# blades_v40.net
KiCad netlist of a schematic drawn in EAGLE
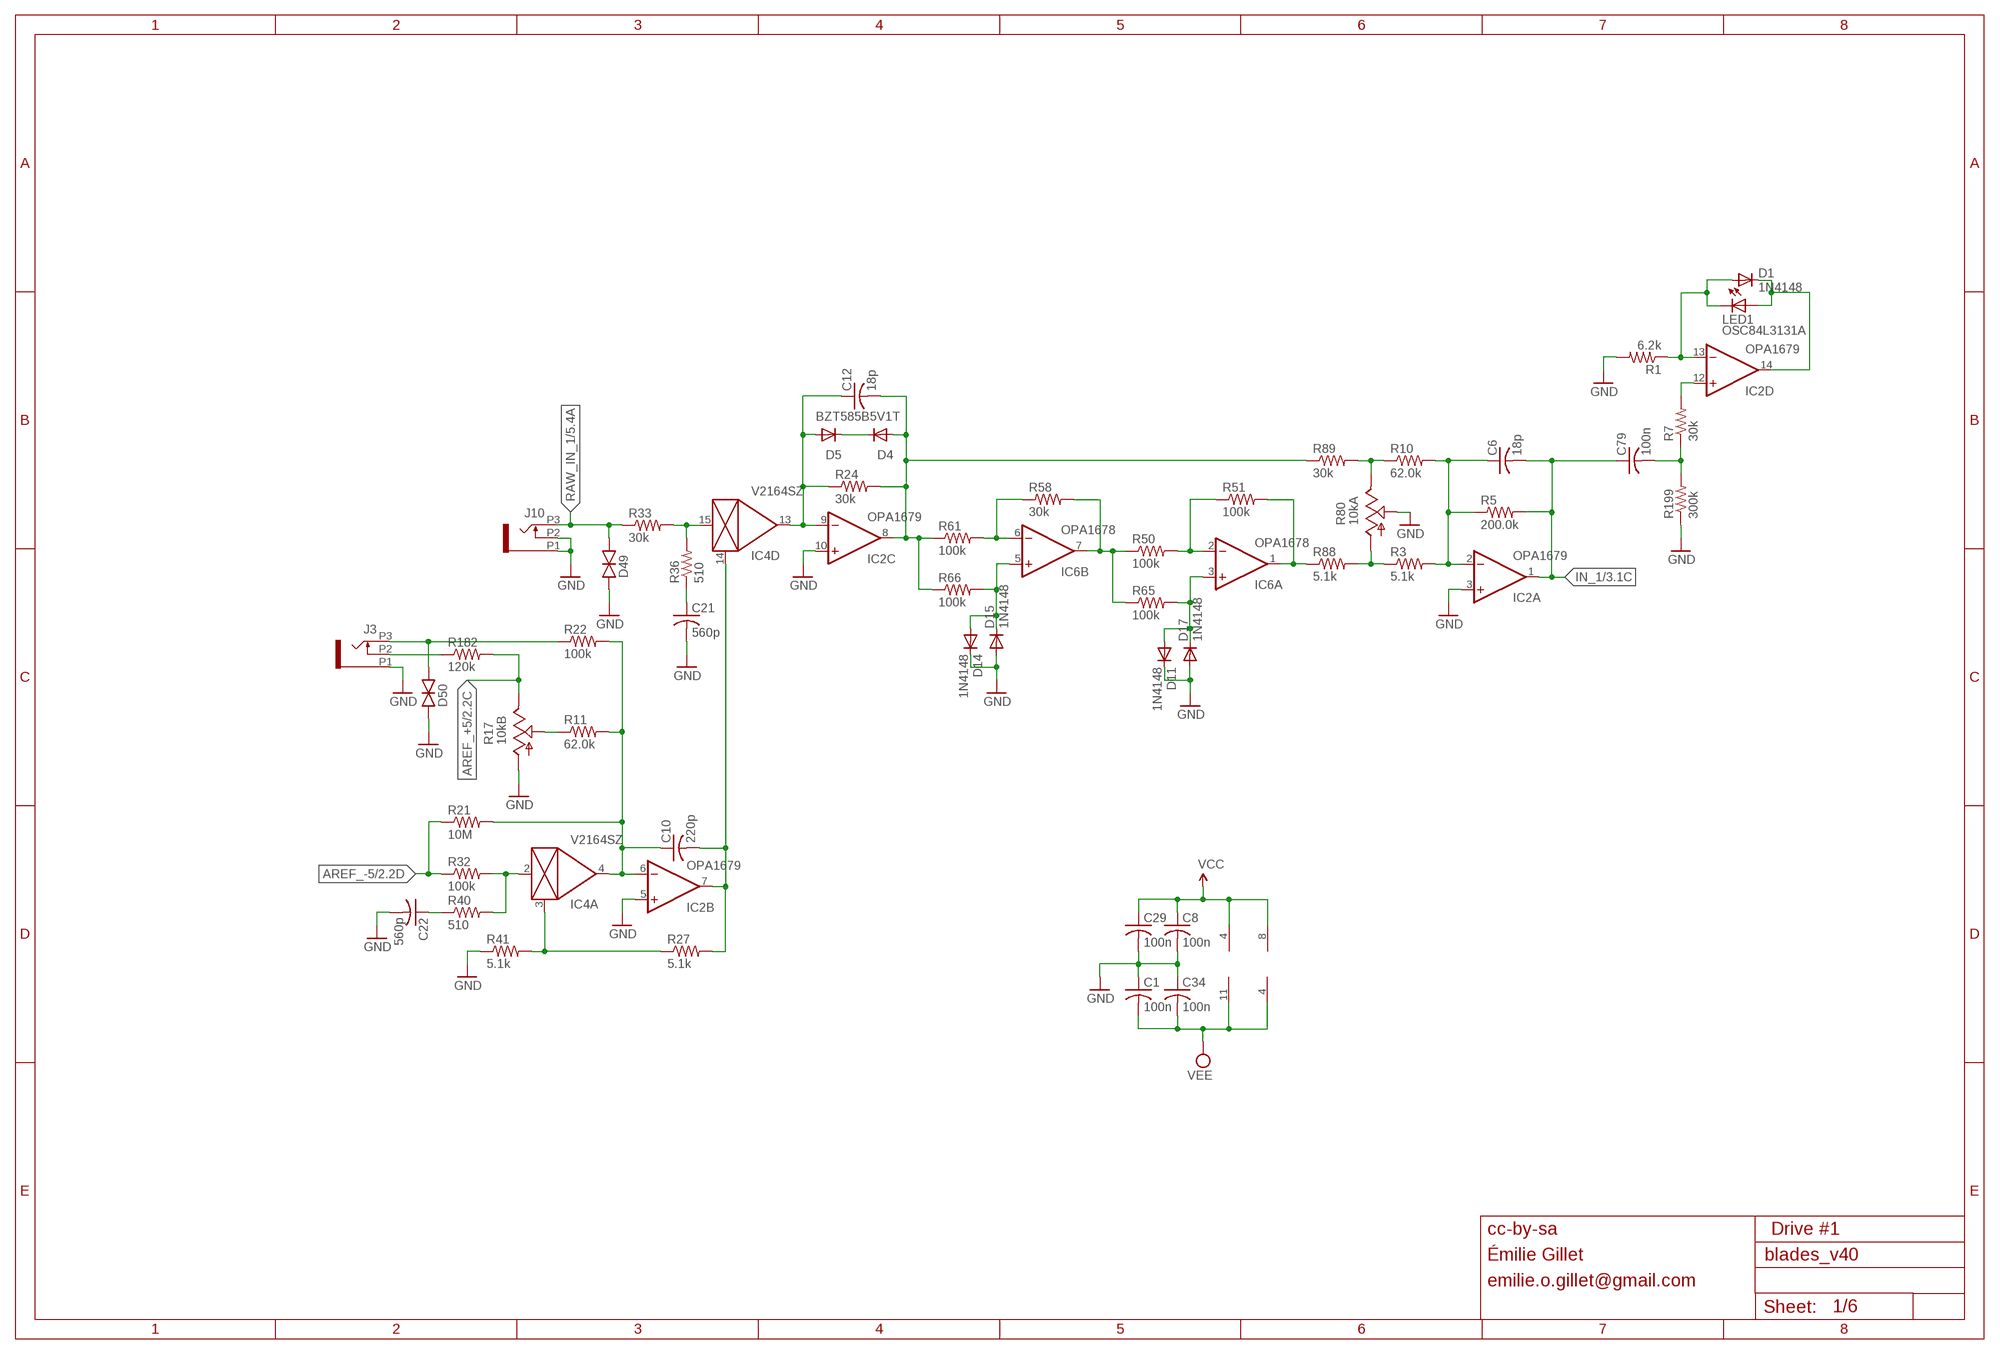
[diagram p0: schematic, sheet 1]
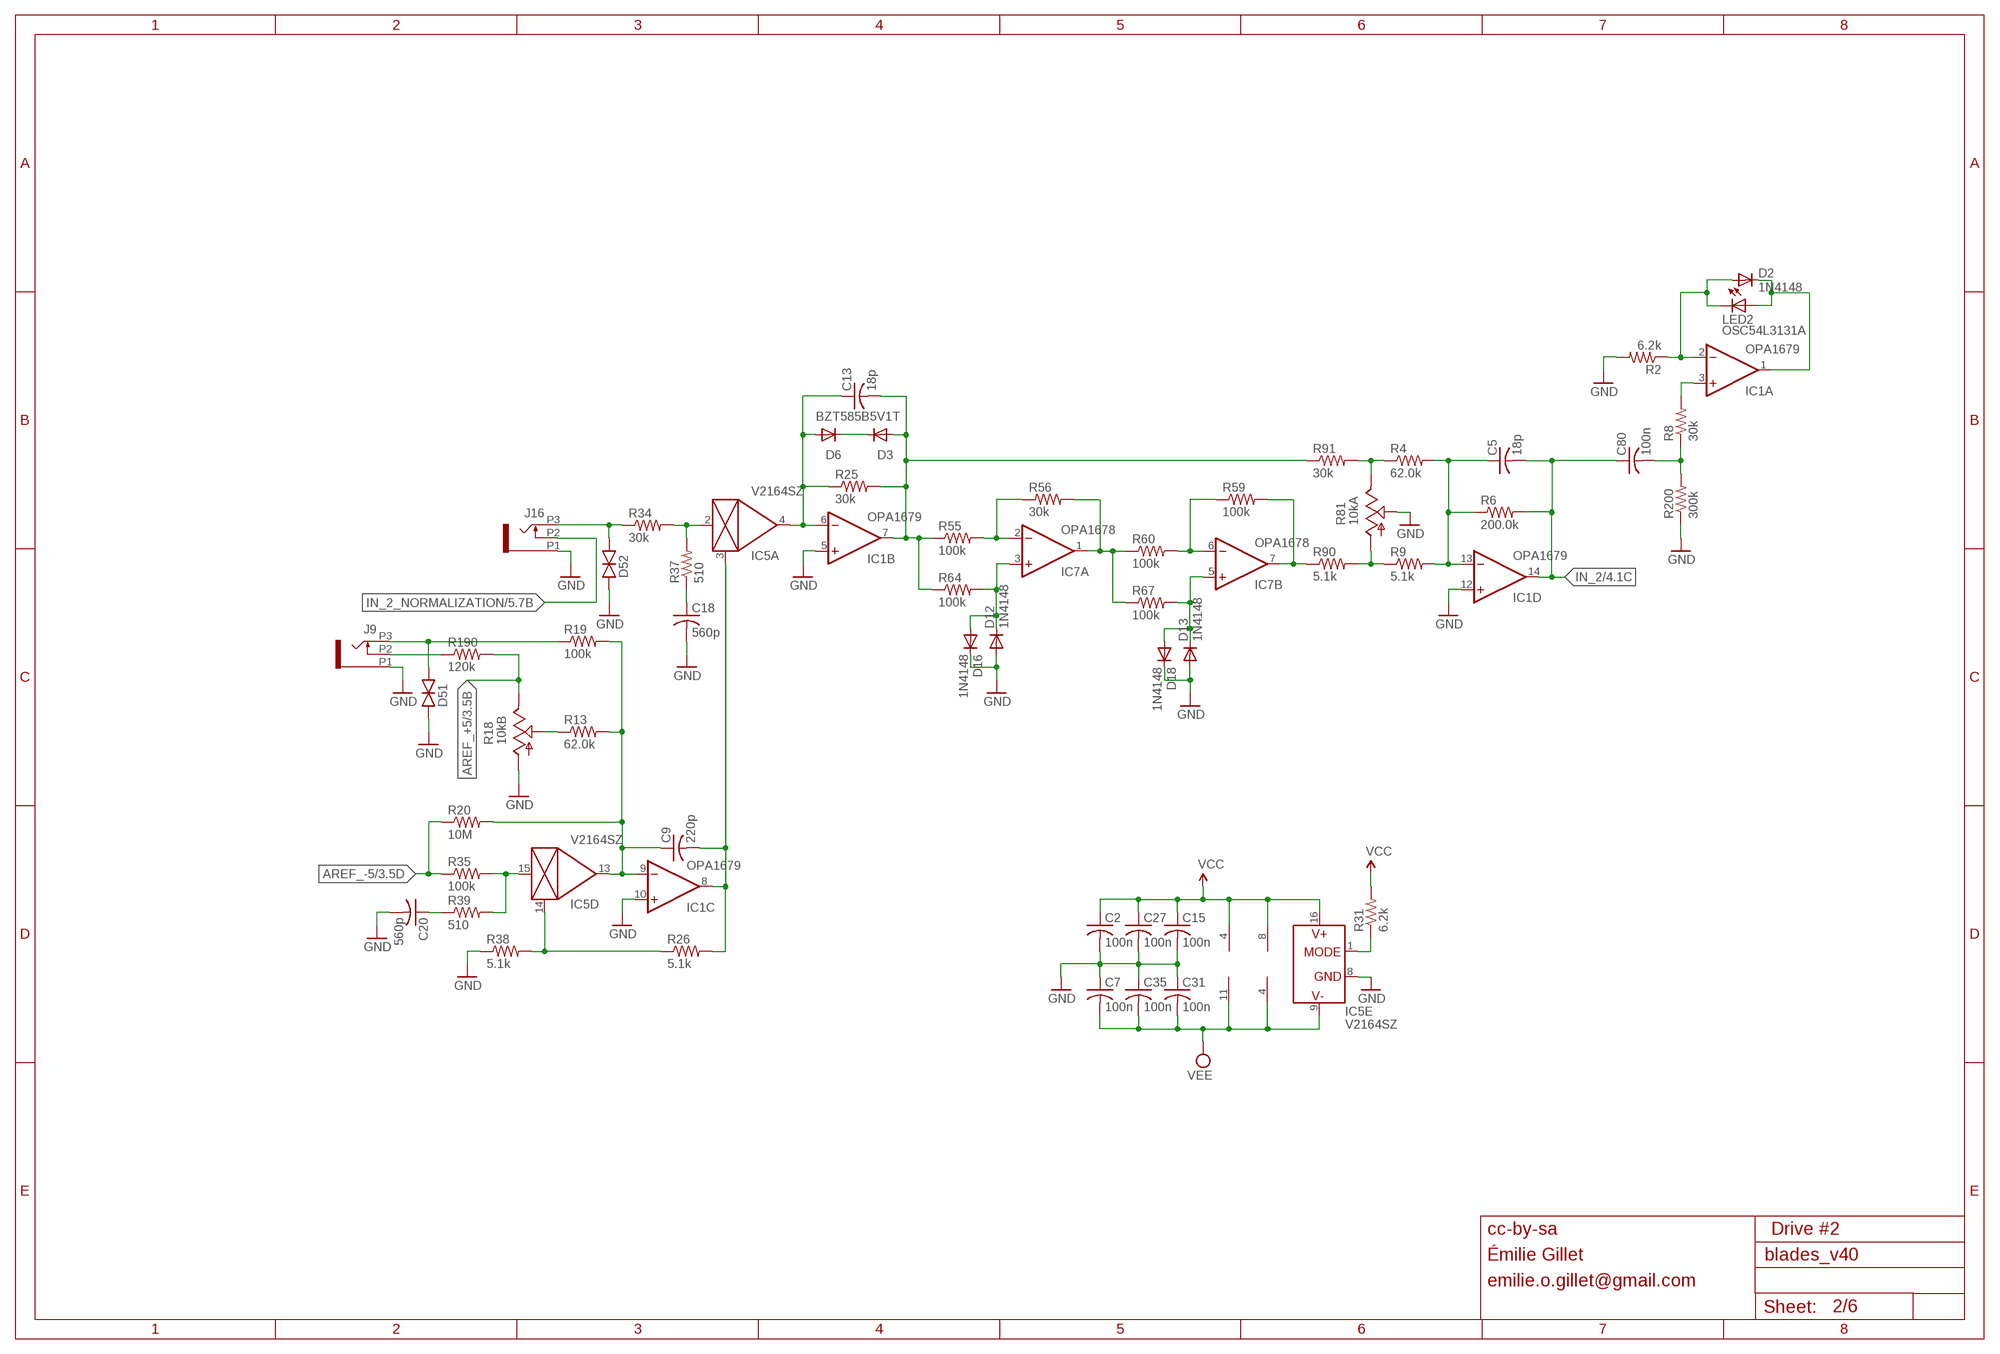
[diagram p1: schematic, sheet 2]
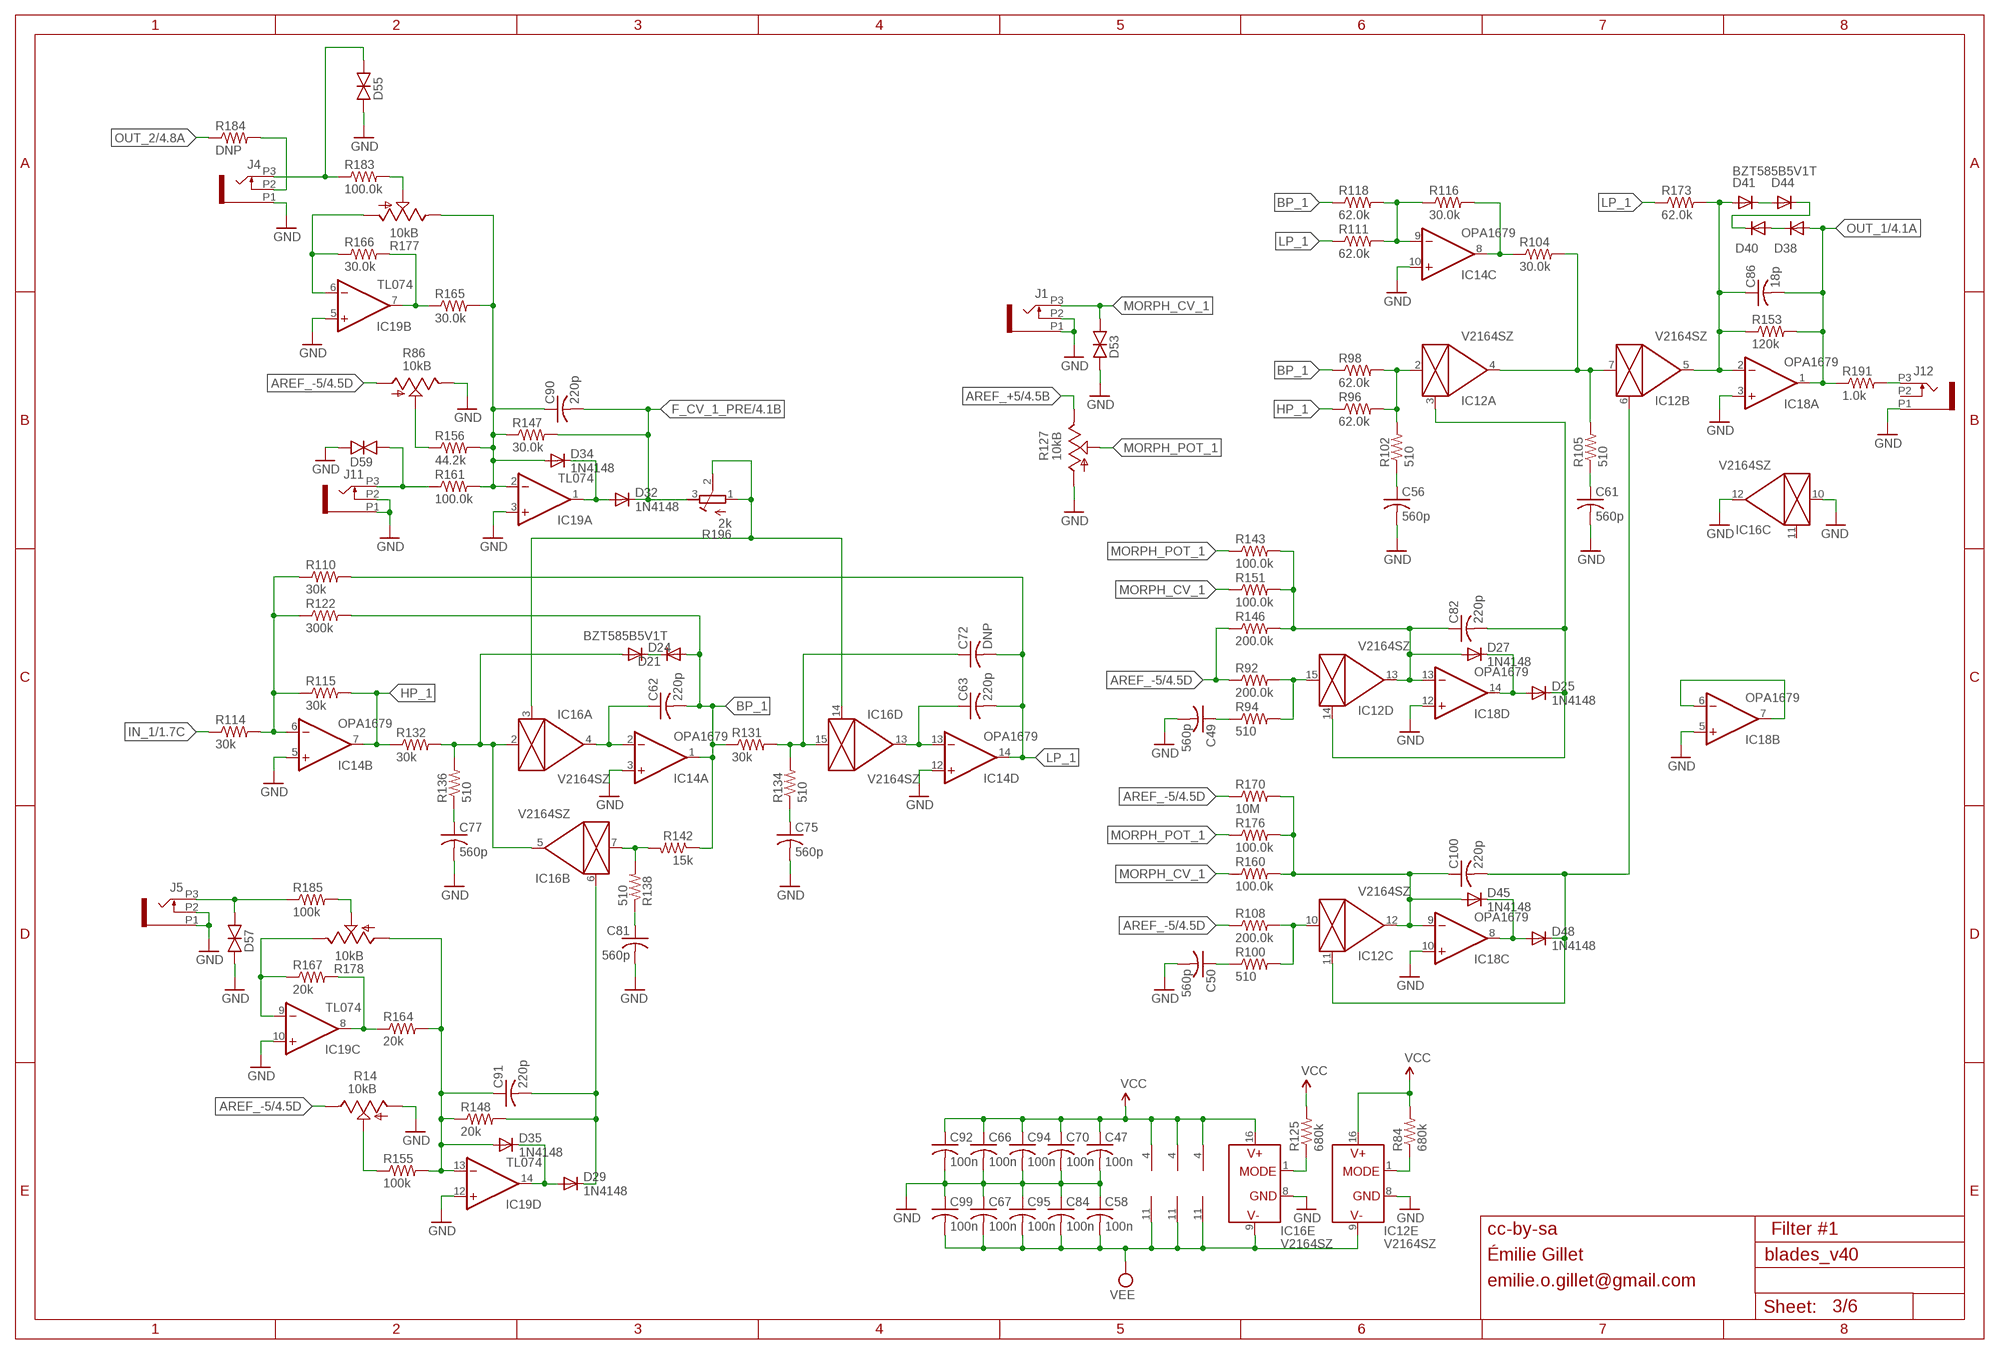
[diagram p2: schematic, sheet 3]
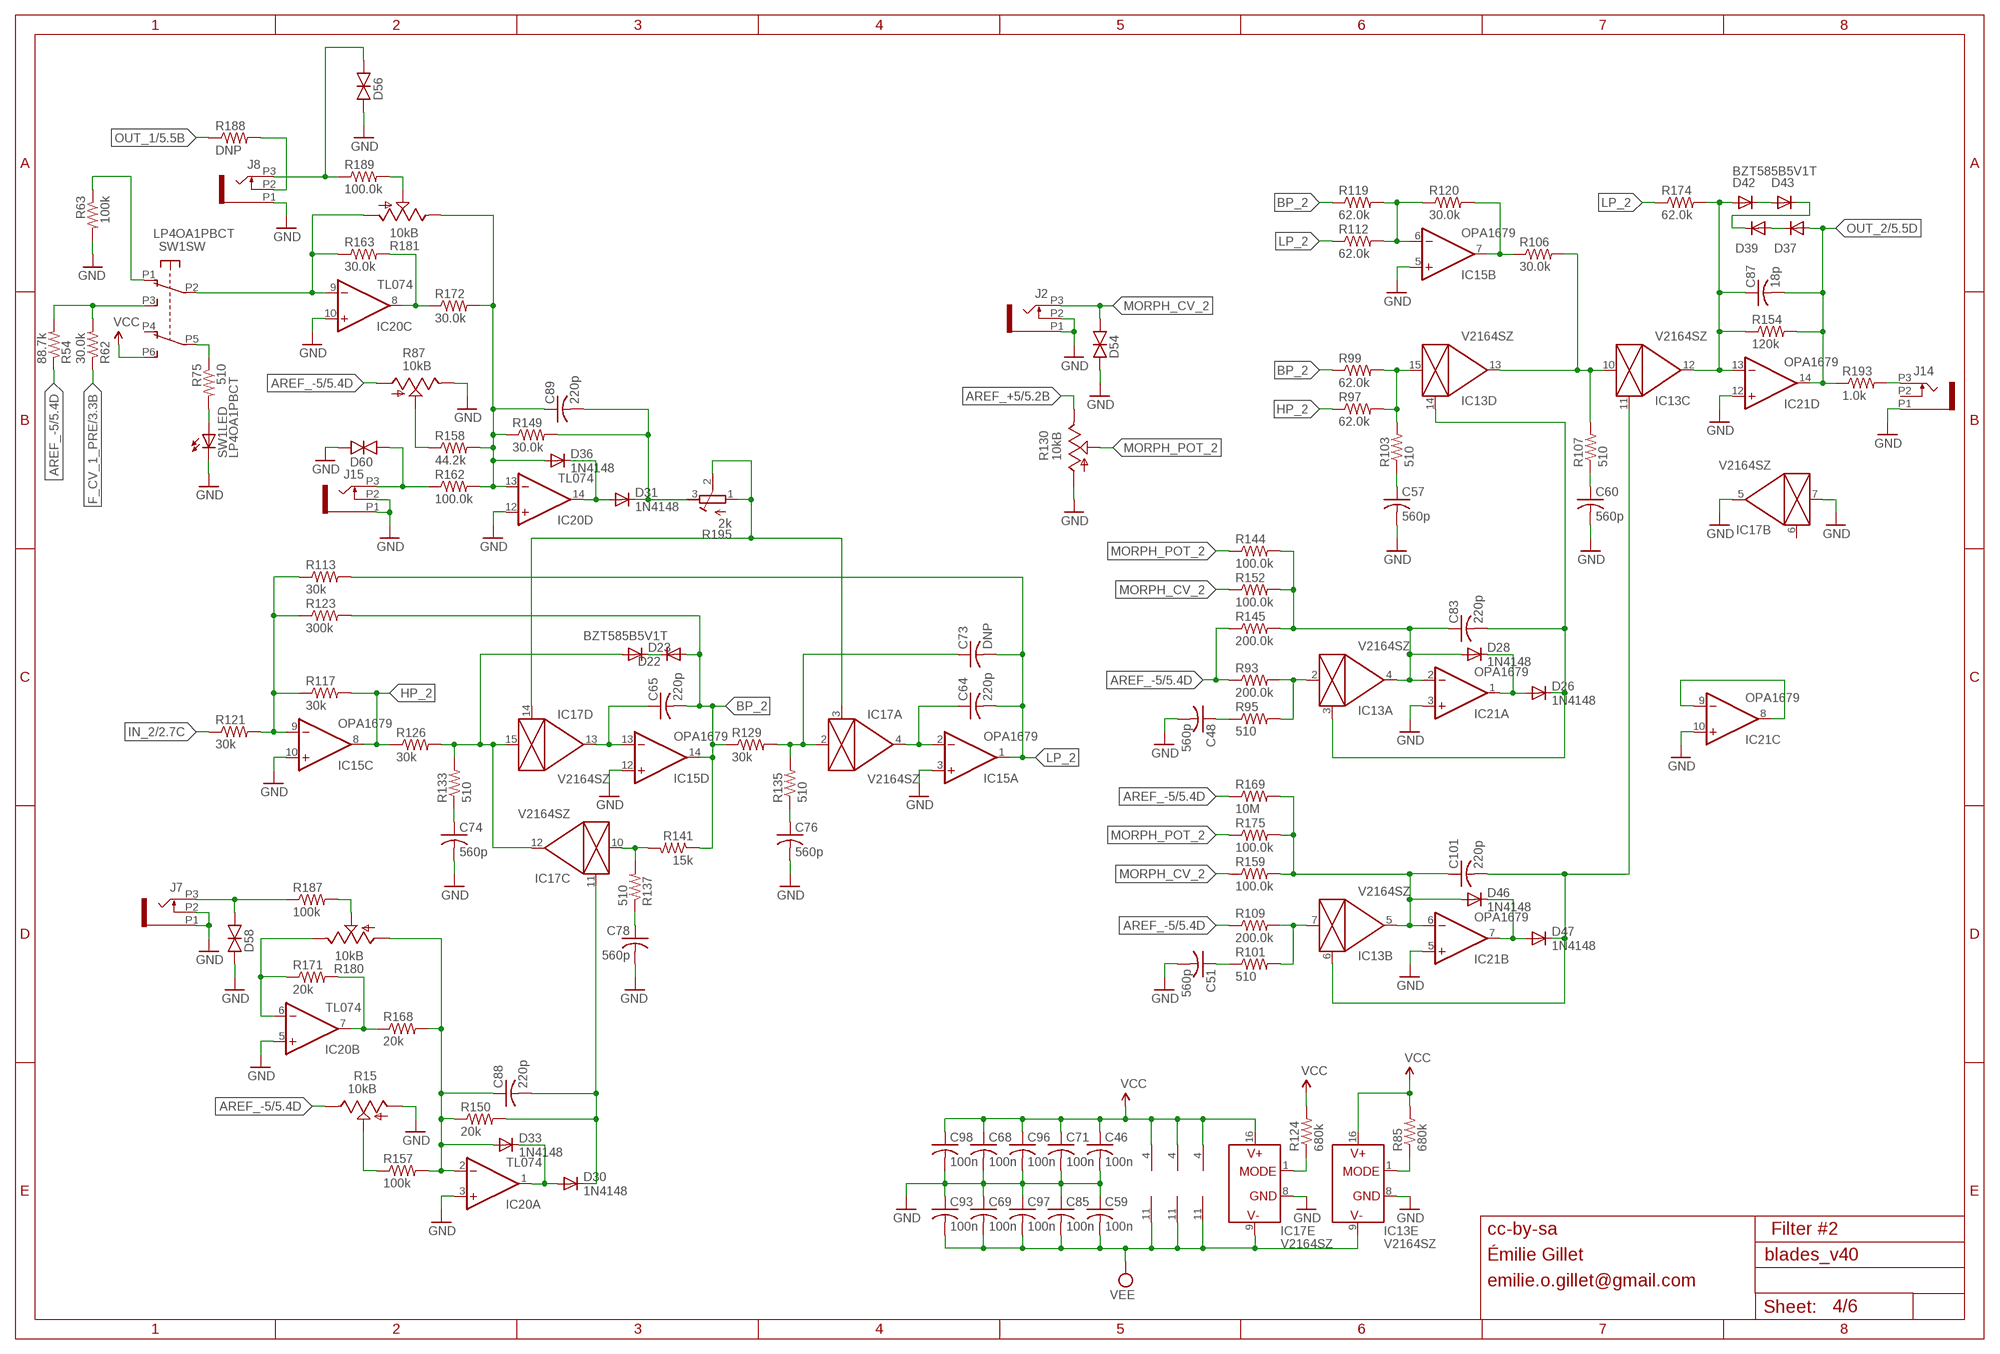
[diagram p3: schematic, sheet 4]
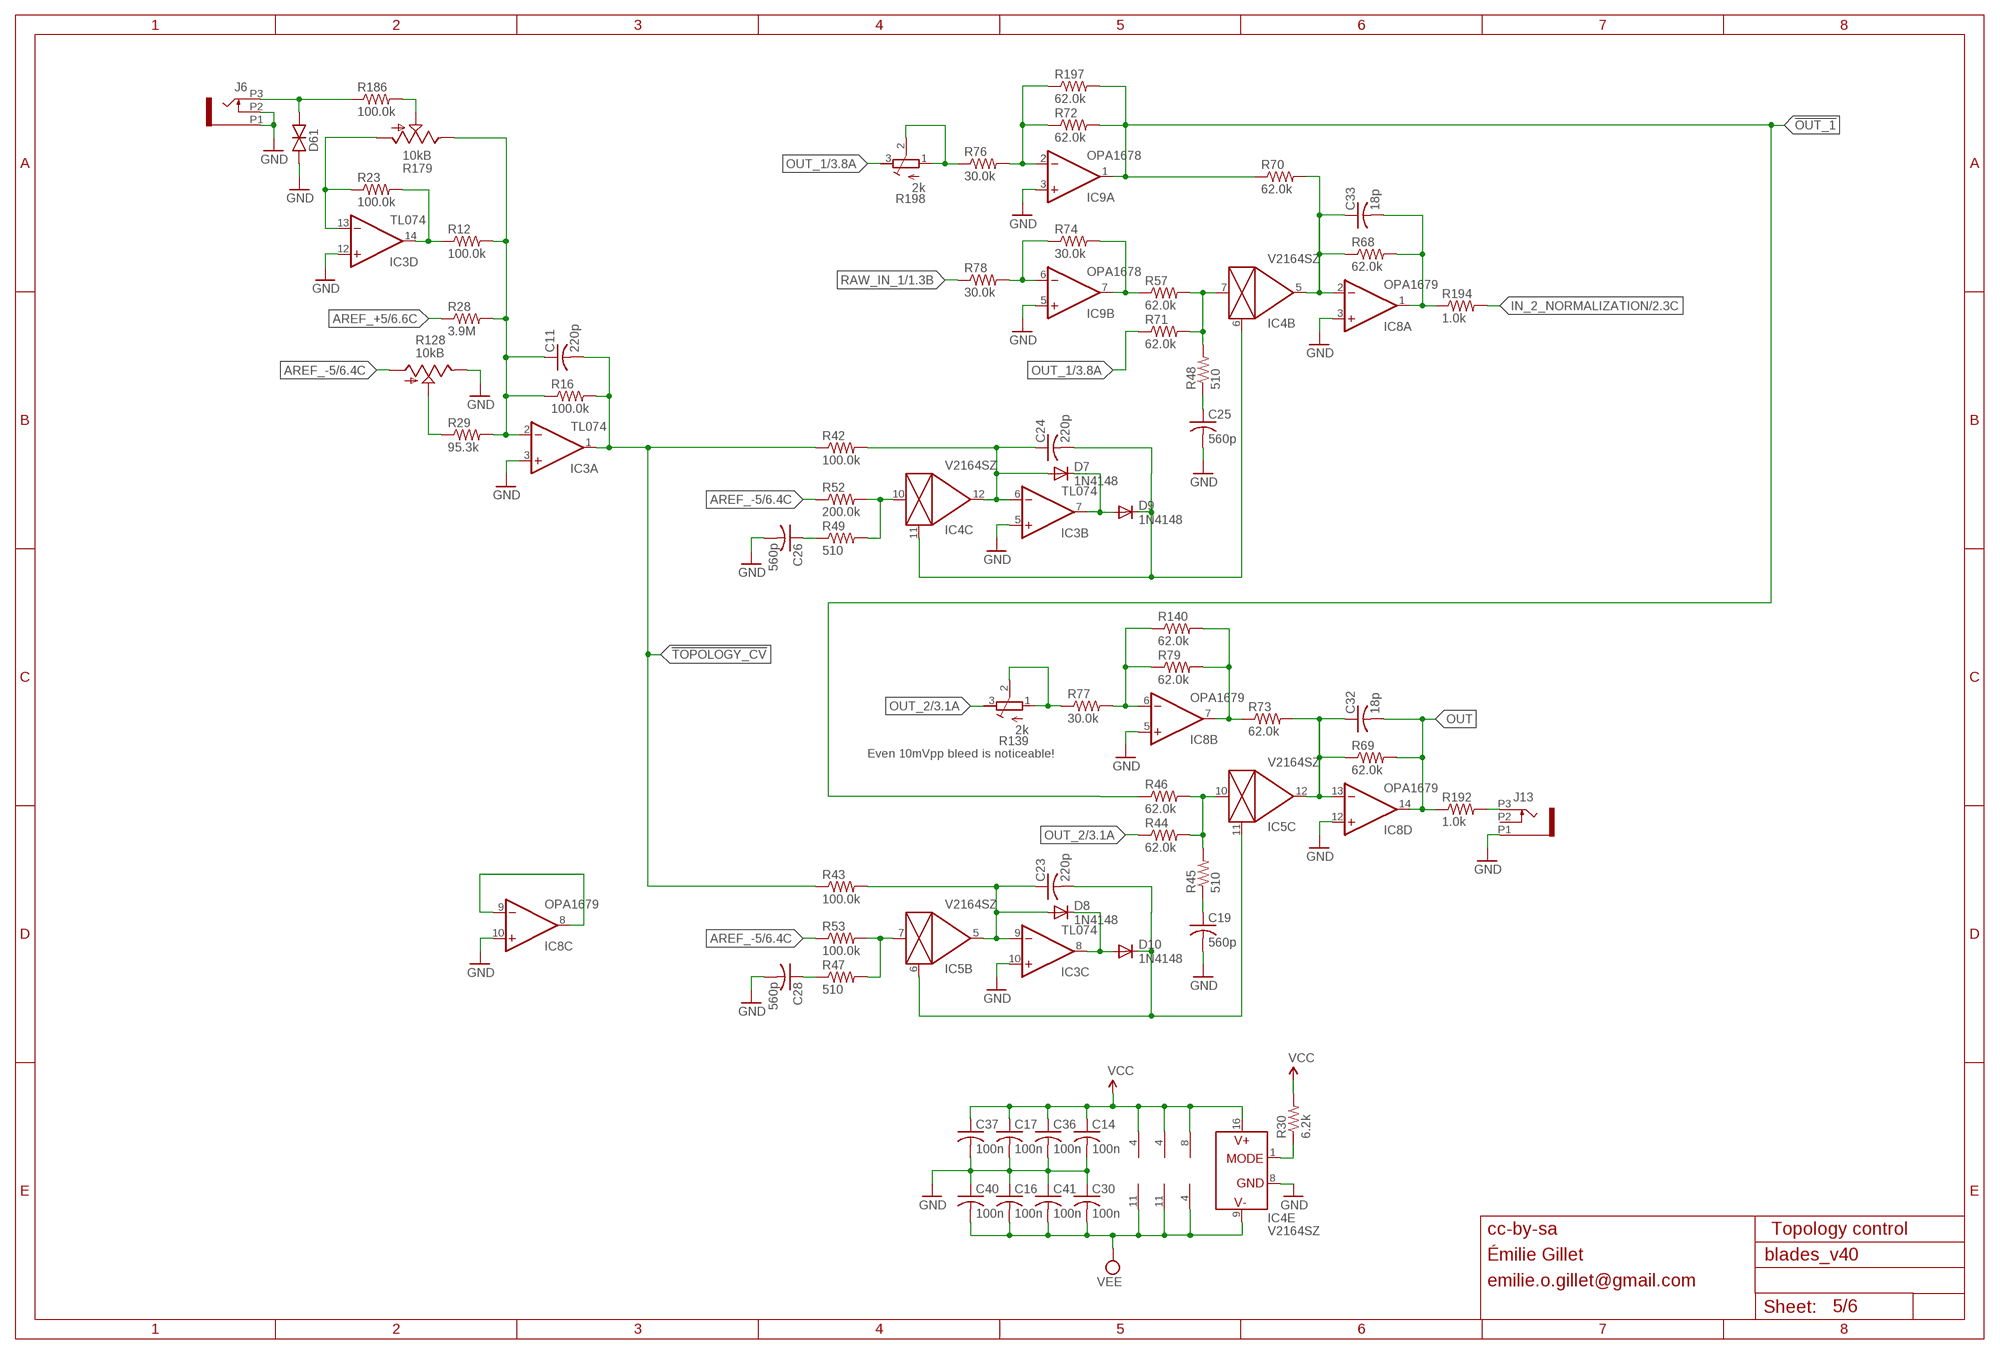
[diagram p4: schematic, sheet 5]
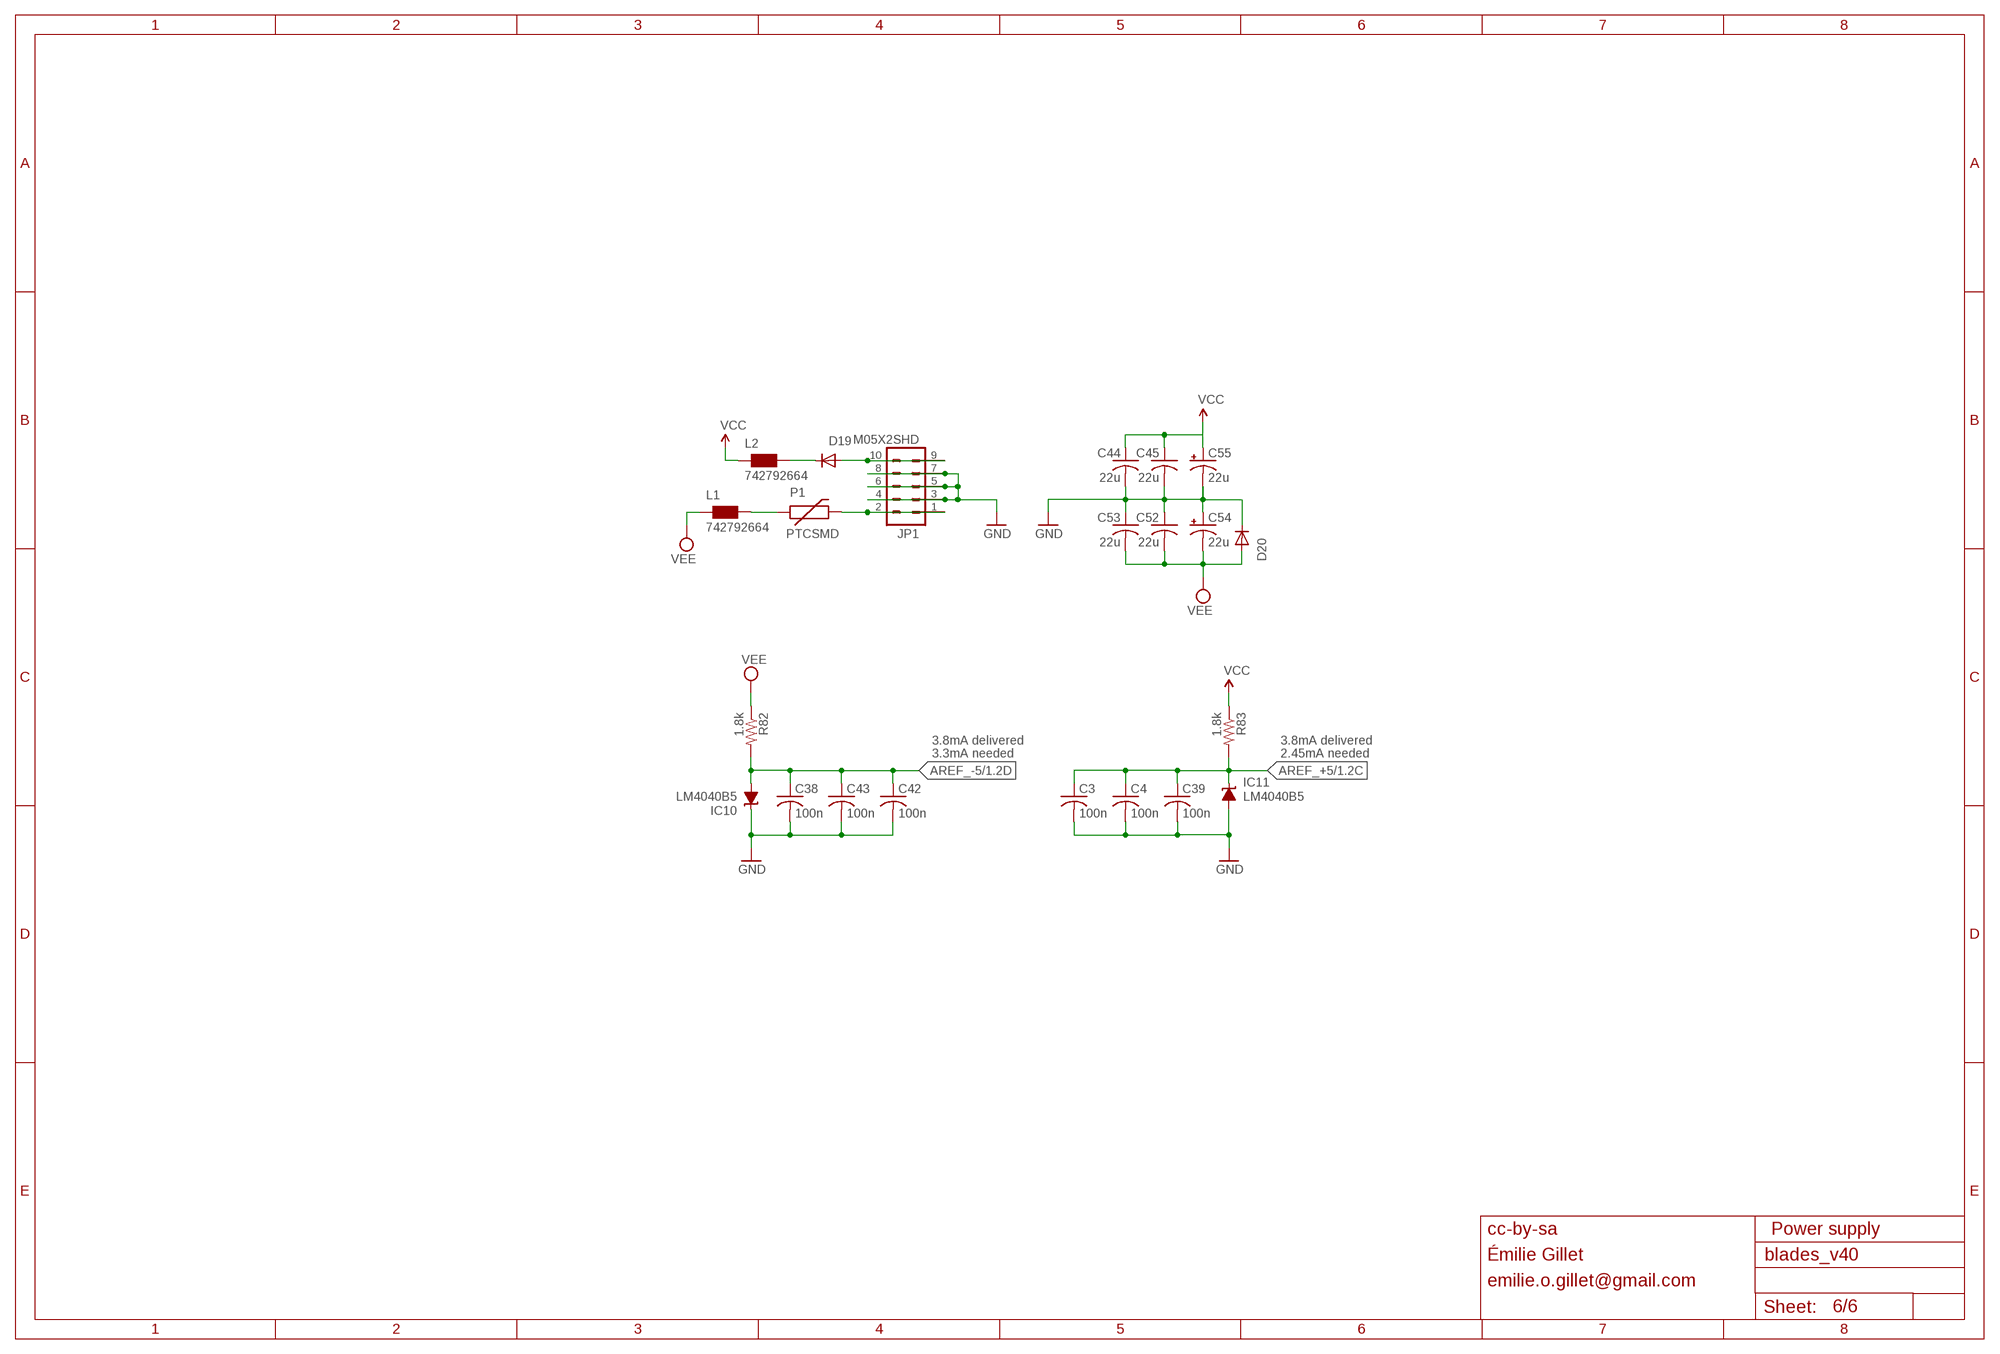
[diagram p5: schematic, sheet 6]

(export (version "E")
  (design (tool "Eeschema 10.0.6"))
  (components
    (comp (ref "C1")
      (value "100n")
      (footprint "eagle-import:C0402")
      (libsource (lib "eagle-import") (part "C-USC0402"))
    )
    (comp (ref "C6")
      (value "18p")
      (footprint "eagle-import:C0402")
      (libsource (lib "eagle-import") (part "C-USC0402"))
    )
    (comp (ref "C8")
      (value "100n")
      (footprint "eagle-import:C0402")
      (libsource (lib "eagle-import") (part "C-USC0402"))
    )
    (comp (ref "C10")
      (value "220p")
      (footprint "eagle-import:C0402")
      (libsource (lib "eagle-import") (part "C-USC0402"))
    )
    (comp (ref "C12")
      (value "18p")
      (footprint "eagle-import:C0402")
      (libsource (lib "eagle-import") (part "C-USC0402"))
    )
    (comp (ref "C21")
      (value "560p")
      (footprint "eagle-import:C0402")
      (libsource (lib "eagle-import") (part "C-USC0402"))
    )
    (comp (ref "C22")
      (value "560p")
      (footprint "eagle-import:C0402")
      (libsource (lib "eagle-import") (part "C-USC0402"))
    )
    (comp (ref "C29")
      (value "100n")
      (footprint "eagle-import:C0402")
      (libsource (lib "eagle-import") (part "C-USC0402"))
    )
    (comp (ref "C34")
      (value "100n")
      (footprint "eagle-import:C0402")
      (libsource (lib "eagle-import") (part "C-USC0402"))
    )
    (comp (ref "C79")
      (value "100n")
      (footprint "eagle-import:C0402")
      (libsource (lib "eagle-import") (part "C-USC0402"))
    )
    (comp (ref "D1")
      (value "1N4148")
      (footprint "eagle-import:SOD523")
      (libsource (lib "eagle-import") (part "DIODE-SOD523"))
    )
    (comp (ref "D4")
      (value "BZT585B5V1T")
      (footprint "eagle-import:SOD523")
      (libsource (lib "eagle-import") (part "DIODE-SOD523"))
    )
    (comp (ref "D5")
      (value "BZT585B5V1T")
      (footprint "eagle-import:SOD523")
      (libsource (lib "eagle-import") (part "DIODE-SOD523"))
    )
    (comp (ref "D11")
      (value "1N4148")
      (footprint "eagle-import:SOD523")
      (libsource (lib "eagle-import") (part "DIODE-SOD523"))
    )
    (comp (ref "D14")
      (value "1N4148")
      (footprint "eagle-import:SOD523")
      (libsource (lib "eagle-import") (part "DIODE-SOD523"))
    )
    (comp (ref "D15")
      (value "1N4148")
      (footprint "eagle-import:SOD523")
      (libsource (lib "eagle-import") (part "DIODE-SOD523"))
    )
    (comp (ref "D17")
      (value "1N4148")
      (footprint "eagle-import:SOD523")
      (libsource (lib "eagle-import") (part "DIODE-SOD523"))
    )
    (comp (ref "D49")
      (value "TVS")
      (footprint "eagle-import:0603")
      (libsource (lib "eagle-import") (part "TVS"))
    )
    (comp (ref "D50")
      (value "TVS")
      (footprint "eagle-import:0603")
      (libsource (lib "eagle-import") (part "TVS"))
    )
    (comp (ref "IC2")
      (value "OPA1679")
      (footprint "eagle-import:TSSOP14_065")
      (libsource (lib "eagle-import") (part "OPA1679PW"))
    )
    (comp (ref "IC4")
      (value "V2164SZ")
      (footprint "eagle-import:SOIC16N")
      (libsource (lib "eagle-import") (part "SSM2164S"))
    )
    (comp (ref "IC6")
      (value "OPA1678")
      (footprint "eagle-import:VSSOP8")
      (libsource (lib "eagle-import") (part "OPA1678DGK"))
    )
    (comp (ref "J3")
      (value "PJ301_THONKICONNTME")
      (footprint "eagle-import:WQP_PJ_301M_TME")
      (libsource (lib "eagle-import") (part "PJ301_THONKICONNTME"))
    )
    (comp (ref "J10")
      (value "PJ301_THONKICONNTME")
      (footprint "eagle-import:WQP_PJ_301M_TME")
      (libsource (lib "eagle-import") (part "PJ301_THONKICONNTME"))
    )
    (comp (ref "LED1")
      (value "OSC84L3131A")
      (footprint "eagle-import:LED3MM")
      (libsource (lib "eagle-import") (part "LED3MM"))
    )
    (comp (ref "R1")
      (value "6.2k")
      (footprint "eagle-import:R0402")
      (libsource (lib "eagle-import") (part "R-US_R0402"))
    )
    (comp (ref "R3")
      (value "5.1k")
      (footprint "eagle-import:R0402")
      (libsource (lib "eagle-import") (part "R-US_R0402"))
    )
    (comp (ref "R5")
      (value "200.0k")
      (footprint "eagle-import:R0402")
      (libsource (lib "eagle-import") (part "R-US_R0402"))
    )
    (comp (ref "R7")
      (value "30k")
      (footprint "eagle-import:R0402")
      (libsource (lib "eagle-import") (part "R-US_R0402"))
    )
    (comp (ref "R10")
      (value "62.0k")
      (footprint "eagle-import:R0402")
      (libsource (lib "eagle-import") (part "R-US_R0402"))
    )
    (comp (ref "R11")
      (value "62.0k")
      (footprint "eagle-import:R0402")
      (libsource (lib "eagle-import") (part "R-US_R0402"))
    )
    (comp (ref "R17")
      (value "10kB")
      (footprint "eagle-import:ALPS_POT_VERTICAL_PS")
      (libsource (lib "eagle-import") (part "pot-alps_POT_USVERTICAL_PS"))
    )
    (comp (ref "R21")
      (value "10M")
      (footprint "eagle-import:R0402")
      (libsource (lib "eagle-import") (part "R-US_R0402"))
    )
    (comp (ref "R22")
      (value "100k")
      (footprint "eagle-import:R0402")
      (libsource (lib "eagle-import") (part "R-US_R0402"))
    )
    (comp (ref "R24")
      (value "30k")
      (footprint "eagle-import:R0402")
      (libsource (lib "eagle-import") (part "R-US_R0402"))
    )
    (comp (ref "R27")
      (value "5.1k")
      (footprint "eagle-import:R0402")
      (libsource (lib "eagle-import") (part "R-US_R0402"))
    )
    (comp (ref "R32")
      (value "100k")
      (footprint "eagle-import:R0402")
      (libsource (lib "eagle-import") (part "R-US_R0402"))
    )
    (comp (ref "R33")
      (value "30k")
      (footprint "eagle-import:R0402")
      (libsource (lib "eagle-import") (part "R-US_R0402"))
    )
    (comp (ref "R36")
      (value "510")
      (footprint "eagle-import:R0402")
      (libsource (lib "eagle-import") (part "R-US_R0402"))
    )
    (comp (ref "R40")
      (value "510")
      (footprint "eagle-import:R0402")
      (libsource (lib "eagle-import") (part "R-US_R0402"))
    )
    (comp (ref "R41")
      (value "5.1k")
      (footprint "eagle-import:R0402")
      (libsource (lib "eagle-import") (part "R-US_R0402"))
    )
    (comp (ref "R50")
      (value "100k")
      (footprint "eagle-import:R0402")
      (libsource (lib "eagle-import") (part "R-US_R0402"))
    )
    (comp (ref "R51")
      (value "100k")
      (footprint "eagle-import:R0402")
      (libsource (lib "eagle-import") (part "R-US_R0402"))
    )
    (comp (ref "R58")
      (value "30k")
      (footprint "eagle-import:R0402")
      (libsource (lib "eagle-import") (part "R-US_R0402"))
    )
    (comp (ref "R61")
      (value "100k")
      (footprint "eagle-import:R0402")
      (libsource (lib "eagle-import") (part "R-US_R0402"))
    )
    (comp (ref "R65")
      (value "100k")
      (footprint "eagle-import:R0402")
      (libsource (lib "eagle-import") (part "R-US_R0402"))
    )
    (comp (ref "R66")
      (value "100k")
      (footprint "eagle-import:R0402")
      (libsource (lib "eagle-import") (part "R-US_R0402"))
    )
    (comp (ref "R80")
      (value "10kA")
      (footprint "eagle-import:ALPS_POT_NARROW")
      (libsource (lib "eagle-import") (part "POT_USVERTICAL_NARROW"))
    )
    (comp (ref "R88")
      (value "5.1k")
      (footprint "eagle-import:R0402")
      (libsource (lib "eagle-import") (part "R-US_R0402"))
    )
    (comp (ref "R89")
      (value "30k")
      (footprint "eagle-import:R0402")
      (libsource (lib "eagle-import") (part "R-US_R0402"))
    )
    (comp (ref "R182")
      (value "120k")
      (footprint "eagle-import:R0402")
      (libsource (lib "eagle-import") (part "R-US_R0402"))
    )
    (comp (ref "R199")
      (value "300k")
      (footprint "eagle-import:R0402")
      (libsource (lib "eagle-import") (part "R-US_R0402"))
    )
    (comp (ref "C46")
      (value "100n")
      (footprint "eagle-import:C0402")
      (libsource (lib "eagle-import") (part "C-USC0402"))
    )
    (comp (ref "C48")
      (value "560p")
      (footprint "eagle-import:C0402")
      (libsource (lib "eagle-import") (part "C-USC0402"))
    )
    (comp (ref "C51")
      (value "560p")
      (footprint "eagle-import:C0402")
      (libsource (lib "eagle-import") (part "C-USC0402"))
    )
    (comp (ref "C57")
      (value "560p")
      (footprint "eagle-import:C0402")
      (libsource (lib "eagle-import") (part "C-USC0402"))
    )
    (comp (ref "C59")
      (value "100n")
      (footprint "eagle-import:C0402")
      (libsource (lib "eagle-import") (part "C-USC0402"))
    )
    (comp (ref "C60")
      (value "560p")
      (footprint "eagle-import:C0402")
      (libsource (lib "eagle-import") (part "C-USC0402"))
    )
    (comp (ref "C64")
      (value "220p")
      (footprint "eagle-import:C0402")
      (libsource (lib "eagle-import") (part "C-USC0402"))
    )
    (comp (ref "C65")
      (value "220p")
      (footprint "eagle-import:C0402")
      (libsource (lib "eagle-import") (part "C-USC0402"))
    )
    (comp (ref "C68")
      (value "100n")
      (footprint "eagle-import:C0402")
      (libsource (lib "eagle-import") (part "C-USC0402"))
    )
    (comp (ref "C69")
      (value "100n")
      (footprint "eagle-import:C0402")
      (libsource (lib "eagle-import") (part "C-USC0402"))
    )
    (comp (ref "C71")
      (value "100n")
      (footprint "eagle-import:C0402")
      (libsource (lib "eagle-import") (part "C-USC0402"))
    )
    (comp (ref "C73")
      (value "DNP")
      (footprint "eagle-import:C0402")
      (libsource (lib "eagle-import") (part "C-USC0402"))
    )
    (comp (ref "C74")
      (value "560p")
      (footprint "eagle-import:C0402")
      (libsource (lib "eagle-import") (part "C-USC0402"))
    )
    (comp (ref "C76")
      (value "560p")
      (footprint "eagle-import:C0402")
      (libsource (lib "eagle-import") (part "C-USC0402"))
    )
    (comp (ref "C78")
      (value "560p")
      (footprint "eagle-import:C0402")
      (libsource (lib "eagle-import") (part "C-USC0402"))
    )
    (comp (ref "C83")
      (value "220p")
      (footprint "eagle-import:C0402")
      (libsource (lib "eagle-import") (part "C-USC0402"))
    )
    (comp (ref "C85")
      (value "100n")
      (footprint "eagle-import:C0402")
      (libsource (lib "eagle-import") (part "C-USC0402"))
    )
    (comp (ref "C87")
      (value "18p")
      (footprint "eagle-import:C0402")
      (libsource (lib "eagle-import") (part "C-USC0402"))
    )
    (comp (ref "C88")
      (value "220p")
      (footprint "eagle-import:C0402")
      (libsource (lib "eagle-import") (part "C-USC0402"))
    )
    (comp (ref "C89")
      (value "220p")
      (footprint "eagle-import:C0402")
      (libsource (lib "eagle-import") (part "C-USC0402"))
    )
    (comp (ref "C93")
      (value "100n")
      (footprint "eagle-import:C0402")
      (libsource (lib "eagle-import") (part "C-USC0402"))
    )
    (comp (ref "C96")
      (value "100n")
      (footprint "eagle-import:C0402")
      (libsource (lib "eagle-import") (part "C-USC0402"))
    )
    (comp (ref "C97")
      (value "100n")
      (footprint "eagle-import:C0402")
      (libsource (lib "eagle-import") (part "C-USC0402"))
    )
    (comp (ref "C98")
      (value "100n")
      (footprint "eagle-import:C0402")
      (libsource (lib "eagle-import") (part "C-USC0402"))
    )
    (comp (ref "C101")
      (value "220p")
      (footprint "eagle-import:C0402")
      (libsource (lib "eagle-import") (part "C-USC0402"))
    )
    (comp (ref "D22")
      (value "BZT585B5V1T")
      (footprint "eagle-import:SOD523")
      (libsource (lib "eagle-import") (part "DIODE-SOD523"))
    )
    (comp (ref "D23")
      (value "BZT585B5V1T")
      (footprint "eagle-import:SOD523")
      (libsource (lib "eagle-import") (part "DIODE-SOD523"))
    )
    (comp (ref "D26")
      (value "1N4148")
      (footprint "eagle-import:SOD523")
      (libsource (lib "eagle-import") (part "DIODE-SOD523"))
    )
    (comp (ref "D28")
      (value "1N4148")
      (footprint "eagle-import:SOD523")
      (libsource (lib "eagle-import") (part "DIODE-SOD523"))
    )
    (comp (ref "D30")
      (value "1N4148")
      (footprint "eagle-import:SOD523")
      (libsource (lib "eagle-import") (part "DIODE-SOD523"))
    )
    (comp (ref "D31")
      (value "1N4148")
      (footprint "eagle-import:SOD523")
      (libsource (lib "eagle-import") (part "DIODE-SOD523"))
    )
    (comp (ref "D33")
      (value "1N4148")
      (footprint "eagle-import:SOD523")
      (libsource (lib "eagle-import") (part "DIODE-SOD523"))
    )
    (comp (ref "D36")
      (value "1N4148")
      (footprint "eagle-import:SOD523")
      (libsource (lib "eagle-import") (part "DIODE-SOD523"))
    )
    (comp (ref "D37")
      (value "BZT585B5V1T")
      (footprint "eagle-import:SOD523")
      (libsource (lib "eagle-import") (part "DIODE-SOD523"))
    )
    (comp (ref "D39")
      (value "BZT585B5V1T")
      (footprint "eagle-import:SOD523")
      (libsource (lib "eagle-import") (part "DIODE-SOD523"))
    )
    (comp (ref "D42")
      (value "BZT585B5V1T")
      (footprint "eagle-import:SOD523")
      (libsource (lib "eagle-import") (part "DIODE-SOD523"))
    )
    (comp (ref "D43")
      (value "BZT585B5V1T")
      (footprint "eagle-import:SOD523")
      (libsource (lib "eagle-import") (part "DIODE-SOD523"))
    )
    (comp (ref "D46")
      (value "1N4148")
      (footprint "eagle-import:SOD523")
      (libsource (lib "eagle-import") (part "DIODE-SOD523"))
    )
    (comp (ref "D47")
      (value "1N4148")
      (footprint "eagle-import:SOD523")
      (libsource (lib "eagle-import") (part "DIODE-SOD523"))
    )
    (comp (ref "D54")
      (value "TVS")
      (footprint "eagle-import:0603")
      (libsource (lib "eagle-import") (part "TVS"))
    )
    (comp (ref "D56")
      (value "TVS")
      (footprint "eagle-import:0603")
      (libsource (lib "eagle-import") (part "TVS"))
    )
    (comp (ref "D58")
      (value "TVS")
      (footprint "eagle-import:0603")
      (libsource (lib "eagle-import") (part "TVS"))
    )
    (comp (ref "D60")
      (value "TVS")
      (footprint "eagle-import:0603")
      (libsource (lib "eagle-import") (part "TVS"))
    )
    (comp (ref "IC13")
      (value "V2164SZ")
      (footprint "eagle-import:SOIC16N")
      (libsource (lib "eagle-import") (part "SSM2164S"))
    )
    (comp (ref "IC15")
      (value "OPA1679")
      (footprint "eagle-import:TSSOP14_065")
      (libsource (lib "eagle-import") (part "OPA1679PW"))
    )
    (comp (ref "IC17")
      (value "V2164SZ")
      (footprint "eagle-import:SOIC16N")
      (libsource (lib "eagle-import") (part "SSM2164S"))
    )
    (comp (ref "IC20")
      (value "TL074")
      (footprint "eagle-import:TSSOP14_065")
      (libsource (lib "eagle-import") (part "TL074PW"))
    )
    (comp (ref "IC21")
      (value "OPA1679")
      (footprint "eagle-import:TSSOP14_065")
      (libsource (lib "eagle-import") (part "OPA1679PW"))
    )
    (comp (ref "J2")
      (value "PJ301_THONKICONNTME")
      (footprint "eagle-import:WQP_PJ_301M_TME")
      (libsource (lib "eagle-import") (part "PJ301_THONKICONNTME"))
    )
    (comp (ref "J7")
      (value "PJ301_THONKICONNTME")
      (footprint "eagle-import:WQP_PJ_301M_TME")
      (libsource (lib "eagle-import") (part "PJ301_THONKICONNTME"))
    )
    (comp (ref "J8")
      (value "PJ301_THONKICONNTME")
      (footprint "eagle-import:WQP_PJ_301M_TME")
      (libsource (lib "eagle-import") (part "PJ301_THONKICONNTME"))
    )
    (comp (ref "J14")
      (value "PJ301_THONKICONNTME")
      (footprint "eagle-import:WQP_PJ_301M_TME")
      (libsource (lib "eagle-import") (part "PJ301_THONKICONNTME"))
    )
    (comp (ref "J15")
      (value "PJ301_THONKICONNTME")
      (footprint "eagle-import:WQP_PJ_301M_TME")
      (libsource (lib "eagle-import") (part "PJ301_THONKICONNTME"))
    )
    (comp (ref "R15")
      (value "10kB")
      (footprint "eagle-import:ALPS_POT_VERTICAL_PS")
      (libsource (lib "eagle-import") (part "pot-alps_POT_USVERTICAL_PS"))
    )
    (comp (ref "R54")
      (value "88.7k")
      (footprint "eagle-import:R0402")
      (libsource (lib "eagle-import") (part "R-US_R0402"))
    )
    (comp (ref "R62")
      (value "30.0k")
      (footprint "eagle-import:R0402")
      (libsource (lib "eagle-import") (part "R-US_R0402"))
    )
    (comp (ref "R63")
      (value "100k")
      (footprint "eagle-import:R0402")
      (libsource (lib "eagle-import") (part "R-US_R0402"))
    )
    (comp (ref "R75")
      (value "510")
      (footprint "eagle-import:R0402")
      (libsource (lib "eagle-import") (part "R-US_R0402"))
    )
    (comp (ref "R85")
      (value "680k")
      (footprint "eagle-import:R0402")
      (libsource (lib "eagle-import") (part "R-US_R0402"))
    )
    (comp (ref "R87")
      (value "10kB")
      (footprint "eagle-import:ALPS_POT_VERTICAL_PS")
      (libsource (lib "eagle-import") (part "pot-alps_POT_USVERTICAL_PS"))
    )
    (comp (ref "R93")
      (value "200.0k")
      (footprint "eagle-import:R0402")
      (libsource (lib "eagle-import") (part "R-US_R0402"))
    )
    (comp (ref "R95")
      (value "510")
      (footprint "eagle-import:R0402")
      (libsource (lib "eagle-import") (part "R-US_R0402"))
    )
    (comp (ref "R97")
      (value "62.0k")
      (footprint "eagle-import:R0402")
      (libsource (lib "eagle-import") (part "R-US_R0402"))
    )
    (comp (ref "R99")
      (value "62.0k")
      (footprint "eagle-import:R0402")
      (libsource (lib "eagle-import") (part "R-US_R0402"))
    )
    (comp (ref "R101")
      (value "510")
      (footprint "eagle-import:R0402")
      (libsource (lib "eagle-import") (part "R-US_R0402"))
    )
    (comp (ref "R103")
      (value "510")
      (footprint "eagle-import:R0402")
      (libsource (lib "eagle-import") (part "R-US_R0402"))
    )
    (comp (ref "R106")
      (value "30.0k")
      (footprint "eagle-import:R0402")
      (libsource (lib "eagle-import") (part "R-US_R0402"))
    )
    (comp (ref "R107")
      (value "510")
      (footprint "eagle-import:R0402")
      (libsource (lib "eagle-import") (part "R-US_R0402"))
    )
    (comp (ref "R109")
      (value "200.0k")
      (footprint "eagle-import:R0402")
      (libsource (lib "eagle-import") (part "R-US_R0402"))
    )
    (comp (ref "R112")
      (value "62.0k")
      (footprint "eagle-import:R0402")
      (libsource (lib "eagle-import") (part "R-US_R0402"))
    )
    (comp (ref "R113")
      (value "30k")
      (footprint "eagle-import:R0402")
      (libsource (lib "eagle-import") (part "R-US_R0402"))
    )
    (comp (ref "R117")
      (value "30k")
      (footprint "eagle-import:R0402")
      (libsource (lib "eagle-import") (part "R-US_R0402"))
    )
    (comp (ref "R119")
      (value "62.0k")
      (footprint "eagle-import:R0402")
      (libsource (lib "eagle-import") (part "R-US_R0402"))
    )
    (comp (ref "R120")
      (value "30.0k")
      (footprint "eagle-import:R0402")
      (libsource (lib "eagle-import") (part "R-US_R0402"))
    )
    (comp (ref "R121")
      (value "30k")
      (footprint "eagle-import:R0402")
      (libsource (lib "eagle-import") (part "R-US_R0402"))
    )
    (comp (ref "R123")
      (value "300k")
      (footprint "eagle-import:R0402")
      (libsource (lib "eagle-import") (part "R-US_R0402"))
    )
    (comp (ref "R124")
      (value "680k")
      (footprint "eagle-import:R0402")
      (libsource (lib "eagle-import") (part "R-US_R0402"))
    )
    (comp (ref "R126")
      (value "30k")
      (footprint "eagle-import:R0402")
      (libsource (lib "eagle-import") (part "R-US_R0402"))
    )
    (comp (ref "R129")
      (value "30k")
      (footprint "eagle-import:R0402")
      (libsource (lib "eagle-import") (part "R-US_R0402"))
    )
    (comp (ref "R130")
      (value "10kB")
      (footprint "eagle-import:ALPS_POT_VERTICAL_PS")
      (libsource (lib "eagle-import") (part "pot-alps_POT_USVERTICAL_PS"))
    )
    (comp (ref "R133")
      (value "510")
      (footprint "eagle-import:R0402")
      (libsource (lib "eagle-import") (part "R-US_R0402"))
    )
    (comp (ref "R135")
      (value "510")
      (footprint "eagle-import:R0402")
      (libsource (lib "eagle-import") (part "R-US_R0402"))
    )
    (comp (ref "R137")
      (value "510")
      (footprint "eagle-import:R0402")
      (libsource (lib "eagle-import") (part "R-US_R0402"))
    )
    (comp (ref "R141")
      (value "15k")
      (footprint "eagle-import:R0402")
      (libsource (lib "eagle-import") (part "R-US_R0402"))
    )
    (comp (ref "R144")
      (value "100.0k")
      (footprint "eagle-import:R0402")
      (libsource (lib "eagle-import") (part "R-US_R0402"))
    )
    (comp (ref "R145")
      (value "200.0k")
      (footprint "eagle-import:R0402")
      (libsource (lib "eagle-import") (part "R-US_R0402"))
    )
    (comp (ref "R149")
      (value "30.0k")
      (footprint "eagle-import:R0402")
      (libsource (lib "eagle-import") (part "R-US_R0402"))
    )
    (comp (ref "R150")
      (value "20k")
      (footprint "eagle-import:R0402")
      (libsource (lib "eagle-import") (part "R-US_R0402"))
    )
    (comp (ref "R152")
      (value "100.0k")
      (footprint "eagle-import:R0402")
      (libsource (lib "eagle-import") (part "R-US_R0402"))
    )
    (comp (ref "R154")
      (value "120k")
      (footprint "eagle-import:R0402")
      (libsource (lib "eagle-import") (part "R-US_R0402"))
    )
    (comp (ref "R157")
      (value "100k")
      (footprint "eagle-import:R0402")
      (libsource (lib "eagle-import") (part "R-US_R0402"))
    )
    (comp (ref "R158")
      (value "44.2k")
      (footprint "eagle-import:R0402")
      (libsource (lib "eagle-import") (part "R-US_R0402"))
    )
    (comp (ref "R159")
      (value "100.0k")
      (footprint "eagle-import:R0402")
      (libsource (lib "eagle-import") (part "R-US_R0402"))
    )
    (comp (ref "R162")
      (value "100.0k")
      (footprint "eagle-import:R0402")
      (libsource (lib "eagle-import") (part "R-US_R0402"))
    )
    (comp (ref "R163")
      (value "30.0k")
      (footprint "eagle-import:R0402")
      (libsource (lib "eagle-import") (part "R-US_R0402"))
    )
    (comp (ref "R168")
      (value "20k")
      (footprint "eagle-import:R0402")
      (libsource (lib "eagle-import") (part "R-US_R0402"))
    )
    (comp (ref "R169")
      (value "10M")
      (footprint "eagle-import:R0402")
      (libsource (lib "eagle-import") (part "R-US_R0402"))
    )
    (comp (ref "R171")
      (value "20k")
      (footprint "eagle-import:R0402")
      (libsource (lib "eagle-import") (part "R-US_R0402"))
    )
    (comp (ref "R172")
      (value "30.0k")
      (footprint "eagle-import:R0402")
      (libsource (lib "eagle-import") (part "R-US_R0402"))
    )
    (comp (ref "R174")
      (value "62.0k")
      (footprint "eagle-import:R0402")
      (libsource (lib "eagle-import") (part "R-US_R0402"))
    )
    (comp (ref "R175")
      (value "100.0k")
      (footprint "eagle-import:R0402")
      (libsource (lib "eagle-import") (part "R-US_R0402"))
    )
    (comp (ref "R180")
      (value "10kB")
      (footprint "eagle-import:ALPS_POT_NARROW")
      (libsource (lib "eagle-import") (part "POT_USVERTICAL_NARROW"))
    )
    (comp (ref "R181")
      (value "10kB")
      (footprint "eagle-import:ALPS_POT_NARROW")
      (libsource (lib "eagle-import") (part "POT_USVERTICAL_NARROW"))
    )
    (comp (ref "R187")
      (value "100k")
      (footprint "eagle-import:R0402")
      (libsource (lib "eagle-import") (part "R-US_R0402"))
    )
    (comp (ref "R188")
      (value "DNP")
      (footprint "eagle-import:R0603")
      (libsource (lib "eagle-import") (part "R-US_R0603"))
    )
    (comp (ref "R189")
      (value "100.0k")
      (footprint "eagle-import:R0402")
      (libsource (lib "eagle-import") (part "R-US_R0402"))
    )
    (comp (ref "R193")
      (value "1.0k")
      (footprint "eagle-import:R0603")
      (libsource (lib "eagle-import") (part "R-US_R0603"))
    )
    (comp (ref "R195")
      (value "2k")
      (footprint "eagle-import:RTRIM3296W")
      (libsource (lib "eagle-import") (part "R-TRIMM3296W"))
    )
    (comp (ref "SW1")
      (value "LP4OA1PBCT")
      (footprint "eagle-import:LP4OA1PBCT")
      (libsource (lib "eagle-import") (part "LP4OA1PBCT"))
    )
    (comp (ref "C11")
      (value "220p")
      (footprint "eagle-import:C0402")
      (libsource (lib "eagle-import") (part "C-USC0402"))
    )
    (comp (ref "C14")
      (value "100n")
      (footprint "eagle-import:C0402")
      (libsource (lib "eagle-import") (part "C-USC0402"))
    )
    (comp (ref "C16")
      (value "100n")
      (footprint "eagle-import:C0402")
      (libsource (lib "eagle-import") (part "C-USC0402"))
    )
    (comp (ref "C17")
      (value "100n")
      (footprint "eagle-import:C0402")
      (libsource (lib "eagle-import") (part "C-USC0402"))
    )
    (comp (ref "C19")
      (value "560p")
      (footprint "eagle-import:C0402")
      (libsource (lib "eagle-import") (part "C-USC0402"))
    )
    (comp (ref "C23")
      (value "220p")
      (footprint "eagle-import:C0402")
      (libsource (lib "eagle-import") (part "C-USC0402"))
    )
    (comp (ref "C24")
      (value "220p")
      (footprint "eagle-import:C0402")
      (libsource (lib "eagle-import") (part "C-USC0402"))
    )
    (comp (ref "C25")
      (value "560p")
      (footprint "eagle-import:C0402")
      (libsource (lib "eagle-import") (part "C-USC0402"))
    )
    (comp (ref "C26")
      (value "560p")
      (footprint "eagle-import:C0402")
      (libsource (lib "eagle-import") (part "C-USC0402"))
    )
    (comp (ref "C28")
      (value "560p")
      (footprint "eagle-import:C0402")
      (libsource (lib "eagle-import") (part "C-USC0402"))
    )
    (comp (ref "C30")
      (value "100n")
      (footprint "eagle-import:C0402")
      (libsource (lib "eagle-import") (part "C-USC0402"))
    )
    (comp (ref "C32")
      (value "18p")
      (footprint "eagle-import:C0402")
      (libsource (lib "eagle-import") (part "C-USC0402"))
    )
    (comp (ref "C33")
      (value "18p")
      (footprint "eagle-import:C0402")
      (libsource (lib "eagle-import") (part "C-USC0402"))
    )
    (comp (ref "C36")
      (value "100n")
      (footprint "eagle-import:C0402")
      (libsource (lib "eagle-import") (part "C-USC0402"))
    )
    (comp (ref "C37")
      (value "100n")
      (footprint "eagle-import:C0402")
      (libsource (lib "eagle-import") (part "C-USC0402"))
    )
    (comp (ref "C40")
      (value "100n")
      (footprint "eagle-import:C0402")
      (libsource (lib "eagle-import") (part "C-USC0402"))
    )
    (comp (ref "C41")
      (value "100n")
      (footprint "eagle-import:C0402")
      (libsource (lib "eagle-import") (part "C-USC0402"))
    )
    (comp (ref "D7")
      (value "1N4148")
      (footprint "eagle-import:SOD523")
      (libsource (lib "eagle-import") (part "DIODE-SOD523"))
    )
    (comp (ref "D8")
      (value "1N4148")
      (footprint "eagle-import:SOD523")
      (libsource (lib "eagle-import") (part "DIODE-SOD523"))
    )
    (comp (ref "D9")
      (value "1N4148")
      (footprint "eagle-import:SOD523")
      (libsource (lib "eagle-import") (part "DIODE-SOD523"))
    )
    (comp (ref "D10")
      (value "1N4148")
      (footprint "eagle-import:SOD523")
      (libsource (lib "eagle-import") (part "DIODE-SOD523"))
    )
    (comp (ref "D61")
      (value "TVS")
      (footprint "eagle-import:0603")
      (libsource (lib "eagle-import") (part "TVS"))
    )
    (comp (ref "IC3")
      (value "TL074")
      (footprint "eagle-import:TSSOP14_065")
      (libsource (lib "eagle-import") (part "TL074PW"))
    )
    (comp (ref "IC5")
      (value "V2164SZ")
      (footprint "eagle-import:SOIC16N")
      (libsource (lib "eagle-import") (part "SSM2164S"))
    )
    (comp (ref "IC8")
      (value "OPA1679")
      (footprint "eagle-import:TSSOP14_065")
      (libsource (lib "eagle-import") (part "OPA1679PW"))
    )
    (comp (ref "IC9")
      (value "OPA1678")
      (footprint "eagle-import:VSSOP8")
      (libsource (lib "eagle-import") (part "OPA1678DGK"))
    )
    (comp (ref "J6")
      (value "PJ301_THONKICONNTME")
      (footprint "eagle-import:WQP_PJ_301M_TME")
      (libsource (lib "eagle-import") (part "PJ301_THONKICONNTME"))
    )
    (comp (ref "J13")
      (value "PJ301_THONKICONNTME")
      (footprint "eagle-import:WQP_PJ_301M_TME")
      (libsource (lib "eagle-import") (part "PJ301_THONKICONNTME"))
    )
    (comp (ref "R12")
      (value "100.0k")
      (footprint "eagle-import:R0402")
      (libsource (lib "eagle-import") (part "R-US_R0402"))
    )
    (comp (ref "R16")
      (value "100.0k")
      (footprint "eagle-import:R0402")
      (libsource (lib "eagle-import") (part "R-US_R0402"))
    )
    (comp (ref "R23")
      (value "100.0k")
      (footprint "eagle-import:R0402")
      (libsource (lib "eagle-import") (part "R-US_R0402"))
    )
    (comp (ref "R28")
      (value "3.9M")
      (footprint "eagle-import:R0402")
      (libsource (lib "eagle-import") (part "R-US_R0402"))
    )
    (comp (ref "R29")
      (value "95.3k")
      (footprint "eagle-import:R0402")
      (libsource (lib "eagle-import") (part "R-US_R0402"))
    )
    (comp (ref "R30")
      (value "6.2k")
      (footprint "eagle-import:R0402")
      (libsource (lib "eagle-import") (part "R-US_R0402"))
    )
    (comp (ref "R42")
      (value "100.0k")
      (footprint "eagle-import:R0402")
      (libsource (lib "eagle-import") (part "R-US_R0402"))
    )
    (comp (ref "R43")
      (value "100.0k")
      (footprint "eagle-import:R0402")
      (libsource (lib "eagle-import") (part "R-US_R0402"))
    )
    (comp (ref "R44")
      (value "62.0k")
      (footprint "eagle-import:R0402")
      (libsource (lib "eagle-import") (part "R-US_R0402"))
    )
    (comp (ref "R45")
      (value "510")
      (footprint "eagle-import:R0402")
      (libsource (lib "eagle-import") (part "R-US_R0402"))
    )
    (comp (ref "R46")
      (value "62.0k")
      (footprint "eagle-import:R0402")
      (libsource (lib "eagle-import") (part "R-US_R0402"))
    )
    (comp (ref "R47")
      (value "510")
      (footprint "eagle-import:R0402")
      (libsource (lib "eagle-import") (part "R-US_R0402"))
    )
    (comp (ref "R48")
      (value "510")
      (footprint "eagle-import:R0402")
      (libsource (lib "eagle-import") (part "R-US_R0402"))
    )
    (comp (ref "R49")
      (value "510")
      (footprint "eagle-import:R0402")
      (libsource (lib "eagle-import") (part "R-US_R0402"))
    )
    (comp (ref "R52")
      (value "200.0k")
      (footprint "eagle-import:R0402")
      (libsource (lib "eagle-import") (part "R-US_R0402"))
    )
    (comp (ref "R53")
      (value "100.0k")
      (footprint "eagle-import:R0402")
      (libsource (lib "eagle-import") (part "R-US_R0402"))
    )
    (comp (ref "R57")
      (value "62.0k")
      (footprint "eagle-import:R0402")
      (libsource (lib "eagle-import") (part "R-US_R0402"))
    )
    (comp (ref "R68")
      (value "62.0k")
      (footprint "eagle-import:R0402")
      (libsource (lib "eagle-import") (part "R-US_R0402"))
    )
    (comp (ref "R69")
      (value "62.0k")
      (footprint "eagle-import:R0402")
      (libsource (lib "eagle-import") (part "R-US_R0402"))
    )
    (comp (ref "R70")
      (value "62.0k")
      (footprint "eagle-import:R0402")
      (libsource (lib "eagle-import") (part "R-US_R0402"))
    )
    (comp (ref "R71")
      (value "62.0k")
      (footprint "eagle-import:R0402")
      (libsource (lib "eagle-import") (part "R-US_R0402"))
    )
    (comp (ref "R72")
      (value "62.0k")
      (footprint "eagle-import:R0402")
      (libsource (lib "eagle-import") (part "R-US_R0402"))
    )
    (comp (ref "R73")
      (value "62.0k")
      (footprint "eagle-import:R0402")
      (libsource (lib "eagle-import") (part "R-US_R0402"))
    )
    (comp (ref "R74")
      (value "30.0k")
      (footprint "eagle-import:R0402")
      (libsource (lib "eagle-import") (part "R-US_R0402"))
    )
    (comp (ref "R76")
      (value "30.0k")
      (footprint "eagle-import:R0402")
      (libsource (lib "eagle-import") (part "R-US_R0402"))
    )
    (comp (ref "R77")
      (value "30.0k")
      (footprint "eagle-import:R0402")
      (libsource (lib "eagle-import") (part "R-US_R0402"))
    )
    (comp (ref "R78")
      (value "30.0k")
      (footprint "eagle-import:R0402")
      (libsource (lib "eagle-import") (part "R-US_R0402"))
    )
    (comp (ref "R79")
      (value "62.0k")
      (footprint "eagle-import:R0402")
      (libsource (lib "eagle-import") (part "R-US_R0402"))
    )
    (comp (ref "R128")
      (value "10kB")
      (footprint "eagle-import:ALPS_POT_VERTICAL_PS")
      (libsource (lib "eagle-import") (part "pot-alps_POT_USVERTICAL_PS"))
    )
    (comp (ref "R139")
      (value "2k")
      (footprint "eagle-import:RTRIM3296W")
      (libsource (lib "eagle-import") (part "R-TRIMM3296W"))
    )
    (comp (ref "R140")
      (value "62.0k")
      (footprint "eagle-import:R0402")
      (libsource (lib "eagle-import") (part "R-US_R0402"))
    )
    (comp (ref "R179")
      (value "10kB")
      (footprint "eagle-import:ALPS_POT_NARROW")
      (libsource (lib "eagle-import") (part "POT_USVERTICAL_NARROW"))
    )
    (comp (ref "R186")
      (value "100.0k")
      (footprint "eagle-import:R0402")
      (libsource (lib "eagle-import") (part "R-US_R0402"))
    )
    (comp (ref "R192")
      (value "1.0k")
      (footprint "eagle-import:R0603")
      (libsource (lib "eagle-import") (part "R-US_R0603"))
    )
    (comp (ref "R194")
      (value "1.0k")
      (footprint "eagle-import:R0603")
      (libsource (lib "eagle-import") (part "R-US_R0603"))
    )
    (comp (ref "R197")
      (value "62.0k")
      (footprint "eagle-import:R0402")
      (libsource (lib "eagle-import") (part "R-US_R0402"))
    )
    (comp (ref "R198")
      (value "2k")
      (footprint "eagle-import:RTRIM3296W")
      (libsource (lib "eagle-import") (part "R-TRIMM3296W"))
    )
    (comp (ref "C47")
      (value "100n")
      (footprint "eagle-import:C0402")
      (libsource (lib "eagle-import") (part "C-USC0402"))
    )
    (comp (ref "C49")
      (value "560p")
      (footprint "eagle-import:C0402")
      (libsource (lib "eagle-import") (part "C-USC0402"))
    )
    (comp (ref "C50")
      (value "560p")
      (footprint "eagle-import:C0402")
      (libsource (lib "eagle-import") (part "C-USC0402"))
    )
    (comp (ref "C56")
      (value "560p")
      (footprint "eagle-import:C0402")
      (libsource (lib "eagle-import") (part "C-USC0402"))
    )
    (comp (ref "C58")
      (value "100n")
      (footprint "eagle-import:C0402")
      (libsource (lib "eagle-import") (part "C-USC0402"))
    )
    (comp (ref "C61")
      (value "560p")
      (footprint "eagle-import:C0402")
      (libsource (lib "eagle-import") (part "C-USC0402"))
    )
    (comp (ref "C62")
      (value "220p")
      (footprint "eagle-import:C0402")
      (libsource (lib "eagle-import") (part "C-USC0402"))
    )
    (comp (ref "C63")
      (value "220p")
      (footprint "eagle-import:C0402")
      (libsource (lib "eagle-import") (part "C-USC0402"))
    )
    (comp (ref "C66")
      (value "100n")
      (footprint "eagle-import:C0402")
      (libsource (lib "eagle-import") (part "C-USC0402"))
    )
    (comp (ref "C67")
      (value "100n")
      (footprint "eagle-import:C0402")
      (libsource (lib "eagle-import") (part "C-USC0402"))
    )
    (comp (ref "C70")
      (value "100n")
      (footprint "eagle-import:C0402")
      (libsource (lib "eagle-import") (part "C-USC0402"))
    )
    (comp (ref "C72")
      (value "DNP")
      (footprint "eagle-import:C0402")
      (libsource (lib "eagle-import") (part "C-USC0402"))
    )
    (comp (ref "C75")
      (value "560p")
      (footprint "eagle-import:C0402")
      (libsource (lib "eagle-import") (part "C-USC0402"))
    )
    (comp (ref "C77")
      (value "560p")
      (footprint "eagle-import:C0402")
      (libsource (lib "eagle-import") (part "C-USC0402"))
    )
    (comp (ref "C81")
      (value "560p")
      (footprint "eagle-import:C0402")
      (libsource (lib "eagle-import") (part "C-USC0402"))
    )
    (comp (ref "C82")
      (value "220p")
      (footprint "eagle-import:C0402")
      (libsource (lib "eagle-import") (part "C-USC0402"))
    )
    (comp (ref "C84")
      (value "100n")
      (footprint "eagle-import:C0402")
      (libsource (lib "eagle-import") (part "C-USC0402"))
    )
    (comp (ref "C86")
      (value "18p")
      (footprint "eagle-import:C0402")
      (libsource (lib "eagle-import") (part "C-USC0402"))
    )
    (comp (ref "C90")
      (value "220p")
      (footprint "eagle-import:C0402")
      (libsource (lib "eagle-import") (part "C-USC0402"))
    )
    (comp (ref "C91")
      (value "220p")
      (footprint "eagle-import:C0402")
      (libsource (lib "eagle-import") (part "C-USC0402"))
    )
    (comp (ref "C92")
      (value "100n")
      (footprint "eagle-import:C0402")
      (libsource (lib "eagle-import") (part "C-USC0402"))
    )
    (comp (ref "C94")
      (value "100n")
      (footprint "eagle-import:C0402")
      (libsource (lib "eagle-import") (part "C-USC0402"))
    )
    (comp (ref "C95")
      (value "100n")
      (footprint "eagle-import:C0402")
      (libsource (lib "eagle-import") (part "C-USC0402"))
    )
    (comp (ref "C99")
      (value "100n")
      (footprint "eagle-import:C0402")
      (libsource (lib "eagle-import") (part "C-USC0402"))
    )
    (comp (ref "C100")
      (value "220p")
      (footprint "eagle-import:C0402")
      (libsource (lib "eagle-import") (part "C-USC0402"))
    )
    (comp (ref "D21")
      (value "BZT585B5V1T")
      (footprint "eagle-import:SOD523")
      (libsource (lib "eagle-import") (part "DIODE-SOD523"))
    )
    (comp (ref "D24")
      (value "BZT585B5V1T")
      (footprint "eagle-import:SOD523")
      (libsource (lib "eagle-import") (part "DIODE-SOD523"))
    )
    (comp (ref "D25")
      (value "1N4148")
      (footprint "eagle-import:SOD523")
      (libsource (lib "eagle-import") (part "DIODE-SOD523"))
    )
    (comp (ref "D27")
      (value "1N4148")
      (footprint "eagle-import:SOD523")
      (libsource (lib "eagle-import") (part "DIODE-SOD523"))
    )
    (comp (ref "D29")
      (value "1N4148")
      (footprint "eagle-import:SOD523")
      (libsource (lib "eagle-import") (part "DIODE-SOD523"))
    )
    (comp (ref "D32")
      (value "1N4148")
      (footprint "eagle-import:SOD523")
      (libsource (lib "eagle-import") (part "DIODE-SOD523"))
    )
    (comp (ref "D34")
      (value "1N4148")
      (footprint "eagle-import:SOD523")
      (libsource (lib "eagle-import") (part "DIODE-SOD523"))
    )
    (comp (ref "D35")
      (value "1N4148")
      (footprint "eagle-import:SOD523")
      (libsource (lib "eagle-import") (part "DIODE-SOD523"))
    )
    (comp (ref "D38")
      (value "BZT585B5V1T")
      (footprint "eagle-import:SOD523")
      (libsource (lib "eagle-import") (part "DIODE-SOD523"))
    )
    (comp (ref "D40")
      (value "BZT585B5V1T")
      (footprint "eagle-import:SOD523")
      (libsource (lib "eagle-import") (part "DIODE-SOD523"))
    )
    (comp (ref "D41")
      (value "BZT585B5V1T")
      (footprint "eagle-import:SOD523")
      (libsource (lib "eagle-import") (part "DIODE-SOD523"))
    )
    (comp (ref "D44")
      (value "BZT585B5V1T")
      (footprint "eagle-import:SOD523")
      (libsource (lib "eagle-import") (part "DIODE-SOD523"))
    )
    (comp (ref "D45")
      (value "1N4148")
      (footprint "eagle-import:SOD523")
      (libsource (lib "eagle-import") (part "DIODE-SOD523"))
    )
    (comp (ref "D48")
      (value "1N4148")
      (footprint "eagle-import:SOD523")
      (libsource (lib "eagle-import") (part "DIODE-SOD523"))
    )
    (comp (ref "D53")
      (value "TVS")
      (footprint "eagle-import:0603")
      (libsource (lib "eagle-import") (part "TVS"))
    )
    (comp (ref "D55")
      (value "TVS")
      (footprint "eagle-import:0603")
      (libsource (lib "eagle-import") (part "TVS"))
    )
    (comp (ref "D57")
      (value "TVS")
      (footprint "eagle-import:0603")
      (libsource (lib "eagle-import") (part "TVS"))
    )
    (comp (ref "D59")
      (value "TVS")
      (footprint "eagle-import:0603")
      (libsource (lib "eagle-import") (part "TVS"))
    )
    (comp (ref "IC12")
      (value "V2164SZ")
      (footprint "eagle-import:SOIC16N")
      (libsource (lib "eagle-import") (part "SSM2164S"))
    )
    (comp (ref "IC14")
      (value "OPA1679")
      (footprint "eagle-import:TSSOP14_065")
      (libsource (lib "eagle-import") (part "OPA1679PW"))
    )
    (comp (ref "IC16")
      (value "V2164SZ")
      (footprint "eagle-import:SOIC16N")
      (libsource (lib "eagle-import") (part "SSM2164S"))
    )
    (comp (ref "IC18")
      (value "OPA1679")
      (footprint "eagle-import:TSSOP14_065")
      (libsource (lib "eagle-import") (part "OPA1679PW"))
    )
    (comp (ref "IC19")
      (value "TL074")
      (footprint "eagle-import:TSSOP14_065")
      (libsource (lib "eagle-import") (part "TL074PW"))
    )
    (comp (ref "J1")
      (value "PJ301_THONKICONNTME")
      (footprint "eagle-import:WQP_PJ_301M_TME")
      (libsource (lib "eagle-import") (part "PJ301_THONKICONNTME"))
    )
    (comp (ref "J4")
      (value "PJ301_THONKICONNTME")
      (footprint "eagle-import:WQP_PJ_301M_TME")
      (libsource (lib "eagle-import") (part "PJ301_THONKICONNTME"))
    )
    (comp (ref "J5")
      (value "PJ301_THONKICONNTME")
      (footprint "eagle-import:WQP_PJ_301M_TME")
      (libsource (lib "eagle-import") (part "PJ301_THONKICONNTME"))
    )
    (comp (ref "J11")
      (value "PJ301_THONKICONNTME")
      (footprint "eagle-import:WQP_PJ_301M_TME")
      (libsource (lib "eagle-import") (part "PJ301_THONKICONNTME"))
    )
    (comp (ref "J12")
      (value "PJ301_THONKICONNTME")
      (footprint "eagle-import:WQP_PJ_301M_TME")
      (libsource (lib "eagle-import") (part "PJ301_THONKICONNTME"))
    )
    (comp (ref "R14")
      (value "10kB")
      (footprint "eagle-import:ALPS_POT_VERTICAL_PS")
      (libsource (lib "eagle-import") (part "pot-alps_POT_USVERTICAL_PS"))
    )
    (comp (ref "R84")
      (value "680k")
      (footprint "eagle-import:R0402")
      (libsource (lib "eagle-import") (part "R-US_R0402"))
    )
    (comp (ref "R86")
      (value "10kB")
      (footprint "eagle-import:ALPS_POT_VERTICAL_PS")
      (libsource (lib "eagle-import") (part "pot-alps_POT_USVERTICAL_PS"))
    )
    (comp (ref "R92")
      (value "200.0k")
      (footprint "eagle-import:R0402")
      (libsource (lib "eagle-import") (part "R-US_R0402"))
    )
    (comp (ref "R94")
      (value "510")
      (footprint "eagle-import:R0402")
      (libsource (lib "eagle-import") (part "R-US_R0402"))
    )
    (comp (ref "R96")
      (value "62.0k")
      (footprint "eagle-import:R0402")
      (libsource (lib "eagle-import") (part "R-US_R0402"))
    )
    (comp (ref "R98")
      (value "62.0k")
      (footprint "eagle-import:R0402")
      (libsource (lib "eagle-import") (part "R-US_R0402"))
    )
    (comp (ref "R100")
      (value "510")
      (footprint "eagle-import:R0402")
      (libsource (lib "eagle-import") (part "R-US_R0402"))
    )
    (comp (ref "R102")
      (value "510")
      (footprint "eagle-import:R0402")
      (libsource (lib "eagle-import") (part "R-US_R0402"))
    )
    (comp (ref "R104")
      (value "30.0k")
      (footprint "eagle-import:R0402")
      (libsource (lib "eagle-import") (part "R-US_R0402"))
    )
    (comp (ref "R105")
      (value "510")
      (footprint "eagle-import:R0402")
      (libsource (lib "eagle-import") (part "R-US_R0402"))
    )
    (comp (ref "R108")
      (value "200.0k")
      (footprint "eagle-import:R0402")
      (libsource (lib "eagle-import") (part "R-US_R0402"))
    )
    (comp (ref "R110")
      (value "30k")
      (footprint "eagle-import:R0402")
      (libsource (lib "eagle-import") (part "R-US_R0402"))
    )
    (comp (ref "R111")
      (value "62.0k")
      (footprint "eagle-import:R0402")
      (libsource (lib "eagle-import") (part "R-US_R0402"))
    )
    (comp (ref "R114")
      (value "30k")
      (footprint "eagle-import:R0402")
      (libsource (lib "eagle-import") (part "R-US_R0402"))
    )
    (comp (ref "R115")
      (value "30k")
      (footprint "eagle-import:R0402")
      (libsource (lib "eagle-import") (part "R-US_R0402"))
    )
    (comp (ref "R116")
      (value "30.0k")
      (footprint "eagle-import:R0402")
      (libsource (lib "eagle-import") (part "R-US_R0402"))
    )
    (comp (ref "R118")
      (value "62.0k")
      (footprint "eagle-import:R0402")
      (libsource (lib "eagle-import") (part "R-US_R0402"))
    )
    (comp (ref "R122")
      (value "300k")
      (footprint "eagle-import:R0402")
      (libsource (lib "eagle-import") (part "R-US_R0402"))
    )
    (comp (ref "R125")
      (value "680k")
      (footprint "eagle-import:R0402")
      (libsource (lib "eagle-import") (part "R-US_R0402"))
    )
    (comp (ref "R127")
      (value "10kB")
      (footprint "eagle-import:ALPS_POT_VERTICAL_PS")
      (libsource (lib "eagle-import") (part "pot-alps_POT_USVERTICAL_PS"))
    )
    (comp (ref "R131")
      (value "30k")
      (footprint "eagle-import:R0402")
      (libsource (lib "eagle-import") (part "R-US_R0402"))
    )
    (comp (ref "R132")
      (value "30k")
      (footprint "eagle-import:R0402")
      (libsource (lib "eagle-import") (part "R-US_R0402"))
    )
    (comp (ref "R134")
      (value "510")
      (footprint "eagle-import:R0402")
      (libsource (lib "eagle-import") (part "R-US_R0402"))
    )
    (comp (ref "R136")
      (value "510")
      (footprint "eagle-import:R0402")
      (libsource (lib "eagle-import") (part "R-US_R0402"))
    )
    (comp (ref "R138")
      (value "510")
      (footprint "eagle-import:R0402")
      (libsource (lib "eagle-import") (part "R-US_R0402"))
    )
    (comp (ref "R142")
      (value "15k")
      (footprint "eagle-import:R0402")
      (libsource (lib "eagle-import") (part "R-US_R0402"))
    )
    (comp (ref "R143")
      (value "100.0k")
      (footprint "eagle-import:R0402")
      (libsource (lib "eagle-import") (part "R-US_R0402"))
    )
    (comp (ref "R146")
      (value "200.0k")
      (footprint "eagle-import:R0402")
      (libsource (lib "eagle-import") (part "R-US_R0402"))
    )
    (comp (ref "R147")
      (value "30.0k")
      (footprint "eagle-import:R0402")
      (libsource (lib "eagle-import") (part "R-US_R0402"))
    )
    (comp (ref "R148")
      (value "20k")
      (footprint "eagle-import:R0402")
      (libsource (lib "eagle-import") (part "R-US_R0402"))
    )
    (comp (ref "R151")
      (value "100.0k")
      (footprint "eagle-import:R0402")
      (libsource (lib "eagle-import") (part "R-US_R0402"))
    )
    (comp (ref "R153")
      (value "120k")
      (footprint "eagle-import:R0402")
      (libsource (lib "eagle-import") (part "R-US_R0402"))
    )
    (comp (ref "R155")
      (value "100k")
      (footprint "eagle-import:R0402")
      (libsource (lib "eagle-import") (part "R-US_R0402"))
    )
    (comp (ref "R156")
      (value "44.2k")
      (footprint "eagle-import:R0402")
      (libsource (lib "eagle-import") (part "R-US_R0402"))
    )
    (comp (ref "R160")
      (value "100.0k")
      (footprint "eagle-import:R0402")
      (libsource (lib "eagle-import") (part "R-US_R0402"))
    )
    (comp (ref "R161")
      (value "100.0k")
      (footprint "eagle-import:R0402")
      (libsource (lib "eagle-import") (part "R-US_R0402"))
    )
    (comp (ref "R164")
      (value "20k")
      (footprint "eagle-import:R0402")
      (libsource (lib "eagle-import") (part "R-US_R0402"))
    )
    (comp (ref "R165")
      (value "30.0k")
      (footprint "eagle-import:R0402")
      (libsource (lib "eagle-import") (part "R-US_R0402"))
    )
    (comp (ref "R166")
      (value "30.0k")
      (footprint "eagle-import:R0402")
      (libsource (lib "eagle-import") (part "R-US_R0402"))
    )
    (comp (ref "R167")
      (value "20k")
      (footprint "eagle-import:R0402")
      (libsource (lib "eagle-import") (part "R-US_R0402"))
    )
    (comp (ref "R170")
      (value "10M")
      (footprint "eagle-import:R0402")
      (libsource (lib "eagle-import") (part "R-US_R0402"))
    )
    (comp (ref "R173")
      (value "62.0k")
      (footprint "eagle-import:R0402")
      (libsource (lib "eagle-import") (part "R-US_R0402"))
    )
    (comp (ref "R176")
      (value "100.0k")
      (footprint "eagle-import:R0402")
      (libsource (lib "eagle-import") (part "R-US_R0402"))
    )
    (comp (ref "R177")
      (value "10kB")
      (footprint "eagle-import:ALPS_POT_NARROW")
      (libsource (lib "eagle-import") (part "POT_USVERTICAL_NARROW"))
    )
    (comp (ref "R178")
      (value "10kB")
      (footprint "eagle-import:ALPS_POT_NARROW")
      (libsource (lib "eagle-import") (part "POT_USVERTICAL_NARROW"))
    )
    (comp (ref "R183")
      (value "100.0k")
      (footprint "eagle-import:R0402")
      (libsource (lib "eagle-import") (part "R-US_R0402"))
    )
    (comp (ref "R184")
      (value "DNP")
      (footprint "eagle-import:R0603")
      (libsource (lib "eagle-import") (part "R-US_R0603"))
    )
    (comp (ref "R185")
      (value "100k")
      (footprint "eagle-import:R0402")
      (libsource (lib "eagle-import") (part "R-US_R0402"))
    )
    (comp (ref "R191")
      (value "1.0k")
      (footprint "eagle-import:R0603")
      (libsource (lib "eagle-import") (part "R-US_R0603"))
    )
    (comp (ref "R196")
      (value "2k")
      (footprint "eagle-import:RTRIM3296W")
      (libsource (lib "eagle-import") (part "R-TRIMM3296W"))
    )
    (comp (ref "C3")
      (value "100n")
      (footprint "eagle-import:C0402")
      (libsource (lib "eagle-import") (part "C-USC0402"))
    )
    (comp (ref "C4")
      (value "100n")
      (footprint "eagle-import:C0402")
      (libsource (lib "eagle-import") (part "C-USC0402"))
    )
    (comp (ref "C38")
      (value "100n")
      (footprint "eagle-import:C0402")
      (libsource (lib "eagle-import") (part "C-USC0402"))
    )
    (comp (ref "C39")
      (value "100n")
      (footprint "eagle-import:C0402")
      (libsource (lib "eagle-import") (part "C-USC0402"))
    )
    (comp (ref "C42")
      (value "100n")
      (footprint "eagle-import:C0402")
      (libsource (lib "eagle-import") (part "C-USC0402"))
    )
    (comp (ref "C43")
      (value "100n")
      (footprint "eagle-import:C0402")
      (libsource (lib "eagle-import") (part "C-USC0402"))
    )
    (comp (ref "C44")
      (value "22u")
      (footprint "eagle-import:C1206")
      (libsource (lib "eagle-import") (part "C-USC1206"))
    )
    (comp (ref "C45")
      (value "22u")
      (footprint "eagle-import:C1206")
      (libsource (lib "eagle-import") (part "C-USC1206"))
    )
    (comp (ref "C52")
      (value "22u")
      (footprint "eagle-import:C1206")
      (libsource (lib "eagle-import") (part "C-USC1206"))
    )
    (comp (ref "C53")
      (value "22u")
      (footprint "eagle-import:C1206")
      (libsource (lib "eagle-import") (part "C-USC1206"))
    )
    (comp (ref "C54")
      (value "22u")
      (footprint "eagle-import:PANASONIC_B")
      (libsource (lib "eagle-import") (part "CPOL-USB"))
    )
    (comp (ref "C55")
      (value "22u")
      (footprint "eagle-import:PANASONIC_B")
      (libsource (lib "eagle-import") (part "CPOL-USB"))
    )
    (comp (ref "D19")
      (value "1N5819HW")
      (footprint "eagle-import:SOD123")
      (libsource (lib "eagle-import") (part "DIODE-SOD123"))
    )
    (comp (ref "D20")
      (value "1N5819HW")
      (footprint "eagle-import:SOD123")
      (libsource (lib "eagle-import") (part "DIODE-SOD123"))
    )
    (comp (ref "IC10")
      (value "LM4040B5")
      (footprint "eagle-import:DBZ_R-PDSO-G3")
      (libsource (lib "eagle-import") (part "LM4041DBZB12"))
    )
    (comp (ref "IC11")
      (value "LM4040B5")
      (footprint "eagle-import:DBZ_R-PDSO-G3")
      (libsource (lib "eagle-import") (part "LM4041DBZB12"))
    )
    (comp (ref "JP1")
      (value "M05X2SHD")
      (footprint "eagle-import:2X5-SHROUDED")
      (libsource (lib "eagle-import") (part "M05X2SHD"))
    )
    (comp (ref "L1")
      (value "742792664")
      (footprint "eagle-import:0603")
      (libsource (lib "eagle-import") (part "WE-CBF_0603"))
    )
    (comp (ref "L2")
      (value "742792664")
      (footprint "eagle-import:0603")
      (libsource (lib "eagle-import") (part "WE-CBF_0603"))
    )
    (comp (ref "P1")
      (value "PTCSMD")
      (footprint "eagle-import:PTC-1206")
      (libsource (lib "eagle-import") (part "PTCSMD"))
    )
    (comp (ref "R82")
      (value "1.8k")
      (footprint "eagle-import:R0402")
      (libsource (lib "eagle-import") (part "R-US_R0402"))
    )
    (comp (ref "R83")
      (value "1.8k")
      (footprint "eagle-import:R0402")
      (libsource (lib "eagle-import") (part "R-US_R0402"))
    )
    (comp (ref "C2")
      (value "100n")
      (footprint "eagle-import:C0402")
      (libsource (lib "eagle-import") (part "C-USC0402"))
    )
    (comp (ref "C5")
      (value "18p")
      (footprint "eagle-import:C0402")
      (libsource (lib "eagle-import") (part "C-USC0402"))
    )
    (comp (ref "C7")
      (value "100n")
      (footprint "eagle-import:C0402")
      (libsource (lib "eagle-import") (part "C-USC0402"))
    )
    (comp (ref "C9")
      (value "220p")
      (footprint "eagle-import:C0402")
      (libsource (lib "eagle-import") (part "C-USC0402"))
    )
    (comp (ref "C13")
      (value "18p")
      (footprint "eagle-import:C0402")
      (libsource (lib "eagle-import") (part "C-USC0402"))
    )
    (comp (ref "C15")
      (value "100n")
      (footprint "eagle-import:C0402")
      (libsource (lib "eagle-import") (part "C-USC0402"))
    )
    (comp (ref "C18")
      (value "560p")
      (footprint "eagle-import:C0402")
      (libsource (lib "eagle-import") (part "C-USC0402"))
    )
    (comp (ref "C20")
      (value "560p")
      (footprint "eagle-import:C0402")
      (libsource (lib "eagle-import") (part "C-USC0402"))
    )
    (comp (ref "C27")
      (value "100n")
      (footprint "eagle-import:C0402")
      (libsource (lib "eagle-import") (part "C-USC0402"))
    )
    (comp (ref "C31")
      (value "100n")
      (footprint "eagle-import:C0402")
      (libsource (lib "eagle-import") (part "C-USC0402"))
    )
    (comp (ref "C35")
      (value "100n")
      (footprint "eagle-import:C0402")
      (libsource (lib "eagle-import") (part "C-USC0402"))
    )
    (comp (ref "C80")
      (value "100n")
      (footprint "eagle-import:C0402")
      (libsource (lib "eagle-import") (part "C-USC0402"))
    )
    (comp (ref "D2")
      (value "1N4148")
      (footprint "eagle-import:SOD523")
      (libsource (lib "eagle-import") (part "DIODE-SOD523"))
    )
    (comp (ref "D3")
      (value "BZT585B5V1T")
      (footprint "eagle-import:SOD523")
      (libsource (lib "eagle-import") (part "DIODE-SOD523"))
    )
    (comp (ref "D6")
      (value "BZT585B5V1T")
      (footprint "eagle-import:SOD523")
      (libsource (lib "eagle-import") (part "DIODE-SOD523"))
    )
    (comp (ref "D12")
      (value "1N4148")
      (footprint "eagle-import:SOD523")
      (libsource (lib "eagle-import") (part "DIODE-SOD523"))
    )
    (comp (ref "D13")
      (value "1N4148")
      (footprint "eagle-import:SOD523")
      (libsource (lib "eagle-import") (part "DIODE-SOD523"))
    )
    (comp (ref "D16")
      (value "1N4148")
      (footprint "eagle-import:SOD523")
      (libsource (lib "eagle-import") (part "DIODE-SOD523"))
    )
    (comp (ref "D18")
      (value "1N4148")
      (footprint "eagle-import:SOD523")
      (libsource (lib "eagle-import") (part "DIODE-SOD523"))
    )
    (comp (ref "D51")
      (value "TVS")
      (footprint "eagle-import:0603")
      (libsource (lib "eagle-import") (part "TVS"))
    )
    (comp (ref "D52")
      (value "TVS")
      (footprint "eagle-import:0603")
      (libsource (lib "eagle-import") (part "TVS"))
    )
    (comp (ref "IC1")
      (value "OPA1679")
      (footprint "eagle-import:TSSOP14_065")
      (libsource (lib "eagle-import") (part "OPA1679PW"))
    )
    (comp (ref "IC7")
      (value "OPA1678")
      (footprint "eagle-import:VSSOP8")
      (libsource (lib "eagle-import") (part "OPA1678DGK"))
    )
    (comp (ref "J9")
      (value "PJ301_THONKICONNTME")
      (footprint "eagle-import:WQP_PJ_301M_TME")
      (libsource (lib "eagle-import") (part "PJ301_THONKICONNTME"))
    )
    (comp (ref "J16")
      (value "PJ301_THONKICONNTME")
      (footprint "eagle-import:WQP_PJ_301M_TME")
      (libsource (lib "eagle-import") (part "PJ301_THONKICONNTME"))
    )
    (comp (ref "LED2")
      (value "OSC54L3131A")
      (footprint "eagle-import:LED3MM")
      (libsource (lib "eagle-import") (part "LED3MM"))
    )
    (comp (ref "R2")
      (value "6.2k")
      (footprint "eagle-import:R0402")
      (libsource (lib "eagle-import") (part "R-US_R0402"))
    )
    (comp (ref "R4")
      (value "62.0k")
      (footprint "eagle-import:R0402")
      (libsource (lib "eagle-import") (part "R-US_R0402"))
    )
    (comp (ref "R6")
      (value "200.0k")
      (footprint "eagle-import:R0402")
      (libsource (lib "eagle-import") (part "R-US_R0402"))
    )
    (comp (ref "R8")
      (value "30k")
      (footprint "eagle-import:R0402")
      (libsource (lib "eagle-import") (part "R-US_R0402"))
    )
    (comp (ref "R9")
      (value "5.1k")
      (footprint "eagle-import:R0402")
      (libsource (lib "eagle-import") (part "R-US_R0402"))
    )
    (comp (ref "R13")
      (value "62.0k")
      (footprint "eagle-import:R0402")
      (libsource (lib "eagle-import") (part "R-US_R0402"))
    )
    (comp (ref "R18")
      (value "10kB")
      (footprint "eagle-import:ALPS_POT_VERTICAL_PS")
      (libsource (lib "eagle-import") (part "pot-alps_POT_USVERTICAL_PS"))
    )
    (comp (ref "R19")
      (value "100k")
      (footprint "eagle-import:R0402")
      (libsource (lib "eagle-import") (part "R-US_R0402"))
    )
    (comp (ref "R20")
      (value "10M")
      (footprint "eagle-import:R0402")
      (libsource (lib "eagle-import") (part "R-US_R0402"))
    )
    (comp (ref "R25")
      (value "30k")
      (footprint "eagle-import:R0402")
      (libsource (lib "eagle-import") (part "R-US_R0402"))
    )
    (comp (ref "R26")
      (value "5.1k")
      (footprint "eagle-import:R0402")
      (libsource (lib "eagle-import") (part "R-US_R0402"))
    )
    (comp (ref "R31")
      (value "6.2k")
      (footprint "eagle-import:R0402")
      (libsource (lib "eagle-import") (part "R-US_R0402"))
    )
    (comp (ref "R34")
      (value "30k")
      (footprint "eagle-import:R0402")
      (libsource (lib "eagle-import") (part "R-US_R0402"))
    )
    (comp (ref "R35")
      (value "100k")
      (footprint "eagle-import:R0402")
      (libsource (lib "eagle-import") (part "R-US_R0402"))
    )
    (comp (ref "R37")
      (value "510")
      (footprint "eagle-import:R0402")
      (libsource (lib "eagle-import") (part "R-US_R0402"))
    )
    (comp (ref "R38")
      (value "5.1k")
      (footprint "eagle-import:R0402")
      (libsource (lib "eagle-import") (part "R-US_R0402"))
    )
    (comp (ref "R39")
      (value "510")
      (footprint "eagle-import:R0402")
      (libsource (lib "eagle-import") (part "R-US_R0402"))
    )
    (comp (ref "R55")
      (value "100k")
      (footprint "eagle-import:R0402")
      (libsource (lib "eagle-import") (part "R-US_R0402"))
    )
    (comp (ref "R56")
      (value "30k")
      (footprint "eagle-import:R0402")
      (libsource (lib "eagle-import") (part "R-US_R0402"))
    )
    (comp (ref "R59")
      (value "100k")
      (footprint "eagle-import:R0402")
      (libsource (lib "eagle-import") (part "R-US_R0402"))
    )
    (comp (ref "R60")
      (value "100k")
      (footprint "eagle-import:R0402")
      (libsource (lib "eagle-import") (part "R-US_R0402"))
    )
    (comp (ref "R64")
      (value "100k")
      (footprint "eagle-import:R0402")
      (libsource (lib "eagle-import") (part "R-US_R0402"))
    )
    (comp (ref "R67")
      (value "100k")
      (footprint "eagle-import:R0402")
      (libsource (lib "eagle-import") (part "R-US_R0402"))
    )
    (comp (ref "R81")
      (value "10kA")
      (footprint "eagle-import:ALPS_POT_NARROW")
      (libsource (lib "eagle-import") (part "POT_USVERTICAL_NARROW"))
    )
    (comp (ref "R90")
      (value "5.1k")
      (footprint "eagle-import:R0402")
      (libsource (lib "eagle-import") (part "R-US_R0402"))
    )
    (comp (ref "R91")
      (value "30k")
      (footprint "eagle-import:R0402")
      (libsource (lib "eagle-import") (part "R-US_R0402"))
    )
    (comp (ref "R190")
      (value "120k")
      (footprint "eagle-import:R0402")
      (libsource (lib "eagle-import") (part "R-US_R0402"))
    )
    (comp (ref "R200")
      (value "300k")
      (footprint "eagle-import:R0402")
      (libsource (lib "eagle-import") (part "R-US_R0402"))
    )
  )
  (nets
    (net (code "1") (name "AREF_+5") (class "Default")
      (node (ref "C3") (pin "1") (pinfunction "1_1") (pintype "passive"))
      (node (ref "C39") (pin "1") (pinfunction "1_1") (pintype "passive"))
      (node (ref "C4") (pin "1") (pinfunction "1_1") (pintype "passive"))
      (node (ref "IC11") (pin "1") (pinfunction "C_1") (pintype "passive"))
      (node (ref "R127") (pin "P$1") (pinfunction "E_P$1") (pintype "passive"))
      (node (ref "R130") (pin "P$1") (pinfunction "E_P$1") (pintype "passive"))
      (node (ref "R17") (pin "P$1") (pinfunction "E_P$1") (pintype "passive"))
      (node (ref "R18") (pin "P$1") (pinfunction "E_P$1") (pintype "passive"))
      (node (ref "R182") (pin "2") (pinfunction "2_2") (pintype "passive"))
      (node (ref "R190") (pin "2") (pinfunction "2_2") (pintype "passive"))
      (node (ref "R28") (pin "1") (pinfunction "1_1") (pintype "passive"))
      (node (ref "R83") (pin "2") (pinfunction "2_2") (pintype "passive"))
    )
    (net (code "2") (name "AREF_-5") (class "Default")
      (node (ref "C38") (pin "1") (pinfunction "1_1") (pintype "passive"))
      (node (ref "C42") (pin "1") (pinfunction "1_1") (pintype "passive"))
      (node (ref "C43") (pin "1") (pinfunction "1_1") (pintype "passive"))
      (node (ref "IC10") (pin "2") (pinfunction "A_2") (pintype "passive"))
      (node (ref "R108") (pin "1") (pinfunction "1_1") (pintype "passive"))
      (node (ref "R109") (pin "1") (pinfunction "1_1") (pintype "passive"))
      (node (ref "R128") (pin "P$3") (pinfunction "A_P$3") (pintype "passive"))
      (node (ref "R14") (pin "P$1") (pinfunction "E_P$1") (pintype "passive"))
      (node (ref "R145") (pin "1") (pinfunction "1_1") (pintype "passive"))
      (node (ref "R146") (pin "1") (pinfunction "1_1") (pintype "passive"))
      (node (ref "R15") (pin "P$1") (pinfunction "E_P$1") (pintype "passive"))
      (node (ref "R169") (pin "1") (pinfunction "1_1") (pintype "passive"))
      (node (ref "R170") (pin "1") (pinfunction "1_1") (pintype "passive"))
      (node (ref "R20") (pin "1") (pinfunction "1_1") (pintype "passive"))
      (node (ref "R21") (pin "1") (pinfunction "1_1") (pintype "passive"))
      (node (ref "R32") (pin "1") (pinfunction "1_1") (pintype "passive"))
      (node (ref "R35") (pin "1") (pinfunction "1_1") (pintype "passive"))
      (node (ref "R52") (pin "1") (pinfunction "1_1") (pintype "passive"))
      (node (ref "R53") (pin "1") (pinfunction "1_1") (pintype "passive"))
      (node (ref "R54") (pin "1") (pinfunction "1_1") (pintype "passive"))
      (node (ref "R82") (pin "2") (pinfunction "2_2") (pintype "passive"))
      (node (ref "R86") (pin "P$3") (pinfunction "A_P$3") (pintype "passive"))
      (node (ref "R87") (pin "P$3") (pinfunction "A_P$3") (pintype "passive"))
      (node (ref "R92") (pin "1") (pinfunction "1_1") (pintype "passive"))
      (node (ref "R93") (pin "1") (pinfunction "1_1") (pintype "passive"))
    )
    (net (code "3") (name "BP_1") (class "Default")
      (node (ref "C62") (pin "2") (pinfunction "2_2") (pintype "passive"))
      (node (ref "D21") (pin "A") (pinfunction "A_A") (pintype "passive"))
      (node (ref "IC14") (pin "1") (pinfunction "OUT_1") (pintype "output"))
      (node (ref "R118") (pin "1") (pinfunction "1_1") (pintype "passive"))
      (node (ref "R122") (pin "2") (pinfunction "2_2") (pintype "passive"))
      (node (ref "R131") (pin "1") (pinfunction "1_1") (pintype "passive"))
      (node (ref "R142") (pin "1") (pinfunction "1_1") (pintype "passive"))
      (node (ref "R98") (pin "1") (pinfunction "1_1") (pintype "passive"))
    )
    (net (code "4") (name "BP_2") (class "Default")
      (node (ref "C65") (pin "2") (pinfunction "2_2") (pintype "passive"))
      (node (ref "D22") (pin "A") (pinfunction "A_A") (pintype "passive"))
      (node (ref "IC15") (pin "14") (pinfunction "OUT_14") (pintype "output"))
      (node (ref "R119") (pin "1") (pinfunction "1_1") (pintype "passive"))
      (node (ref "R123") (pin "2") (pinfunction "2_2") (pintype "passive"))
      (node (ref "R129") (pin "1") (pinfunction "1_1") (pintype "passive"))
      (node (ref "R141") (pin "1") (pinfunction "1_1") (pintype "passive"))
      (node (ref "R99") (pin "1") (pinfunction "1_1") (pintype "passive"))
    )
    (net (code "5") (name "F_CV_1_PRE") (class "Default")
      (node (ref "C90") (pin "2") (pinfunction "2_2") (pintype "passive"))
      (node (ref "D32") (pin "C") (pinfunction "C_C") (pintype "passive"))
      (node (ref "R147") (pin "2") (pinfunction "2_2") (pintype "passive"))
      (node (ref "R196") (pin "3") (pinfunction "A_3") (pintype "passive"))
      (node (ref "R62") (pin "1") (pinfunction "1_1") (pintype "passive"))
    )
    (net (code "6") (name "GND") (class "Default")
      (node (ref "C1") (pin "1") (pinfunction "1_1") (pintype "passive"))
      (node (ref "C14") (pin "2") (pinfunction "2_2") (pintype "passive"))
      (node (ref "C15") (pin "2") (pinfunction "2_2") (pintype "passive"))
      (node (ref "C16") (pin "1") (pinfunction "1_1") (pintype "passive"))
      (node (ref "C17") (pin "2") (pinfunction "2_2") (pintype "passive"))
      (node (ref "C18") (pin "2") (pinfunction "2_2") (pintype "passive"))
      (node (ref "C19") (pin "2") (pinfunction "2_2") (pintype "passive"))
      (node (ref "C2") (pin "2") (pinfunction "2_2") (pintype "passive"))
      (node (ref "C20") (pin "2") (pinfunction "2_2") (pintype "passive"))
      (node (ref "C21") (pin "2") (pinfunction "2_2") (pintype "passive"))
      (node (ref "C22") (pin "2") (pinfunction "2_2") (pintype "passive"))
      (node (ref "C25") (pin "2") (pinfunction "2_2") (pintype "passive"))
      (node (ref "C26") (pin "2") (pinfunction "2_2") (pintype "passive"))
      (node (ref "C27") (pin "2") (pinfunction "2_2") (pintype "passive"))
      (node (ref "C28") (pin "2") (pinfunction "2_2") (pintype "passive"))
      (node (ref "C29") (pin "2") (pinfunction "2_2") (pintype "passive"))
      (node (ref "C3") (pin "2") (pinfunction "2_2") (pintype "passive"))
      (node (ref "C30") (pin "1") (pinfunction "1_1") (pintype "passive"))
      (node (ref "C31") (pin "1") (pinfunction "1_1") (pintype "passive"))
      (node (ref "C34") (pin "1") (pinfunction "1_1") (pintype "passive"))
      (node (ref "C35") (pin "1") (pinfunction "1_1") (pintype "passive"))
      (node (ref "C36") (pin "2") (pinfunction "2_2") (pintype "passive"))
      (node (ref "C37") (pin "2") (pinfunction "2_2") (pintype "passive"))
      (node (ref "C38") (pin "2") (pinfunction "2_2") (pintype "passive"))
      (node (ref "C39") (pin "2") (pinfunction "2_2") (pintype "passive"))
      (node (ref "C4") (pin "2") (pinfunction "2_2") (pintype "passive"))
      (node (ref "C40") (pin "1") (pinfunction "1_1") (pintype "passive"))
      (node (ref "C41") (pin "1") (pinfunction "1_1") (pintype "passive"))
      (node (ref "C42") (pin "2") (pinfunction "2_2") (pintype "passive"))
      (node (ref "C43") (pin "2") (pinfunction "2_2") (pintype "passive"))
      (node (ref "C44") (pin "2") (pinfunction "2_2") (pintype "passive"))
      (node (ref "C45") (pin "2") (pinfunction "2_2") (pintype "passive"))
      (node (ref "C46") (pin "2") (pinfunction "2_2") (pintype "passive"))
      (node (ref "C47") (pin "2") (pinfunction "2_2") (pintype "passive"))
      (node (ref "C48") (pin "2") (pinfunction "2_2") (pintype "passive"))
      (node (ref "C49") (pin "2") (pinfunction "2_2") (pintype "passive"))
      (node (ref "C50") (pin "2") (pinfunction "2_2") (pintype "passive"))
      (node (ref "C51") (pin "2") (pinfunction "2_2") (pintype "passive"))
      (node (ref "C52") (pin "1") (pinfunction "1_1") (pintype "passive"))
      (node (ref "C53") (pin "1") (pinfunction "1_1") (pintype "passive"))
      (node (ref "C54") (pin "+") (pinfunction "+_+") (pintype "passive"))
      (node (ref "C55") (pin "-") (pinfunction "-_-") (pintype "passive"))
      (node (ref "C56") (pin "2") (pinfunction "2_2") (pintype "passive"))
      (node (ref "C57") (pin "2") (pinfunction "2_2") (pintype "passive"))
      (node (ref "C58") (pin "1") (pinfunction "1_1") (pintype "passive"))
      (node (ref "C59") (pin "1") (pinfunction "1_1") (pintype "passive"))
      (node (ref "C60") (pin "2") (pinfunction "2_2") (pintype "passive"))
      (node (ref "C61") (pin "2") (pinfunction "2_2") (pintype "passive"))
      (node (ref "C66") (pin "2") (pinfunction "2_2") (pintype "passive"))
      (node (ref "C67") (pin "1") (pinfunction "1_1") (pintype "passive"))
      (node (ref "C68") (pin "2") (pinfunction "2_2") (pintype "passive"))
      (node (ref "C69") (pin "1") (pinfunction "1_1") (pintype "passive"))
      (node (ref "C7") (pin "1") (pinfunction "1_1") (pintype "passive"))
      (node (ref "C70") (pin "2") (pinfunction "2_2") (pintype "passive"))
      (node (ref "C71") (pin "2") (pinfunction "2_2") (pintype "passive"))
      (node (ref "C74") (pin "2") (pinfunction "2_2") (pintype "passive"))
      (node (ref "C75") (pin "2") (pinfunction "2_2") (pintype "passive"))
      (node (ref "C76") (pin "2") (pinfunction "2_2") (pintype "passive"))
      (node (ref "C77") (pin "2") (pinfunction "2_2") (pintype "passive"))
      (node (ref "C78") (pin "2") (pinfunction "2_2") (pintype "passive"))
      (node (ref "C8") (pin "2") (pinfunction "2_2") (pintype "passive"))
      (node (ref "C81") (pin "2") (pinfunction "2_2") (pintype "passive"))
      (node (ref "C84") (pin "1") (pinfunction "1_1") (pintype "passive"))
      (node (ref "C85") (pin "1") (pinfunction "1_1") (pintype "passive"))
      (node (ref "C92") (pin "2") (pinfunction "2_2") (pintype "passive"))
      (node (ref "C93") (pin "1") (pinfunction "1_1") (pintype "passive"))
      (node (ref "C94") (pin "2") (pinfunction "2_2") (pintype "passive"))
      (node (ref "C95") (pin "1") (pinfunction "1_1") (pintype "passive"))
      (node (ref "C96") (pin "2") (pinfunction "2_2") (pintype "passive"))
      (node (ref "C97") (pin "1") (pinfunction "1_1") (pintype "passive"))
      (node (ref "C98") (pin "2") (pinfunction "2_2") (pintype "passive"))
      (node (ref "C99") (pin "1") (pinfunction "1_1") (pintype "passive"))
      (node (ref "D11") (pin "C") (pinfunction "C_C") (pintype "passive"))
      (node (ref "D12") (pin "A") (pinfunction "A_A") (pintype "passive"))
      (node (ref "D13") (pin "A") (pinfunction "A_A") (pintype "passive"))
      (node (ref "D14") (pin "C") (pinfunction "C_C") (pintype "passive"))
      (node (ref "D15") (pin "A") (pinfunction "A_A") (pintype "passive"))
      (node (ref "D16") (pin "C") (pinfunction "C_C") (pintype "passive"))
      (node (ref "D17") (pin "A") (pinfunction "A_A") (pintype "passive"))
      (node (ref "D18") (pin "C") (pinfunction "C_C") (pintype "passive"))
      (node (ref "D20") (pin "C") (pinfunction "C_C") (pintype "passive"))
      (node (ref "D49") (pin "1") (pinfunction "A_1") (pintype "passive"))
      (node (ref "D50") (pin "1") (pinfunction "A_1") (pintype "passive"))
      (node (ref "D51") (pin "1") (pinfunction "A_1") (pintype "passive"))
      (node (ref "D52") (pin "1") (pinfunction "A_1") (pintype "passive"))
      (node (ref "D53") (pin "1") (pinfunction "A_1") (pintype "passive"))
      (node (ref "D54") (pin "1") (pinfunction "A_1") (pintype "passive"))
      (node (ref "D55") (pin "1") (pinfunction "A_1") (pintype "passive"))
      (node (ref "D56") (pin "1") (pinfunction "A_1") (pintype "passive"))
      (node (ref "D57") (pin "1") (pinfunction "A_1") (pintype "passive"))
      (node (ref "D58") (pin "1") (pinfunction "A_1") (pintype "passive"))
      (node (ref "D59") (pin "1") (pinfunction "A_1") (pintype "passive"))
      (node (ref "D60") (pin "1") (pinfunction "A_1") (pintype "passive"))
      (node (ref "D61") (pin "1") (pinfunction "A_1") (pintype "passive"))
      (node (ref "IC1") (pin "10") (pinfunction "+IN_10") (pintype "input"))
      (node (ref "IC1") (pin "12") (pinfunction "+IN_12") (pintype "input"))
      (node (ref "IC1") (pin "5") (pinfunction "+IN_5") (pintype "input"))
      (node (ref "IC10") (pin "1") (pinfunction "C_1") (pintype "passive"))
      (node (ref "IC11") (pin "2") (pinfunction "A_2") (pintype "passive"))
      (node (ref "IC12") (pin "8") (pinfunction "GND_8") (pintype "power_in"))
      (node (ref "IC13") (pin "8") (pinfunction "GND_8") (pintype "power_in"))
      (node (ref "IC14") (pin "10") (pinfunction "+IN_10") (pintype "input"))
      (node (ref "IC14") (pin "12") (pinfunction "+IN_12") (pintype "input"))
      (node (ref "IC14") (pin "3") (pinfunction "+IN_3") (pintype "input"))
      (node (ref "IC14") (pin "5") (pinfunction "+IN_5") (pintype "input"))
      (node (ref "IC15") (pin "10") (pinfunction "+IN_10") (pintype "input"))
      (node (ref "IC15") (pin "12") (pinfunction "+IN_12") (pintype "input"))
      (node (ref "IC15") (pin "3") (pinfunction "+IN_3") (pintype "input"))
      (node (ref "IC15") (pin "5") (pinfunction "+IN_5") (pintype "input"))
      (node (ref "IC16") (pin "10") (pinfunction "IN_10") (pintype "input"))
      (node (ref "IC16") (pin "12") (pinfunction "OUT_12") (pintype "output"))
      (node (ref "IC16") (pin "8") (pinfunction "GND_8") (pintype "power_in"))
      (node (ref "IC17") (pin "5") (pinfunction "OUT_5") (pintype "output"))
      (node (ref "IC17") (pin "7") (pinfunction "IN_7") (pintype "input"))
      (node (ref "IC17") (pin "8") (pinfunction "GND_8") (pintype "power_in"))
      (node (ref "IC18") (pin "10") (pinfunction "+IN_10") (pintype "input"))
      (node (ref "IC18") (pin "12") (pinfunction "+IN_12") (pintype "input"))
      (node (ref "IC18") (pin "3") (pinfunction "+IN_3") (pintype "input"))
      (node (ref "IC18") (pin "5") (pinfunction "+IN_5") (pintype "input"))
      (node (ref "IC19") (pin "10") (pinfunction "+IN_10") (pintype "input"))
      (node (ref "IC19") (pin "12") (pinfunction "+IN_12") (pintype "input"))
      (node (ref "IC19") (pin "3") (pinfunction "+IN_3") (pintype "input"))
      (node (ref "IC19") (pin "5") (pinfunction "+IN_5") (pintype "input"))
      (node (ref "IC2") (pin "10") (pinfunction "+IN_10") (pintype "input"))
      (node (ref "IC2") (pin "3") (pinfunction "+IN_3") (pintype "input"))
      (node (ref "IC2") (pin "5") (pinfunction "+IN_5") (pintype "input"))
      (node (ref "IC20") (pin "10") (pinfunction "+IN_10") (pintype "input"))
      (node (ref "IC20") (pin "12") (pinfunction "+IN_12") (pintype "input"))
      (node (ref "IC20") (pin "3") (pinfunction "+IN_3") (pintype "input"))
      (node (ref "IC20") (pin "5") (pinfunction "+IN_5") (pintype "input"))
      (node (ref "IC21") (pin "10") (pinfunction "+IN_10") (pintype "input"))
      (node (ref "IC21") (pin "12") (pinfunction "+IN_12") (pintype "input"))
      (node (ref "IC21") (pin "3") (pinfunction "+IN_3") (pintype "input"))
      (node (ref "IC21") (pin "5") (pinfunction "+IN_5") (pintype "input"))
      (node (ref "IC3") (pin "10") (pinfunction "+IN_10") (pintype "input"))
      (node (ref "IC3") (pin "12") (pinfunction "+IN_12") (pintype "input"))
      (node (ref "IC3") (pin "3") (pinfunction "+IN_3") (pintype "input"))
      (node (ref "IC3") (pin "5") (pinfunction "+IN_5") (pintype "input"))
      (node (ref "IC4") (pin "8") (pinfunction "GND_8") (pintype "power_in"))
      (node (ref "IC5") (pin "8") (pinfunction "GND_8") (pintype "power_in"))
      (node (ref "IC8") (pin "10") (pinfunction "+IN_10") (pintype "input"))
      (node (ref "IC8") (pin "12") (pinfunction "+IN_12") (pintype "input"))
      (node (ref "IC8") (pin "3") (pinfunction "+IN_3") (pintype "input"))
      (node (ref "IC8") (pin "5") (pinfunction "+IN_5") (pintype "input"))
      (node (ref "IC9") (pin "3") (pinfunction "+IN_3") (pintype "input"))
      (node (ref "IC9") (pin "5") (pinfunction "+IN_5") (pintype "input"))
      (node (ref "J1") (pin "P1") (pinfunction "1_P1") (pintype "passive"))
      (node (ref "J1") (pin "P2") (pinfunction "2_P2") (pintype "passive"))
      (node (ref "J10") (pin "P1") (pinfunction "1_P1") (pintype "passive"))
      (node (ref "J10") (pin "P2") (pinfunction "2_P2") (pintype "passive"))
      (node (ref "J11") (pin "P1") (pinfunction "1_P1") (pintype "passive"))
      (node (ref "J11") (pin "P2") (pinfunction "2_P2") (pintype "passive"))
      (node (ref "J12") (pin "P1") (pinfunction "1_P1") (pintype "passive"))
      (node (ref "J13") (pin "P1") (pinfunction "1_P1") (pintype "passive"))
      (node (ref "J14") (pin "P1") (pinfunction "1_P1") (pintype "passive"))
      (node (ref "J15") (pin "P1") (pinfunction "1_P1") (pintype "passive"))
      (node (ref "J15") (pin "P2") (pinfunction "2_P2") (pintype "passive"))
      (node (ref "J16") (pin "P1") (pinfunction "1_P1") (pintype "passive"))
      (node (ref "J2") (pin "P1") (pinfunction "1_P1") (pintype "passive"))
      (node (ref "J2") (pin "P2") (pinfunction "2_P2") (pintype "passive"))
      (node (ref "J3") (pin "P1") (pinfunction "1_P1") (pintype "passive"))
      (node (ref "J4") (pin "P1") (pinfunction "1_P1") (pintype "passive"))
      (node (ref "J5") (pin "P1") (pinfunction "1_P1") (pintype "passive"))
      (node (ref "J5") (pin "P2") (pinfunction "2_P2") (pintype "passive"))
      (node (ref "J6") (pin "P1") (pinfunction "1_P1") (pintype "passive"))
      (node (ref "J6") (pin "P2") (pinfunction "2_P2") (pintype "passive"))
      (node (ref "J7") (pin "P1") (pinfunction "1_P1") (pintype "passive"))
      (node (ref "J7") (pin "P2") (pinfunction "2_P2") (pintype "passive"))
      (node (ref "J8") (pin "P1") (pinfunction "1_P1") (pintype "passive"))
      (node (ref "J9") (pin "P1") (pinfunction "1_P1") (pintype "passive"))
      (node (ref "JP1") (pin "3") (pinfunction "3_3") (pintype "passive"))
      (node (ref "JP1") (pin "4") (pinfunction "4_4") (pintype "passive"))
      (node (ref "JP1") (pin "5") (pinfunction "5_5") (pintype "passive"))
      (node (ref "JP1") (pin "6") (pinfunction "6_6") (pintype "passive"))
      (node (ref "JP1") (pin "7") (pinfunction "7_7") (pintype "passive"))
      (node (ref "JP1") (pin "8") (pinfunction "8_8") (pintype "passive"))
      (node (ref "R1") (pin "2") (pinfunction "2_2") (pintype "passive"))
      (node (ref "R127") (pin "P$3") (pinfunction "A_P$3") (pintype "passive"))
      (node (ref "R128") (pin "P$1") (pinfunction "E_P$1") (pintype "passive"))
      (node (ref "R130") (pin "P$3") (pinfunction "A_P$3") (pintype "passive"))
      (node (ref "R14") (pin "P$3") (pinfunction "A_P$3") (pintype "passive"))
      (node (ref "R15") (pin "P$3") (pinfunction "A_P$3") (pintype "passive"))
      (node (ref "R17") (pin "P$3") (pinfunction "A_P$3") (pintype "passive"))
      (node (ref "R18") (pin "P$3") (pinfunction "A_P$3") (pintype "passive"))
      (node (ref "R199") (pin "1") (pinfunction "1_1") (pintype "passive"))
      (node (ref "R2") (pin "2") (pinfunction "2_2") (pintype "passive"))
      (node (ref "R200") (pin "1") (pinfunction "1_1") (pintype "passive"))
      (node (ref "R38") (pin "1") (pinfunction "1_1") (pintype "passive"))
      (node (ref "R41") (pin "1") (pinfunction "1_1") (pintype "passive"))
      (node (ref "R63") (pin "2") (pinfunction "2_2") (pintype "passive"))
      (node (ref "R80") (pin "P$2") (pinfunction "S_P$2") (pintype "passive"))
      (node (ref "R81") (pin "P$2") (pinfunction "S_P$2") (pintype "passive"))
      (node (ref "R86") (pin "P$1") (pinfunction "E_P$1") (pintype "passive"))
      (node (ref "R87") (pin "P$1") (pinfunction "E_P$1") (pintype "passive"))
      (node (ref "SW1") (pin "L2") (pinfunction "L2_L2") (pintype "passive"))
    )
    (net (code "7") (name "HP_1") (class "Default")
      (node (ref "IC14") (pin "7") (pinfunction "OUT_7") (pintype "output"))
      (node (ref "R115") (pin "2") (pinfunction "2_2") (pintype "passive"))
      (node (ref "R132") (pin "1") (pinfunction "1_1") (pintype "passive"))
      (node (ref "R96") (pin "1") (pinfunction "1_1") (pintype "passive"))
    )
    (net (code "8") (name "HP_2") (class "Default")
      (node (ref "IC15") (pin "8") (pinfunction "OUT_8") (pintype "output"))
      (node (ref "R117") (pin "2") (pinfunction "2_2") (pintype "passive"))
      (node (ref "R126") (pin "1") (pinfunction "1_1") (pintype "passive"))
      (node (ref "R97") (pin "1") (pinfunction "1_1") (pintype "passive"))
    )
    (net (code "9") (name "IN_1") (class "Default")
      (node (ref "C6") (pin "2") (pinfunction "2_2") (pintype "passive"))
      (node (ref "C79") (pin "1") (pinfunction "1_1") (pintype "passive"))
      (node (ref "IC2") (pin "1") (pinfunction "OUT_1") (pintype "output"))
      (node (ref "R114") (pin "1") (pinfunction "1_1") (pintype "passive"))
      (node (ref "R5") (pin "2") (pinfunction "2_2") (pintype "passive"))
    )
    (net (code "10") (name "IN_2") (class "Default")
      (node (ref "C5") (pin "2") (pinfunction "2_2") (pintype "passive"))
      (node (ref "C80") (pin "1") (pinfunction "1_1") (pintype "passive"))
      (node (ref "IC1") (pin "14") (pinfunction "OUT_14") (pintype "output"))
      (node (ref "R121") (pin "1") (pinfunction "1_1") (pintype "passive"))
      (node (ref "R6") (pin "2") (pinfunction "2_2") (pintype "passive"))
    )
    (net (code "11") (name "IN_2_NORMALIZATION") (class "Default")
      (node (ref "J16") (pin "P2") (pinfunction "2_P2") (pintype "passive"))
      (node (ref "R194") (pin "2") (pinfunction "2_2") (pintype "passive"))
    )
    (net (code "12") (name "LP_1") (class "Default")
      (node (ref "C63") (pin "2") (pinfunction "2_2") (pintype "passive"))
      (node (ref "C72") (pin "2") (pinfunction "2_2") (pintype "passive"))
      (node (ref "IC14") (pin "14") (pinfunction "OUT_14") (pintype "output"))
      (node (ref "R110") (pin "2") (pinfunction "2_2") (pintype "passive"))
      (node (ref "R111") (pin "1") (pinfunction "1_1") (pintype "passive"))
      (node (ref "R173") (pin "1") (pinfunction "1_1") (pintype "passive"))
    )
    (net (code "13") (name "LP_2") (class "Default")
      (node (ref "C64") (pin "2") (pinfunction "2_2") (pintype "passive"))
      (node (ref "C73") (pin "2") (pinfunction "2_2") (pintype "passive"))
      (node (ref "IC15") (pin "1") (pinfunction "OUT_1") (pintype "output"))
      (node (ref "R112") (pin "1") (pinfunction "1_1") (pintype "passive"))
      (node (ref "R113") (pin "2") (pinfunction "2_2") (pintype "passive"))
      (node (ref "R174") (pin "1") (pinfunction "1_1") (pintype "passive"))
    )
    (net (code "14") (name "MORPH_CV_1") (class "Default")
      (node (ref "D53") (pin "2") (pinfunction "C_2") (pintype "passive"))
      (node (ref "J1") (pin "P3") (pinfunction "3_P3") (pintype "passive"))
      (node (ref "R151") (pin "1") (pinfunction "1_1") (pintype "passive"))
      (node (ref "R160") (pin "1") (pinfunction "1_1") (pintype "passive"))
    )
    (net (code "15") (name "MORPH_CV_2") (class "Default")
      (node (ref "D54") (pin "2") (pinfunction "C_2") (pintype "passive"))
      (node (ref "J2") (pin "P3") (pinfunction "3_P3") (pintype "passive"))
      (node (ref "R152") (pin "1") (pinfunction "1_1") (pintype "passive"))
      (node (ref "R159") (pin "1") (pinfunction "1_1") (pintype "passive"))
    )
    (net (code "16") (name "MORPH_POT_1") (class "Default")
      (node (ref "R127") (pin "P$2") (pinfunction "S_P$2") (pintype "passive"))
      (node (ref "R143") (pin "1") (pinfunction "1_1") (pintype "passive"))
      (node (ref "R176") (pin "1") (pinfunction "1_1") (pintype "passive"))
    )
    (net (code "17") (name "MORPH_POT_2") (class "Default")
      (node (ref "R130") (pin "P$2") (pinfunction "S_P$2") (pintype "passive"))
      (node (ref "R144") (pin "1") (pinfunction "1_1") (pintype "passive"))
      (node (ref "R175") (pin "1") (pinfunction "1_1") (pintype "passive"))
    )
    (net (code "18") (name "Net-(C18-Pad1)") (class "Default")
      (node (ref "C18") (pin "1") (pinfunction "1_1") (pintype "passive"))
      (node (ref "R37") (pin "1") (pinfunction "1_1") (pintype "passive"))
    )
    (net (code "19") (name "Net-(C19-Pad1)") (class "Default")
      (node (ref "C19") (pin "1") (pinfunction "1_1") (pintype "passive"))
      (node (ref "R45") (pin "1") (pinfunction "1_1") (pintype "passive"))
    )
    (net (code "20") (name "Net-(C20-Pad1)") (class "Default")
      (node (ref "C20") (pin "1") (pinfunction "1_1") (pintype "passive"))
      (node (ref "R39") (pin "1") (pinfunction "1_1") (pintype "passive"))
    )
    (net (code "21") (name "Net-(C21-Pad1)") (class "Default")
      (node (ref "C21") (pin "1") (pinfunction "1_1") (pintype "passive"))
      (node (ref "R36") (pin "1") (pinfunction "1_1") (pintype "passive"))
    )
    (net (code "22") (name "Net-(C22-Pad1)") (class "Default")
      (node (ref "C22") (pin "1") (pinfunction "1_1") (pintype "passive"))
      (node (ref "R40") (pin "1") (pinfunction "1_1") (pintype "passive"))
    )
    (net (code "23") (name "Net-(C25-Pad1)") (class "Default")
      (node (ref "C25") (pin "1") (pinfunction "1_1") (pintype "passive"))
      (node (ref "R48") (pin "1") (pinfunction "1_1") (pintype "passive"))
    )
    (net (code "24") (name "Net-(C26-Pad1)") (class "Default")
      (node (ref "C26") (pin "1") (pinfunction "1_1") (pintype "passive"))
      (node (ref "R49") (pin "1") (pinfunction "1_1") (pintype "passive"))
    )
    (net (code "25") (name "Net-(C28-Pad1)") (class "Default")
      (node (ref "C28") (pin "1") (pinfunction "1_1") (pintype "passive"))
      (node (ref "R47") (pin "1") (pinfunction "1_1") (pintype "passive"))
    )
    (net (code "26") (name "Net-(C48-Pad1)") (class "Default")
      (node (ref "C48") (pin "1") (pinfunction "1_1") (pintype "passive"))
      (node (ref "R95") (pin "1") (pinfunction "1_1") (pintype "passive"))
    )
    (net (code "27") (name "Net-(C49-Pad1)") (class "Default")
      (node (ref "C49") (pin "1") (pinfunction "1_1") (pintype "passive"))
      (node (ref "R94") (pin "1") (pinfunction "1_1") (pintype "passive"))
    )
    (net (code "28") (name "Net-(C50-Pad1)") (class "Default")
      (node (ref "C50") (pin "1") (pinfunction "1_1") (pintype "passive"))
      (node (ref "R100") (pin "1") (pinfunction "1_1") (pintype "passive"))
    )
    (net (code "29") (name "Net-(C51-Pad1)") (class "Default")
      (node (ref "C51") (pin "1") (pinfunction "1_1") (pintype "passive"))
      (node (ref "R101") (pin "1") (pinfunction "1_1") (pintype "passive"))
    )
    (net (code "30") (name "Net-(C56-Pad1)") (class "Default")
      (node (ref "C56") (pin "1") (pinfunction "1_1") (pintype "passive"))
      (node (ref "R102") (pin "1") (pinfunction "1_1") (pintype "passive"))
    )
    (net (code "31") (name "Net-(C57-Pad1)") (class "Default")
      (node (ref "C57") (pin "1") (pinfunction "1_1") (pintype "passive"))
      (node (ref "R103") (pin "1") (pinfunction "1_1") (pintype "passive"))
    )
    (net (code "32") (name "Net-(C60-Pad1)") (class "Default")
      (node (ref "C60") (pin "1") (pinfunction "1_1") (pintype "passive"))
      (node (ref "R107") (pin "1") (pinfunction "1_1") (pintype "passive"))
    )
    (net (code "33") (name "Net-(C61-Pad1)") (class "Default")
      (node (ref "C61") (pin "1") (pinfunction "1_1") (pintype "passive"))
      (node (ref "R105") (pin "1") (pinfunction "1_1") (pintype "passive"))
    )
    (net (code "34") (name "Net-(C74-Pad1)") (class "Default")
      (node (ref "C74") (pin "1") (pinfunction "1_1") (pintype "passive"))
      (node (ref "R133") (pin "1") (pinfunction "1_1") (pintype "passive"))
    )
    (net (code "35") (name "Net-(C75-Pad1)") (class "Default")
      (node (ref "C75") (pin "1") (pinfunction "1_1") (pintype "passive"))
      (node (ref "R134") (pin "1") (pinfunction "1_1") (pintype "passive"))
    )
    (net (code "36") (name "Net-(C76-Pad1)") (class "Default")
      (node (ref "C76") (pin "1") (pinfunction "1_1") (pintype "passive"))
      (node (ref "R135") (pin "1") (pinfunction "1_1") (pintype "passive"))
    )
    (net (code "37") (name "Net-(C77-Pad1)") (class "Default")
      (node (ref "C77") (pin "1") (pinfunction "1_1") (pintype "passive"))
      (node (ref "R136") (pin "1") (pinfunction "1_1") (pintype "passive"))
    )
    (net (code "38") (name "Net-(C78-Pad1)") (class "Default")
      (node (ref "C78") (pin "1") (pinfunction "1_1") (pintype "passive"))
      (node (ref "R137") (pin "1") (pinfunction "1_1") (pintype "passive"))
    )
    (net (code "39") (name "Net-(C79-Pad2)") (class "Default")
      (node (ref "C79") (pin "2") (pinfunction "2_2") (pintype "passive"))
      (node (ref "R199") (pin "2") (pinfunction "2_2") (pintype "passive"))
      (node (ref "R7") (pin "1") (pinfunction "1_1") (pintype "passive"))
    )
    (net (code "40") (name "Net-(C80-Pad2)") (class "Default")
      (node (ref "C80") (pin "2") (pinfunction "2_2") (pintype "passive"))
      (node (ref "R200") (pin "2") (pinfunction "2_2") (pintype "passive"))
      (node (ref "R8") (pin "1") (pinfunction "1_1") (pintype "passive"))
    )
    (net (code "41") (name "Net-(C81-Pad1)") (class "Default")
      (node (ref "C81") (pin "1") (pinfunction "1_1") (pintype "passive"))
      (node (ref "R138") (pin "1") (pinfunction "1_1") (pintype "passive"))
    )
    (net (code "42") (name "Net-(D3-PadC)") (class "Default")
      (node (ref "D3") (pin "C") (pinfunction "C_C") (pintype "passive"))
      (node (ref "D6") (pin "C") (pinfunction "C_C") (pintype "passive"))
    )
    (net (code "43") (name "Net-(D4-PadC)") (class "Default")
      (node (ref "D4") (pin "C") (pinfunction "C_C") (pintype "passive"))
      (node (ref "D5") (pin "C") (pinfunction "C_C") (pintype "passive"))
    )
    (net (code "44") (name "Net-(D19-PadA)") (class "Default")
      (node (ref "D19") (pin "A") (pinfunction "A_A") (pintype "passive"))
      (node (ref "JP1") (pin "10") (pinfunction "10_10") (pintype "passive"))
      (node (ref "JP1") (pin "9") (pinfunction "9_9") (pintype "passive"))
    )
    (net (code "45") (name "Net-(D19-PadC)") (class "Default")
      (node (ref "D19") (pin "C") (pinfunction "C_C") (pintype "passive"))
      (node (ref "L2") (pin "2") (pinfunction "2_2") (pintype "passive"))
    )
    (net (code "46") (name "Net-(D21-PadC)") (class "Default")
      (node (ref "D21") (pin "C") (pinfunction "C_C") (pintype "passive"))
      (node (ref "D24") (pin "C") (pinfunction "C_C") (pintype "passive"))
    )
    (net (code "47") (name "Net-(D22-PadC)") (class "Default")
      (node (ref "D22") (pin "C") (pinfunction "C_C") (pintype "passive"))
      (node (ref "D23") (pin "C") (pinfunction "C_C") (pintype "passive"))
    )
    (net (code "48") (name "Net-(D37-PadC)") (class "Default")
      (node (ref "D37") (pin "C") (pinfunction "C_C") (pintype "passive"))
      (node (ref "D39") (pin "A") (pinfunction "A_A") (pintype "passive"))
    )
    (net (code "49") (name "Net-(D38-PadC)") (class "Default")
      (node (ref "D38") (pin "C") (pinfunction "C_C") (pintype "passive"))
      (node (ref "D40") (pin "A") (pinfunction "A_A") (pintype "passive"))
    )
    (net (code "50") (name "Net-(D39-PadC)") (class "Default")
      (node (ref "D39") (pin "C") (pinfunction "C_C") (pintype "passive"))
      (node (ref "D43") (pin "C") (pinfunction "C_C") (pintype "passive"))
    )
    (net (code "51") (name "Net-(D40-PadC)") (class "Default")
      (node (ref "D40") (pin "C") (pinfunction "C_C") (pintype "passive"))
      (node (ref "D44") (pin "C") (pinfunction "C_C") (pintype "passive"))
    )
    (net (code "52") (name "Net-(D41-PadC)") (class "Default")
      (node (ref "D41") (pin "C") (pinfunction "C_C") (pintype "passive"))
      (node (ref "D44") (pin "A") (pinfunction "A_A") (pintype "passive"))
    )
    (net (code "53") (name "Net-(D42-PadC)") (class "Default")
      (node (ref "D42") (pin "C") (pinfunction "C_C") (pintype "passive"))
      (node (ref "D43") (pin "A") (pinfunction "A_A") (pintype "passive"))
    )
    (net (code "54") (name "Net-(D50-C)") (class "Default")
      (node (ref "D50") (pin "2") (pinfunction "C_2") (pintype "passive"))
      (node (ref "J3") (pin "P3") (pinfunction "3_P3") (pintype "passive"))
      (node (ref "R22") (pin "1") (pinfunction "1_1") (pintype "passive"))
    )
    (net (code "55") (name "Net-(D51-C)") (class "Default")
      (node (ref "D51") (pin "2") (pinfunction "C_2") (pintype "passive"))
      (node (ref "J9") (pin "P3") (pinfunction "3_P3") (pintype "passive"))
      (node (ref "R19") (pin "1") (pinfunction "1_1") (pintype "passive"))
    )
    (net (code "56") (name "Net-(D52-C)") (class "Default")
      (node (ref "D52") (pin "2") (pinfunction "C_2") (pintype "passive"))
      (node (ref "J16") (pin "P3") (pinfunction "3_P3") (pintype "passive"))
      (node (ref "R34") (pin "1") (pinfunction "1_1") (pintype "passive"))
    )
    (net (code "57") (name "Net-(D55-C)") (class "Default")
      (node (ref "D55") (pin "2") (pinfunction "C_2") (pintype "passive"))
      (node (ref "J4") (pin "P3") (pinfunction "3_P3") (pintype "passive"))
      (node (ref "R183") (pin "1") (pinfunction "1_1") (pintype "passive"))
    )
    (net (code "58") (name "Net-(D56-C)") (class "Default")
      (node (ref "D56") (pin "2") (pinfunction "C_2") (pintype "passive"))
      (node (ref "J8") (pin "P3") (pinfunction "3_P3") (pintype "passive"))
      (node (ref "R189") (pin "1") (pinfunction "1_1") (pintype "passive"))
    )
    (net (code "59") (name "Net-(D57-C)") (class "Default")
      (node (ref "D57") (pin "2") (pinfunction "C_2") (pintype "passive"))
      (node (ref "J5") (pin "P3") (pinfunction "3_P3") (pintype "passive"))
      (node (ref "R185") (pin "1") (pinfunction "1_1") (pintype "passive"))
    )
    (net (code "60") (name "Net-(D58-C)") (class "Default")
      (node (ref "D58") (pin "2") (pinfunction "C_2") (pintype "passive"))
      (node (ref "J7") (pin "P3") (pinfunction "3_P3") (pintype "passive"))
      (node (ref "R187") (pin "1") (pinfunction "1_1") (pintype "passive"))
    )
    (net (code "61") (name "Net-(D59-C)") (class "Default")
      (node (ref "D59") (pin "2") (pinfunction "C_2") (pintype "passive"))
      (node (ref "J11") (pin "P3") (pinfunction "3_P3") (pintype "passive"))
      (node (ref "R161") (pin "1") (pinfunction "1_1") (pintype "passive"))
    )
    (net (code "62") (name "Net-(D60-C)") (class "Default")
      (node (ref "D60") (pin "2") (pinfunction "C_2") (pintype "passive"))
      (node (ref "J15") (pin "P3") (pinfunction "3_P3") (pintype "passive"))
      (node (ref "R162") (pin "1") (pinfunction "1_1") (pintype "passive"))
    )
    (net (code "63") (name "Net-(D61-C)") (class "Default")
      (node (ref "D61") (pin "2") (pinfunction "C_2") (pintype "passive"))
      (node (ref "J6") (pin "P3") (pinfunction "3_P3") (pintype "passive"))
      (node (ref "R186") (pin "1") (pinfunction "1_1") (pintype "passive"))
    )
    (net (code "64") (name "Net-(IC1A-+IN)") (class "Default")
      (node (ref "IC1") (pin "3") (pinfunction "+IN_3") (pintype "input"))
      (node (ref "R8") (pin "2") (pinfunction "2_2") (pintype "passive"))
    )
    (net (code "65") (name "Net-(IC1A--IN)") (class "Default")
      (node (ref "D2") (pin "A") (pinfunction "A_A") (pintype "passive"))
      (node (ref "IC1") (pin "2") (pinfunction "-IN_2") (pintype "input"))
      (node (ref "LED2") (pin "K") (pinfunction "C_K") (pintype "passive"))
      (node (ref "R2") (pin "1") (pinfunction "1_1") (pintype "passive"))
    )
    (net (code "66") (name "Net-(IC1A-OUT)") (class "Default")
      (node (ref "D2") (pin "C") (pinfunction "C_C") (pintype "passive"))
      (node (ref "IC1") (pin "1") (pinfunction "OUT_1") (pintype "output"))
      (node (ref "LED2") (pin "A") (pinfunction "A_A") (pintype "passive"))
    )
    (net (code "67") (name "Net-(IC1B--IN)") (class "Default")
      (node (ref "C13") (pin "1") (pinfunction "1_1") (pintype "passive"))
      (node (ref "D6") (pin "A") (pinfunction "A_A") (pintype "passive"))
      (node (ref "IC1") (pin "6") (pinfunction "-IN_6") (pintype "input"))
      (node (ref "IC5") (pin "4") (pinfunction "OUT_4") (pintype "output"))
      (node (ref "R25") (pin "1") (pinfunction "1_1") (pintype "passive"))
    )
    (net (code "68") (name "Net-(IC1B-OUT)") (class "Default")
      (node (ref "C13") (pin "2") (pinfunction "2_2") (pintype "passive"))
      (node (ref "D3") (pin "A") (pinfunction "A_A") (pintype "passive"))
      (node (ref "IC1") (pin "7") (pinfunction "OUT_7") (pintype "output"))
      (node (ref "R25") (pin "2") (pinfunction "2_2") (pintype "passive"))
      (node (ref "R55") (pin "1") (pinfunction "1_1") (pintype "passive"))
      (node (ref "R64") (pin "1") (pinfunction "1_1") (pintype "passive"))
      (node (ref "R91") (pin "1") (pinfunction "1_1") (pintype "passive"))
    )
    (net (code "69") (name "Net-(IC1C--IN)") (class "Default")
      (node (ref "C9") (pin "1") (pinfunction "1_1") (pintype "passive"))
      (node (ref "IC1") (pin "9") (pinfunction "-IN_9") (pintype "input"))
      (node (ref "IC5") (pin "13") (pinfunction "OUT_13") (pintype "output"))
      (node (ref "R13") (pin "2") (pinfunction "2_2") (pintype "passive"))
      (node (ref "R19") (pin "2") (pinfunction "2_2") (pintype "passive"))
      (node (ref "R20") (pin "2") (pinfunction "2_2") (pintype "passive"))
    )
    (net (code "70") (name "Net-(IC1C-OUT)") (class "Default")
      (node (ref "C9") (pin "2") (pinfunction "2_2") (pintype "passive"))
      (node (ref "IC1") (pin "8") (pinfunction "OUT_8") (pintype "output"))
      (node (ref "IC5") (pin "3") (pinfunction "CTRL_3") (pintype "input"))
      (node (ref "R26") (pin "2") (pinfunction "2_2") (pintype "passive"))
    )
    (net (code "71") (name "Net-(IC1D--IN)") (class "Default")
      (node (ref "C5") (pin "1") (pinfunction "1_1") (pintype "passive"))
      (node (ref "IC1") (pin "13") (pinfunction "-IN_13") (pintype "input"))
      (node (ref "R4") (pin "2") (pinfunction "2_2") (pintype "passive"))
      (node (ref "R6") (pin "1") (pinfunction "1_1") (pintype "passive"))
      (node (ref "R9") (pin "2") (pinfunction "2_2") (pintype "passive"))
    )
    (net (code "72") (name "Net-(IC2A--IN)") (class "Default")
      (node (ref "C6") (pin "1") (pinfunction "1_1") (pintype "passive"))
      (node (ref "IC2") (pin "2") (pinfunction "-IN_2") (pintype "input"))
      (node (ref "R10") (pin "2") (pinfunction "2_2") (pintype "passive"))
      (node (ref "R3") (pin "2") (pinfunction "2_2") (pintype "passive"))
      (node (ref "R5") (pin "1") (pinfunction "1_1") (pintype "passive"))
    )
    (net (code "73") (name "Net-(IC2B--IN)") (class "Default")
      (node (ref "C10") (pin "1") (pinfunction "1_1") (pintype "passive"))
      (node (ref "IC2") (pin "6") (pinfunction "-IN_6") (pintype "input"))
      (node (ref "IC4") (pin "4") (pinfunction "OUT_4") (pintype "output"))
      (node (ref "R11") (pin "2") (pinfunction "2_2") (pintype "passive"))
      (node (ref "R21") (pin "2") (pinfunction "2_2") (pintype "passive"))
      (node (ref "R22") (pin "2") (pinfunction "2_2") (pintype "passive"))
    )
    (net (code "74") (name "Net-(IC2B-OUT)") (class "Default")
      (node (ref "C10") (pin "2") (pinfunction "2_2") (pintype "passive"))
      (node (ref "IC2") (pin "7") (pinfunction "OUT_7") (pintype "output"))
      (node (ref "IC4") (pin "14") (pinfunction "CTRL_14") (pintype "input"))
      (node (ref "R27") (pin "2") (pinfunction "2_2") (pintype "passive"))
    )
    (net (code "75") (name "Net-(IC2C--IN)") (class "Default")
      (node (ref "C12") (pin "1") (pinfunction "1_1") (pintype "passive"))
      (node (ref "D5") (pin "A") (pinfunction "A_A") (pintype "passive"))
      (node (ref "IC2") (pin "9") (pinfunction "-IN_9") (pintype "input"))
      (node (ref "IC4") (pin "13") (pinfunction "OUT_13") (pintype "output"))
      (node (ref "R24") (pin "1") (pinfunction "1_1") (pintype "passive"))
    )
    (net (code "76") (name "Net-(IC2C-OUT)") (class "Default")
      (node (ref "C12") (pin "2") (pinfunction "2_2") (pintype "passive"))
      (node (ref "D4") (pin "A") (pinfunction "A_A") (pintype "passive"))
      (node (ref "IC2") (pin "8") (pinfunction "OUT_8") (pintype "output"))
      (node (ref "R24") (pin "2") (pinfunction "2_2") (pintype "passive"))
      (node (ref "R61") (pin "1") (pinfunction "1_1") (pintype "passive"))
      (node (ref "R66") (pin "1") (pinfunction "1_1") (pintype "passive"))
      (node (ref "R89") (pin "1") (pinfunction "1_1") (pintype "passive"))
    )
    (net (code "77") (name "Net-(IC2D-+IN)") (class "Default")
      (node (ref "IC2") (pin "12") (pinfunction "+IN_12") (pintype "input"))
      (node (ref "R7") (pin "2") (pinfunction "2_2") (pintype "passive"))
    )
    (net (code "78") (name "Net-(IC2D--IN)") (class "Default")
      (node (ref "D1") (pin "A") (pinfunction "A_A") (pintype "passive"))
      (node (ref "IC2") (pin "13") (pinfunction "-IN_13") (pintype "input"))
      (node (ref "LED1") (pin "K") (pinfunction "C_K") (pintype "passive"))
      (node (ref "R1") (pin "1") (pinfunction "1_1") (pintype "passive"))
    )
    (net (code "79") (name "Net-(IC2D-OUT)") (class "Default")
      (node (ref "D1") (pin "C") (pinfunction "C_C") (pintype "passive"))
      (node (ref "IC2") (pin "14") (pinfunction "OUT_14") (pintype "output"))
      (node (ref "LED1") (pin "A") (pinfunction "A_A") (pintype "passive"))
    )
    (net (code "80") (name "Net-(IC3A--IN)") (class "Default")
      (node (ref "C11") (pin "1") (pinfunction "1_1") (pintype "passive"))
      (node (ref "IC3") (pin "2") (pinfunction "-IN_2") (pintype "input"))
      (node (ref "R12") (pin "2") (pinfunction "2_2") (pintype "passive"))
      (node (ref "R16") (pin "1") (pinfunction "1_1") (pintype "passive"))
      (node (ref "R179") (pin "P$1") (pinfunction "E_P$1") (pintype "passive"))
      (node (ref "R28") (pin "2") (pinfunction "2_2") (pintype "passive"))
      (node (ref "R29") (pin "2") (pinfunction "2_2") (pintype "passive"))
    )
    (net (code "81") (name "Net-(IC3B--IN)") (class "Default")
      (node (ref "C24") (pin "1") (pinfunction "1_1") (pintype "passive"))
      (node (ref "D7") (pin "A") (pinfunction "A_A") (pintype "passive"))
      (node (ref "IC3") (pin "6") (pinfunction "-IN_6") (pintype "input"))
      (node (ref "IC4") (pin "12") (pinfunction "OUT_12") (pintype "output"))
      (node (ref "R42") (pin "2") (pinfunction "2_2") (pintype "passive"))
    )
    (net (code "82") (name "Net-(IC3B-OUT)") (class "Default")
      (node (ref "D7") (pin "C") (pinfunction "C_C") (pintype "passive"))
      (node (ref "D9") (pin "A") (pinfunction "A_A") (pintype "passive"))
      (node (ref "IC3") (pin "7") (pinfunction "OUT_7") (pintype "output"))
    )
    (net (code "83") (name "Net-(IC3C--IN)") (class "Default")
      (node (ref "C23") (pin "1") (pinfunction "1_1") (pintype "passive"))
      (node (ref "D8") (pin "A") (pinfunction "A_A") (pintype "passive"))
      (node (ref "IC3") (pin "9") (pinfunction "-IN_9") (pintype "input"))
      (node (ref "IC5") (pin "5") (pinfunction "OUT_5") (pintype "output"))
      (node (ref "R43") (pin "2") (pinfunction "2_2") (pintype "passive"))
    )
    (net (code "84") (name "Net-(IC3C-OUT)") (class "Default")
      (node (ref "D10") (pin "A") (pinfunction "A_A") (pintype "passive"))
      (node (ref "D8") (pin "C") (pinfunction "C_C") (pintype "passive"))
      (node (ref "IC3") (pin "8") (pinfunction "OUT_8") (pintype "output"))
    )
    (net (code "85") (name "Net-(IC3D--IN)") (class "Default")
      (node (ref "IC3") (pin "13") (pinfunction "-IN_13") (pintype "input"))
      (node (ref "R179") (pin "P$3") (pinfunction "A_P$3") (pintype "passive"))
      (node (ref "R23") (pin "1") (pinfunction "1_1") (pintype "passive"))
    )
    (net (code "86") (name "Net-(IC3D-OUT)") (class "Default")
      (node (ref "IC3") (pin "14") (pinfunction "OUT_14") (pintype "output"))
      (node (ref "R12") (pin "1") (pinfunction "1_1") (pintype "passive"))
      (node (ref "R23") (pin "2") (pinfunction "2_2") (pintype "passive"))
    )
    (net (code "87") (name "Net-(IC4A-CTRL)") (class "Default")
      (node (ref "IC4") (pin "3") (pinfunction "CTRL_3") (pintype "input"))
      (node (ref "R27") (pin "1") (pinfunction "1_1") (pintype "passive"))
      (node (ref "R41") (pin "2") (pinfunction "2_2") (pintype "passive"))
    )
    (net (code "88") (name "Net-(IC4A-IN)") (class "Default")
      (node (ref "IC4") (pin "2") (pinfunction "IN_2") (pintype "input"))
      (node (ref "R32") (pin "2") (pinfunction "2_2") (pintype "passive"))
      (node (ref "R40") (pin "2") (pinfunction "2_2") (pintype "passive"))
    )
    (net (code "89") (name "Net-(IC4B-CTRL)") (class "Default")
      (node (ref "C24") (pin "2") (pinfunction "2_2") (pintype "passive"))
      (node (ref "D9") (pin "C") (pinfunction "C_C") (pintype "passive"))
      (node (ref "IC4") (pin "11") (pinfunction "CTRL_11") (pintype "input"))
      (node (ref "IC4") (pin "6") (pinfunction "CTRL_6") (pintype "input"))
    )
    (net (code "90") (name "Net-(IC4B-IN)") (class "Default")
      (node (ref "IC4") (pin "7") (pinfunction "IN_7") (pintype "input"))
      (node (ref "R48") (pin "2") (pinfunction "2_2") (pintype "passive"))
      (node (ref "R57") (pin "2") (pinfunction "2_2") (pintype "passive"))
      (node (ref "R71") (pin "2") (pinfunction "2_2") (pintype "passive"))
    )
    (net (code "91") (name "Net-(IC4B-OUT)") (class "Default")
      (node (ref "C33") (pin "1") (pinfunction "1_1") (pintype "passive"))
      (node (ref "IC4") (pin "5") (pinfunction "OUT_5") (pintype "output"))
      (node (ref "IC8") (pin "2") (pinfunction "-IN_2") (pintype "input"))
      (node (ref "R68") (pin "1") (pinfunction "1_1") (pintype "passive"))
      (node (ref "R70") (pin "2") (pinfunction "2_2") (pintype "passive"))
    )
    (net (code "92") (name "Net-(IC4C-IN)") (class "Default")
      (node (ref "IC4") (pin "10") (pinfunction "IN_10") (pintype "input"))
      (node (ref "R49") (pin "2") (pinfunction "2_2") (pintype "passive"))
      (node (ref "R52") (pin "2") (pinfunction "2_2") (pintype "passive"))
    )
    (net (code "93") (name "Net-(IC4D-IN)") (class "Default")
      (node (ref "IC4") (pin "15") (pinfunction "IN_15") (pintype "input"))
      (node (ref "R33") (pin "2") (pinfunction "2_2") (pintype "passive"))
      (node (ref "R36") (pin "2") (pinfunction "2_2") (pintype "passive"))
    )
    (net (code "94") (name "Net-(IC4E-MODE)") (class "Default")
      (node (ref "IC4") (pin "1") (pinfunction "MODE_1") (pintype "input"))
      (node (ref "R30") (pin "1") (pinfunction "1_1") (pintype "passive"))
    )
    (net (code "95") (name "Net-(IC5A-IN)") (class "Default")
      (node (ref "IC5") (pin "2") (pinfunction "IN_2") (pintype "input"))
      (node (ref "R34") (pin "2") (pinfunction "2_2") (pintype "passive"))
      (node (ref "R37") (pin "2") (pinfunction "2_2") (pintype "passive"))
    )
    (net (code "96") (name "Net-(IC5B-CTRL)") (class "Default")
      (node (ref "C23") (pin "2") (pinfunction "2_2") (pintype "passive"))
      (node (ref "D10") (pin "C") (pinfunction "C_C") (pintype "passive"))
      (node (ref "IC5") (pin "11") (pinfunction "CTRL_11") (pintype "input"))
      (node (ref "IC5") (pin "6") (pinfunction "CTRL_6") (pintype "input"))
    )
    (net (code "97") (name "Net-(IC5B-IN)") (class "Default")
      (node (ref "IC5") (pin "7") (pinfunction "IN_7") (pintype "input"))
      (node (ref "R47") (pin "2") (pinfunction "2_2") (pintype "passive"))
      (node (ref "R53") (pin "2") (pinfunction "2_2") (pintype "passive"))
    )
    (net (code "98") (name "Net-(IC5C-IN)") (class "Default")
      (node (ref "IC5") (pin "10") (pinfunction "IN_10") (pintype "input"))
      (node (ref "R44") (pin "2") (pinfunction "2_2") (pintype "passive"))
      (node (ref "R45") (pin "2") (pinfunction "2_2") (pintype "passive"))
      (node (ref "R46") (pin "2") (pinfunction "2_2") (pintype "passive"))
    )
    (net (code "99") (name "Net-(IC5C-OUT)") (class "Default")
      (node (ref "C32") (pin "1") (pinfunction "1_1") (pintype "passive"))
      (node (ref "IC5") (pin "12") (pinfunction "OUT_12") (pintype "output"))
      (node (ref "IC8") (pin "13") (pinfunction "-IN_13") (pintype "input"))
      (node (ref "R69") (pin "1") (pinfunction "1_1") (pintype "passive"))
      (node (ref "R73") (pin "2") (pinfunction "2_2") (pintype "passive"))
    )
    (net (code "100") (name "Net-(IC5D-CTRL)") (class "Default")
      (node (ref "IC5") (pin "14") (pinfunction "CTRL_14") (pintype "input"))
      (node (ref "R26") (pin "1") (pinfunction "1_1") (pintype "passive"))
      (node (ref "R38") (pin "2") (pinfunction "2_2") (pintype "passive"))
    )
    (net (code "101") (name "Net-(IC5D-IN)") (class "Default")
      (node (ref "IC5") (pin "15") (pinfunction "IN_15") (pintype "input"))
      (node (ref "R35") (pin "2") (pinfunction "2_2") (pintype "passive"))
      (node (ref "R39") (pin "2") (pinfunction "2_2") (pintype "passive"))
    )
    (net (code "102") (name "Net-(IC5E-MODE)") (class "Default")
      (node (ref "IC5") (pin "1") (pinfunction "MODE_1") (pintype "input"))
      (node (ref "R31") (pin "1") (pinfunction "1_1") (pintype "passive"))
    )
    (net (code "103") (name "Net-(IC6A-+IN)") (class "Default")
      (node (ref "D11") (pin "A") (pinfunction "A_A") (pintype "passive"))
      (node (ref "D17") (pin "C") (pinfunction "C_C") (pintype "passive"))
      (node (ref "IC6") (pin "3") (pinfunction "+IN_3") (pintype "input"))
      (node (ref "R65") (pin "2") (pinfunction "2_2") (pintype "passive"))
    )
    (net (code "104") (name "Net-(IC6A--IN)") (class "Default")
      (node (ref "IC6") (pin "2") (pinfunction "-IN_2") (pintype "input"))
      (node (ref "R50") (pin "2") (pinfunction "2_2") (pintype "passive"))
      (node (ref "R51") (pin "1") (pinfunction "1_1") (pintype "passive"))
    )
    (net (code "105") (name "Net-(IC6A-OUT)") (class "Default")
      (node (ref "IC6") (pin "1") (pinfunction "OUT_1") (pintype "output"))
      (node (ref "R51") (pin "2") (pinfunction "2_2") (pintype "passive"))
      (node (ref "R88") (pin "1") (pinfunction "1_1") (pintype "passive"))
    )
    (net (code "106") (name "Net-(IC6B-+IN)") (class "Default")
      (node (ref "D14") (pin "A") (pinfunction "A_A") (pintype "passive"))
      (node (ref "D15") (pin "C") (pinfunction "C_C") (pintype "passive"))
      (node (ref "IC6") (pin "5") (pinfunction "+IN_5") (pintype "input"))
      (node (ref "R66") (pin "2") (pinfunction "2_2") (pintype "passive"))
    )
    (net (code "107") (name "Net-(IC6B--IN)") (class "Default")
      (node (ref "IC6") (pin "6") (pinfunction "-IN_6") (pintype "input"))
      (node (ref "R58") (pin "1") (pinfunction "1_1") (pintype "passive"))
      (node (ref "R61") (pin "2") (pinfunction "2_2") (pintype "passive"))
    )
    (net (code "108") (name "Net-(IC6B-OUT)") (class "Default")
      (node (ref "IC6") (pin "7") (pinfunction "OUT_7") (pintype "output"))
      (node (ref "R50") (pin "1") (pinfunction "1_1") (pintype "passive"))
      (node (ref "R58") (pin "2") (pinfunction "2_2") (pintype "passive"))
      (node (ref "R65") (pin "1") (pinfunction "1_1") (pintype "passive"))
    )
    (net (code "109") (name "Net-(IC7A-+IN)") (class "Default")
      (node (ref "D12") (pin "C") (pinfunction "C_C") (pintype "passive"))
      (node (ref "D16") (pin "A") (pinfunction "A_A") (pintype "passive"))
      (node (ref "IC7") (pin "3") (pinfunction "+IN_3") (pintype "input"))
      (node (ref "R64") (pin "2") (pinfunction "2_2") (pintype "passive"))
    )
    (net (code "110") (name "Net-(IC7A--IN)") (class "Default")
      (node (ref "IC7") (pin "2") (pinfunction "-IN_2") (pintype "input"))
      (node (ref "R55") (pin "2") (pinfunction "2_2") (pintype "passive"))
      (node (ref "R56") (pin "1") (pinfunction "1_1") (pintype "passive"))
    )
    (net (code "111") (name "Net-(IC7A-OUT)") (class "Default")
      (node (ref "IC7") (pin "1") (pinfunction "OUT_1") (pintype "output"))
      (node (ref "R56") (pin "2") (pinfunction "2_2") (pintype "passive"))
      (node (ref "R60") (pin "1") (pinfunction "1_1") (pintype "passive"))
      (node (ref "R67") (pin "1") (pinfunction "1_1") (pintype "passive"))
    )
    (net (code "112") (name "Net-(IC7B-+IN)") (class "Default")
      (node (ref "D13") (pin "C") (pinfunction "C_C") (pintype "passive"))
      (node (ref "D18") (pin "A") (pinfunction "A_A") (pintype "passive"))
      (node (ref "IC7") (pin "5") (pinfunction "+IN_5") (pintype "input"))
      (node (ref "R67") (pin "2") (pinfunction "2_2") (pintype "passive"))
    )
    (net (code "113") (name "Net-(IC7B--IN)") (class "Default")
      (node (ref "IC7") (pin "6") (pinfunction "-IN_6") (pintype "input"))
      (node (ref "R59") (pin "1") (pinfunction "1_1") (pintype "passive"))
      (node (ref "R60") (pin "2") (pinfunction "2_2") (pintype "passive"))
    )
    (net (code "114") (name "Net-(IC7B-OUT)") (class "Default")
      (node (ref "IC7") (pin "7") (pinfunction "OUT_7") (pintype "output"))
      (node (ref "R59") (pin "2") (pinfunction "2_2") (pintype "passive"))
      (node (ref "R90") (pin "1") (pinfunction "1_1") (pintype "passive"))
    )
    (net (code "115") (name "Net-(IC8A-OUT)") (class "Default")
      (node (ref "C33") (pin "2") (pinfunction "2_2") (pintype "passive"))
      (node (ref "IC8") (pin "1") (pinfunction "OUT_1") (pintype "output"))
      (node (ref "R194") (pin "1") (pinfunction "1_1") (pintype "passive"))
      (node (ref "R68") (pin "2") (pinfunction "2_2") (pintype "passive"))
    )
    (net (code "116") (name "Net-(IC8B--IN)") (class "Default")
      (node (ref "IC8") (pin "6") (pinfunction "-IN_6") (pintype "input"))
      (node (ref "R140") (pin "1") (pinfunction "1_1") (pintype "passive"))
      (node (ref "R77") (pin "2") (pinfunction "2_2") (pintype "passive"))
      (node (ref "R79") (pin "1") (pinfunction "1_1") (pintype "passive"))
    )
    (net (code "117") (name "Net-(IC8B-OUT)") (class "Default")
      (node (ref "IC8") (pin "7") (pinfunction "OUT_7") (pintype "output"))
      (node (ref "R140") (pin "2") (pinfunction "2_2") (pintype "passive"))
      (node (ref "R73") (pin "1") (pinfunction "1_1") (pintype "passive"))
      (node (ref "R79") (pin "2") (pinfunction "2_2") (pintype "passive"))
    )
    (net (code "118") (name "Net-(IC8C--IN)") (class "Default")
      (node (ref "IC8") (pin "8") (pinfunction "OUT_8") (pintype "output"))
      (node (ref "IC8") (pin "9") (pinfunction "-IN_9") (pintype "input"))
    )
    (net (code "119") (name "Net-(IC9A--IN)") (class "Default")
      (node (ref "IC9") (pin "2") (pinfunction "-IN_2") (pintype "input"))
      (node (ref "R197") (pin "1") (pinfunction "1_1") (pintype "passive"))
      (node (ref "R72") (pin "1") (pinfunction "1_1") (pintype "passive"))
      (node (ref "R76") (pin "2") (pinfunction "2_2") (pintype "passive"))
    )
    (net (code "120") (name "Net-(IC9B--IN)") (class "Default")
      (node (ref "IC9") (pin "6") (pinfunction "-IN_6") (pintype "input"))
      (node (ref "R74") (pin "1") (pinfunction "1_1") (pintype "passive"))
      (node (ref "R78") (pin "2") (pinfunction "2_2") (pintype "passive"))
    )
    (net (code "121") (name "Net-(IC9B-OUT)") (class "Default")
      (node (ref "IC9") (pin "7") (pinfunction "OUT_7") (pintype "output"))
      (node (ref "R57") (pin "1") (pinfunction "1_1") (pintype "passive"))
      (node (ref "R74") (pin "2") (pinfunction "2_2") (pintype "passive"))
    )
    (net (code "122") (name "Net-(IC12A-CTRL)") (class "Default")
      (node (ref "C82") (pin "2") (pinfunction "2_2") (pintype "passive"))
      (node (ref "D25") (pin "C") (pinfunction "C_C") (pintype "passive"))
      (node (ref "IC12") (pin "14") (pinfunction "CTRL_14") (pintype "input"))
      (node (ref "IC12") (pin "3") (pinfunction "CTRL_3") (pintype "input"))
    )
    (net (code "123") (name "Net-(IC12A-IN)") (class "Default")
      (node (ref "IC12") (pin "2") (pinfunction "IN_2") (pintype "input"))
      (node (ref "R102") (pin "2") (pinfunction "2_2") (pintype "passive"))
      (node (ref "R96") (pin "2") (pinfunction "2_2") (pintype "passive"))
      (node (ref "R98") (pin "2") (pinfunction "2_2") (pintype "passive"))
    )
    (net (code "124") (name "Net-(IC12A-OUT)") (class "Default")
      (node (ref "IC12") (pin "4") (pinfunction "OUT_4") (pintype "output"))
      (node (ref "IC12") (pin "7") (pinfunction "IN_7") (pintype "input"))
      (node (ref "R104") (pin "2") (pinfunction "2_2") (pintype "passive"))
      (node (ref "R105") (pin "2") (pinfunction "2_2") (pintype "passive"))
    )
    (net (code "125") (name "Net-(IC12B-CTRL)") (class "Default")
      (node (ref "C100") (pin "2") (pinfunction "2_2") (pintype "passive"))
      (node (ref "D48") (pin "C") (pinfunction "C_C") (pintype "passive"))
      (node (ref "IC12") (pin "11") (pinfunction "CTRL_11") (pintype "input"))
      (node (ref "IC12") (pin "6") (pinfunction "CTRL_6") (pintype "input"))
    )
    (net (code "126") (name "Net-(IC12B-OUT)") (class "Default")
      (node (ref "C86") (pin "1") (pinfunction "1_1") (pintype "passive"))
      (node (ref "D41") (pin "A") (pinfunction "A_A") (pintype "passive"))
      (node (ref "IC12") (pin "5") (pinfunction "OUT_5") (pintype "output"))
      (node (ref "IC18") (pin "2") (pinfunction "-IN_2") (pintype "input"))
      (node (ref "R153") (pin "1") (pinfunction "1_1") (pintype "passive"))
      (node (ref "R173") (pin "2") (pinfunction "2_2") (pintype "passive"))
    )
    (net (code "127") (name "Net-(IC12C-IN)") (class "Default")
      (node (ref "IC12") (pin "10") (pinfunction "IN_10") (pintype "input"))
      (node (ref "R100") (pin "2") (pinfunction "2_2") (pintype "passive"))
      (node (ref "R108") (pin "2") (pinfunction "2_2") (pintype "passive"))
    )
    (net (code "128") (name "Net-(IC12C-OUT)") (class "Default")
      (node (ref "C100") (pin "1") (pinfunction "1_1") (pintype "passive"))
      (node (ref "D45") (pin "A") (pinfunction "A_A") (pintype "passive"))
      (node (ref "IC12") (pin "12") (pinfunction "OUT_12") (pintype "output"))
      (node (ref "IC18") (pin "9") (pinfunction "-IN_9") (pintype "input"))
      (node (ref "R160") (pin "2") (pinfunction "2_2") (pintype "passive"))
      (node (ref "R170") (pin "2") (pinfunction "2_2") (pintype "passive"))
      (node (ref "R176") (pin "2") (pinfunction "2_2") (pintype "passive"))
    )
    (net (code "129") (name "Net-(IC12D-IN)") (class "Default")
      (node (ref "IC12") (pin "15") (pinfunction "IN_15") (pintype "input"))
      (node (ref "R92") (pin "2") (pinfunction "2_2") (pintype "passive"))
      (node (ref "R94") (pin "2") (pinfunction "2_2") (pintype "passive"))
    )
    (net (code "130") (name "Net-(IC12D-OUT)") (class "Default")
      (node (ref "C82") (pin "1") (pinfunction "1_1") (pintype "passive"))
      (node (ref "D27") (pin "A") (pinfunction "A_A") (pintype "passive"))
      (node (ref "IC12") (pin "13") (pinfunction "OUT_13") (pintype "output"))
      (node (ref "IC18") (pin "13") (pinfunction "-IN_13") (pintype "input"))
      (node (ref "R143") (pin "2") (pinfunction "2_2") (pintype "passive"))
      (node (ref "R146") (pin "2") (pinfunction "2_2") (pintype "passive"))
      (node (ref "R151") (pin "2") (pinfunction "2_2") (pintype "passive"))
    )
    (net (code "131") (name "Net-(IC12E-MODE)") (class "Default")
      (node (ref "IC12") (pin "1") (pinfunction "MODE_1") (pintype "input"))
      (node (ref "R84") (pin "1") (pinfunction "1_1") (pintype "passive"))
    )
    (net (code "132") (name "Net-(IC13A-CTRL)") (class "Default")
      (node (ref "C83") (pin "2") (pinfunction "2_2") (pintype "passive"))
      (node (ref "D26") (pin "C") (pinfunction "C_C") (pintype "passive"))
      (node (ref "IC13") (pin "14") (pinfunction "CTRL_14") (pintype "input"))
      (node (ref "IC13") (pin "3") (pinfunction "CTRL_3") (pintype "input"))
    )
    (net (code "133") (name "Net-(IC13A-IN)") (class "Default")
      (node (ref "IC13") (pin "2") (pinfunction "IN_2") (pintype "input"))
      (node (ref "R93") (pin "2") (pinfunction "2_2") (pintype "passive"))
      (node (ref "R95") (pin "2") (pinfunction "2_2") (pintype "passive"))
    )
    (net (code "134") (name "Net-(IC13A-OUT)") (class "Default")
      (node (ref "C83") (pin "1") (pinfunction "1_1") (pintype "passive"))
      (node (ref "D28") (pin "A") (pinfunction "A_A") (pintype "passive"))
      (node (ref "IC13") (pin "4") (pinfunction "OUT_4") (pintype "output"))
      (node (ref "IC21") (pin "2") (pinfunction "-IN_2") (pintype "input"))
      (node (ref "R144") (pin "2") (pinfunction "2_2") (pintype "passive"))
      (node (ref "R145") (pin "2") (pinfunction "2_2") (pintype "passive"))
      (node (ref "R152") (pin "2") (pinfunction "2_2") (pintype "passive"))
    )
    (net (code "135") (name "Net-(IC13B-CTRL)") (class "Default")
      (node (ref "C101") (pin "2") (pinfunction "2_2") (pintype "passive"))
      (node (ref "D47") (pin "C") (pinfunction "C_C") (pintype "passive"))
      (node (ref "IC13") (pin "11") (pinfunction "CTRL_11") (pintype "input"))
      (node (ref "IC13") (pin "6") (pinfunction "CTRL_6") (pintype "input"))
    )
    (net (code "136") (name "Net-(IC13B-IN)") (class "Default")
      (node (ref "IC13") (pin "7") (pinfunction "IN_7") (pintype "input"))
      (node (ref "R101") (pin "2") (pinfunction "2_2") (pintype "passive"))
      (node (ref "R109") (pin "2") (pinfunction "2_2") (pintype "passive"))
    )
    (net (code "137") (name "Net-(IC13B-OUT)") (class "Default")
      (node (ref "C101") (pin "1") (pinfunction "1_1") (pintype "passive"))
      (node (ref "D46") (pin "A") (pinfunction "A_A") (pintype "passive"))
      (node (ref "IC13") (pin "5") (pinfunction "OUT_5") (pintype "output"))
      (node (ref "IC21") (pin "6") (pinfunction "-IN_6") (pintype "input"))
      (node (ref "R159") (pin "2") (pinfunction "2_2") (pintype "passive"))
      (node (ref "R169") (pin "2") (pinfunction "2_2") (pintype "passive"))
      (node (ref "R175") (pin "2") (pinfunction "2_2") (pintype "passive"))
    )
    (net (code "138") (name "Net-(IC13C-IN)") (class "Default")
      (node (ref "IC13") (pin "10") (pinfunction "IN_10") (pintype "input"))
      (node (ref "IC13") (pin "13") (pinfunction "OUT_13") (pintype "output"))
      (node (ref "R106") (pin "2") (pinfunction "2_2") (pintype "passive"))
      (node (ref "R107") (pin "2") (pinfunction "2_2") (pintype "passive"))
    )
    (net (code "139") (name "Net-(IC13C-OUT)") (class "Default")
      (node (ref "C87") (pin "1") (pinfunction "1_1") (pintype "passive"))
      (node (ref "D42") (pin "A") (pinfunction "A_A") (pintype "passive"))
      (node (ref "IC13") (pin "12") (pinfunction "OUT_12") (pintype "output"))
      (node (ref "IC21") (pin "13") (pinfunction "-IN_13") (pintype "input"))
      (node (ref "R154") (pin "1") (pinfunction "1_1") (pintype "passive"))
      (node (ref "R174") (pin "2") (pinfunction "2_2") (pintype "passive"))
    )
    (net (code "140") (name "Net-(IC13D-IN)") (class "Default")
      (node (ref "IC13") (pin "15") (pinfunction "IN_15") (pintype "input"))
      (node (ref "R103") (pin "2") (pinfunction "2_2") (pintype "passive"))
      (node (ref "R97") (pin "2") (pinfunction "2_2") (pintype "passive"))
      (node (ref "R99") (pin "2") (pinfunction "2_2") (pintype "passive"))
    )
    (net (code "141") (name "Net-(IC13E-MODE)") (class "Default")
      (node (ref "IC13") (pin "1") (pinfunction "MODE_1") (pintype "input"))
      (node (ref "R85") (pin "1") (pinfunction "1_1") (pintype "passive"))
    )
    (net (code "142") (name "Net-(IC14A--IN)") (class "Default")
      (node (ref "C62") (pin "1") (pinfunction "1_1") (pintype "passive"))
      (node (ref "IC14") (pin "2") (pinfunction "-IN_2") (pintype "input"))
      (node (ref "IC16") (pin "4") (pinfunction "OUT_4") (pintype "output"))
    )
    (net (code "143") (name "Net-(IC14B--IN)") (class "Default")
      (node (ref "IC14") (pin "6") (pinfunction "-IN_6") (pintype "input"))
      (node (ref "R110") (pin "1") (pinfunction "1_1") (pintype "passive"))
      (node (ref "R114") (pin "2") (pinfunction "2_2") (pintype "passive"))
      (node (ref "R115") (pin "1") (pinfunction "1_1") (pintype "passive"))
      (node (ref "R122") (pin "1") (pinfunction "1_1") (pintype "passive"))
    )
    (net (code "144") (name "Net-(IC14C--IN)") (class "Default")
      (node (ref "IC14") (pin "9") (pinfunction "-IN_9") (pintype "input"))
      (node (ref "R111") (pin "2") (pinfunction "2_2") (pintype "passive"))
      (node (ref "R116") (pin "1") (pinfunction "1_1") (pintype "passive"))
      (node (ref "R118") (pin "2") (pinfunction "2_2") (pintype "passive"))
    )
    (net (code "145") (name "Net-(IC14C-OUT)") (class "Default")
      (node (ref "IC14") (pin "8") (pinfunction "OUT_8") (pintype "output"))
      (node (ref "R104") (pin "1") (pinfunction "1_1") (pintype "passive"))
      (node (ref "R116") (pin "2") (pinfunction "2_2") (pintype "passive"))
    )
    (net (code "146") (name "Net-(IC14D--IN)") (class "Default")
      (node (ref "C63") (pin "1") (pinfunction "1_1") (pintype "passive"))
      (node (ref "IC14") (pin "13") (pinfunction "-IN_13") (pintype "input"))
      (node (ref "IC16") (pin "13") (pinfunction "OUT_13") (pintype "output"))
    )
    (net (code "147") (name "Net-(IC15A--IN)") (class "Default")
      (node (ref "C64") (pin "1") (pinfunction "1_1") (pintype "passive"))
      (node (ref "IC15") (pin "2") (pinfunction "-IN_2") (pintype "input"))
      (node (ref "IC17") (pin "4") (pinfunction "OUT_4") (pintype "output"))
    )
    (net (code "148") (name "Net-(IC15B--IN)") (class "Default")
      (node (ref "IC15") (pin "6") (pinfunction "-IN_6") (pintype "input"))
      (node (ref "R112") (pin "2") (pinfunction "2_2") (pintype "passive"))
      (node (ref "R119") (pin "2") (pinfunction "2_2") (pintype "passive"))
      (node (ref "R120") (pin "1") (pinfunction "1_1") (pintype "passive"))
    )
    (net (code "149") (name "Net-(IC15B-OUT)") (class "Default")
      (node (ref "IC15") (pin "7") (pinfunction "OUT_7") (pintype "output"))
      (node (ref "R106") (pin "1") (pinfunction "1_1") (pintype "passive"))
      (node (ref "R120") (pin "2") (pinfunction "2_2") (pintype "passive"))
    )
    (net (code "150") (name "Net-(IC15C--IN)") (class "Default")
      (node (ref "IC15") (pin "9") (pinfunction "-IN_9") (pintype "input"))
      (node (ref "R113") (pin "1") (pinfunction "1_1") (pintype "passive"))
      (node (ref "R117") (pin "1") (pinfunction "1_1") (pintype "passive"))
      (node (ref "R121") (pin "2") (pinfunction "2_2") (pintype "passive"))
      (node (ref "R123") (pin "1") (pinfunction "1_1") (pintype "passive"))
    )
    (net (code "151") (name "Net-(IC15D--IN)") (class "Default")
      (node (ref "C65") (pin "1") (pinfunction "1_1") (pintype "passive"))
      (node (ref "IC15") (pin "13") (pinfunction "-IN_13") (pintype "input"))
      (node (ref "IC17") (pin "13") (pinfunction "OUT_13") (pintype "output"))
    )
    (net (code "152") (name "Net-(IC16A-CTRL)") (class "Default")
      (node (ref "IC16") (pin "14") (pinfunction "CTRL_14") (pintype "input"))
      (node (ref "IC16") (pin "3") (pinfunction "CTRL_3") (pintype "input"))
      (node (ref "R196") (pin "1") (pinfunction "E_1") (pintype "passive"))
      (node (ref "R196") (pin "2") (pinfunction "S_2") (pintype "passive"))
    )
    (net (code "153") (name "Net-(IC16A-IN)") (class "Default")
      (node (ref "D24") (pin "A") (pinfunction "A_A") (pintype "passive"))
      (node (ref "IC16") (pin "2") (pinfunction "IN_2") (pintype "input"))
      (node (ref "IC16") (pin "5") (pinfunction "OUT_5") (pintype "output"))
      (node (ref "R132") (pin "2") (pinfunction "2_2") (pintype "passive"))
      (node (ref "R136") (pin "2") (pinfunction "2_2") (pintype "passive"))
    )
    (net (code "154") (name "Net-(IC16B-CTRL)") (class "Default")
      (node (ref "C91") (pin "2") (pinfunction "2_2") (pintype "passive"))
      (node (ref "D29") (pin "C") (pinfunction "C_C") (pintype "passive"))
      (node (ref "IC16") (pin "6") (pinfunction "CTRL_6") (pintype "input"))
      (node (ref "R148") (pin "2") (pinfunction "2_2") (pintype "passive"))
    )
    (net (code "155") (name "Net-(IC16B-IN)") (class "Default")
      (node (ref "IC16") (pin "7") (pinfunction "IN_7") (pintype "input"))
      (node (ref "R138") (pin "2") (pinfunction "2_2") (pintype "passive"))
      (node (ref "R142") (pin "2") (pinfunction "2_2") (pintype "passive"))
    )
    (net (code "156") (name "Net-(IC16D-IN)") (class "Default")
      (node (ref "C72") (pin "1") (pinfunction "1_1") (pintype "passive"))
      (node (ref "IC16") (pin "15") (pinfunction "IN_15") (pintype "input"))
      (node (ref "R131") (pin "2") (pinfunction "2_2") (pintype "passive"))
      (node (ref "R134") (pin "2") (pinfunction "2_2") (pintype "passive"))
    )
    (net (code "157") (name "Net-(IC16E-MODE)") (class "Default")
      (node (ref "IC16") (pin "1") (pinfunction "MODE_1") (pintype "input"))
      (node (ref "R125") (pin "1") (pinfunction "1_1") (pintype "passive"))
    )
    (net (code "158") (name "Net-(IC17A-CTRL)") (class "Default")
      (node (ref "IC17") (pin "14") (pinfunction "CTRL_14") (pintype "input"))
      (node (ref "IC17") (pin "3") (pinfunction "CTRL_3") (pintype "input"))
      (node (ref "R195") (pin "1") (pinfunction "E_1") (pintype "passive"))
      (node (ref "R195") (pin "2") (pinfunction "S_2") (pintype "passive"))
    )
    (net (code "159") (name "Net-(IC17A-IN)") (class "Default")
      (node (ref "C73") (pin "1") (pinfunction "1_1") (pintype "passive"))
      (node (ref "IC17") (pin "2") (pinfunction "IN_2") (pintype "input"))
      (node (ref "R129") (pin "2") (pinfunction "2_2") (pintype "passive"))
      (node (ref "R135") (pin "2") (pinfunction "2_2") (pintype "passive"))
    )
    (net (code "160") (name "Net-(IC17C-CTRL)") (class "Default")
      (node (ref "C88") (pin "2") (pinfunction "2_2") (pintype "passive"))
      (node (ref "D30") (pin "C") (pinfunction "C_C") (pintype "passive"))
      (node (ref "IC17") (pin "11") (pinfunction "CTRL_11") (pintype "input"))
      (node (ref "R150") (pin "2") (pinfunction "2_2") (pintype "passive"))
    )
    (net (code "161") (name "Net-(IC17C-IN)") (class "Default")
      (node (ref "IC17") (pin "10") (pinfunction "IN_10") (pintype "input"))
      (node (ref "R137") (pin "2") (pinfunction "2_2") (pintype "passive"))
      (node (ref "R141") (pin "2") (pinfunction "2_2") (pintype "passive"))
    )
    (net (code "162") (name "Net-(IC17C-OUT)") (class "Default")
      (node (ref "D23") (pin "A") (pinfunction "A_A") (pintype "passive"))
      (node (ref "IC17") (pin "12") (pinfunction "OUT_12") (pintype "output"))
      (node (ref "IC17") (pin "15") (pinfunction "IN_15") (pintype "input"))
      (node (ref "R126") (pin "2") (pinfunction "2_2") (pintype "passive"))
      (node (ref "R133") (pin "2") (pinfunction "2_2") (pintype "passive"))
    )
    (net (code "163") (name "Net-(IC17E-MODE)") (class "Default")
      (node (ref "IC17") (pin "1") (pinfunction "MODE_1") (pintype "input"))
      (node (ref "R124") (pin "1") (pinfunction "1_1") (pintype "passive"))
    )
    (net (code "164") (name "Net-(IC18B--IN)") (class "Default")
      (node (ref "IC18") (pin "6") (pinfunction "-IN_6") (pintype "input"))
      (node (ref "IC18") (pin "7") (pinfunction "OUT_7") (pintype "output"))
    )
    (net (code "165") (name "Net-(IC18C-OUT)") (class "Default")
      (node (ref "D45") (pin "C") (pinfunction "C_C") (pintype "passive"))
      (node (ref "D48") (pin "A") (pinfunction "A_A") (pintype "passive"))
      (node (ref "IC18") (pin "8") (pinfunction "OUT_8") (pintype "output"))
    )
    (net (code "166") (name "Net-(IC18D-OUT)") (class "Default")
      (node (ref "D25") (pin "A") (pinfunction "A_A") (pintype "passive"))
      (node (ref "D27") (pin "C") (pinfunction "C_C") (pintype "passive"))
      (node (ref "IC18") (pin "14") (pinfunction "OUT_14") (pintype "output"))
    )
    (net (code "167") (name "Net-(IC19A--IN)") (class "Default")
      (node (ref "C90") (pin "1") (pinfunction "1_1") (pintype "passive"))
      (node (ref "D34") (pin "A") (pinfunction "A_A") (pintype "passive"))
      (node (ref "IC19") (pin "2") (pinfunction "-IN_2") (pintype "input"))
      (node (ref "R147") (pin "1") (pinfunction "1_1") (pintype "passive"))
      (node (ref "R156") (pin "2") (pinfunction "2_2") (pintype "passive"))
      (node (ref "R161") (pin "2") (pinfunction "2_2") (pintype "passive"))
      (node (ref "R165") (pin "2") (pinfunction "2_2") (pintype "passive"))
      (node (ref "R177") (pin "P$1") (pinfunction "E_P$1") (pintype "passive"))
    )
    (net (code "168") (name "Net-(IC19A-OUT)") (class "Default")
      (node (ref "D32") (pin "A") (pinfunction "A_A") (pintype "passive"))
      (node (ref "D34") (pin "C") (pinfunction "C_C") (pintype "passive"))
      (node (ref "IC19") (pin "1") (pinfunction "OUT_1") (pintype "output"))
    )
    (net (code "169") (name "Net-(IC19B--IN)") (class "Default")
      (node (ref "IC19") (pin "6") (pinfunction "-IN_6") (pintype "input"))
      (node (ref "R166") (pin "1") (pinfunction "1_1") (pintype "passive"))
      (node (ref "R177") (pin "P$3") (pinfunction "A_P$3") (pintype "passive"))
    )
    (net (code "170") (name "Net-(IC19B-OUT)") (class "Default")
      (node (ref "IC19") (pin "7") (pinfunction "OUT_7") (pintype "output"))
      (node (ref "R165") (pin "1") (pinfunction "1_1") (pintype "passive"))
      (node (ref "R166") (pin "2") (pinfunction "2_2") (pintype "passive"))
    )
    (net (code "171") (name "Net-(IC19C--IN)") (class "Default")
      (node (ref "IC19") (pin "9") (pinfunction "-IN_9") (pintype "input"))
      (node (ref "R167") (pin "1") (pinfunction "1_1") (pintype "passive"))
      (node (ref "R178") (pin "P$1") (pinfunction "E_P$1") (pintype "passive"))
    )
    (net (code "172") (name "Net-(IC19C-OUT)") (class "Default")
      (node (ref "IC19") (pin "8") (pinfunction "OUT_8") (pintype "output"))
      (node (ref "R164") (pin "1") (pinfunction "1_1") (pintype "passive"))
      (node (ref "R167") (pin "2") (pinfunction "2_2") (pintype "passive"))
    )
    (net (code "173") (name "Net-(IC19D--IN)") (class "Default")
      (node (ref "C91") (pin "1") (pinfunction "1_1") (pintype "passive"))
      (node (ref "D35") (pin "A") (pinfunction "A_A") (pintype "passive"))
      (node (ref "IC19") (pin "13") (pinfunction "-IN_13") (pintype "input"))
      (node (ref "R148") (pin "1") (pinfunction "1_1") (pintype "passive"))
      (node (ref "R155") (pin "2") (pinfunction "2_2") (pintype "passive"))
      (node (ref "R164") (pin "2") (pinfunction "2_2") (pintype "passive"))
      (node (ref "R178") (pin "P$3") (pinfunction "A_P$3") (pintype "passive"))
    )
    (net (code "174") (name "Net-(IC19D-OUT)") (class "Default")
      (node (ref "D29") (pin "A") (pinfunction "A_A") (pintype "passive"))
      (node (ref "D35") (pin "C") (pinfunction "C_C") (pintype "passive"))
      (node (ref "IC19") (pin "14") (pinfunction "OUT_14") (pintype "output"))
    )
    (net (code "175") (name "Net-(IC20A--IN)") (class "Default")
      (node (ref "C88") (pin "1") (pinfunction "1_1") (pintype "passive"))
      (node (ref "D33") (pin "A") (pinfunction "A_A") (pintype "passive"))
      (node (ref "IC20") (pin "2") (pinfunction "-IN_2") (pintype "input"))
      (node (ref "R150") (pin "1") (pinfunction "1_1") (pintype "passive"))
      (node (ref "R157") (pin "2") (pinfunction "2_2") (pintype "passive"))
      (node (ref "R168") (pin "2") (pinfunction "2_2") (pintype "passive"))
      (node (ref "R180") (pin "P$3") (pinfunction "A_P$3") (pintype "passive"))
    )
    (net (code "176") (name "Net-(IC20A-OUT)") (class "Default")
      (node (ref "D30") (pin "A") (pinfunction "A_A") (pintype "passive"))
      (node (ref "D33") (pin "C") (pinfunction "C_C") (pintype "passive"))
      (node (ref "IC20") (pin "1") (pinfunction "OUT_1") (pintype "output"))
    )
    (net (code "177") (name "Net-(IC20B--IN)") (class "Default")
      (node (ref "IC20") (pin "6") (pinfunction "-IN_6") (pintype "input"))
      (node (ref "R171") (pin "1") (pinfunction "1_1") (pintype "passive"))
      (node (ref "R180") (pin "P$1") (pinfunction "E_P$1") (pintype "passive"))
    )
    (net (code "178") (name "Net-(IC20B-OUT)") (class "Default")
      (node (ref "IC20") (pin "7") (pinfunction "OUT_7") (pintype "output"))
      (node (ref "R168") (pin "1") (pinfunction "1_1") (pintype "passive"))
      (node (ref "R171") (pin "2") (pinfunction "2_2") (pintype "passive"))
    )
    (net (code "179") (name "Net-(IC20C--IN)") (class "Default")
      (node (ref "IC20") (pin "9") (pinfunction "-IN_9") (pintype "input"))
      (node (ref "R163") (pin "1") (pinfunction "1_1") (pintype "passive"))
      (node (ref "R181") (pin "P$3") (pinfunction "A_P$3") (pintype "passive"))
      (node (ref "SW1") (pin "P2") (pinfunction "A2_P2") (pintype "passive"))
    )
    (net (code "180") (name "Net-(IC20C-OUT)") (class "Default")
      (node (ref "IC20") (pin "8") (pinfunction "OUT_8") (pintype "output"))
      (node (ref "R163") (pin "2") (pinfunction "2_2") (pintype "passive"))
      (node (ref "R172") (pin "1") (pinfunction "1_1") (pintype "passive"))
    )
    (net (code "181") (name "Net-(IC20D--IN)") (class "Default")
      (node (ref "C89") (pin "1") (pinfunction "1_1") (pintype "passive"))
      (node (ref "D36") (pin "A") (pinfunction "A_A") (pintype "passive"))
      (node (ref "IC20") (pin "13") (pinfunction "-IN_13") (pintype "input"))
      (node (ref "R149") (pin "1") (pinfunction "1_1") (pintype "passive"))
      (node (ref "R158") (pin "2") (pinfunction "2_2") (pintype "passive"))
      (node (ref "R162") (pin "2") (pinfunction "2_2") (pintype "passive"))
      (node (ref "R172") (pin "2") (pinfunction "2_2") (pintype "passive"))
      (node (ref "R181") (pin "P$1") (pinfunction "E_P$1") (pintype "passive"))
    )
    (net (code "182") (name "Net-(IC20D-OUT)") (class "Default")
      (node (ref "D31") (pin "A") (pinfunction "A_A") (pintype "passive"))
      (node (ref "D36") (pin "C") (pinfunction "C_C") (pintype "passive"))
      (node (ref "IC20") (pin "14") (pinfunction "OUT_14") (pintype "output"))
    )
    (net (code "183") (name "Net-(IC21A-OUT)") (class "Default")
      (node (ref "D26") (pin "A") (pinfunction "A_A") (pintype "passive"))
      (node (ref "D28") (pin "C") (pinfunction "C_C") (pintype "passive"))
      (node (ref "IC21") (pin "1") (pinfunction "OUT_1") (pintype "output"))
    )
    (net (code "184") (name "Net-(IC21B-OUT)") (class "Default")
      (node (ref "D46") (pin "C") (pinfunction "C_C") (pintype "passive"))
      (node (ref "D47") (pin "A") (pinfunction "A_A") (pintype "passive"))
      (node (ref "IC21") (pin "7") (pinfunction "OUT_7") (pintype "output"))
    )
    (net (code "185") (name "Net-(IC21C--IN)") (class "Default")
      (node (ref "IC21") (pin "8") (pinfunction "OUT_8") (pintype "output"))
      (node (ref "IC21") (pin "9") (pinfunction "-IN_9") (pintype "input"))
    )
    (net (code "186") (name "Net-(J3-2)") (class "Default")
      (node (ref "J3") (pin "P2") (pinfunction "2_P2") (pintype "passive"))
      (node (ref "R182") (pin "1") (pinfunction "1_1") (pintype "passive"))
    )
    (net (code "187") (name "Net-(J4-2)") (class "Default")
      (node (ref "J4") (pin "P2") (pinfunction "2_P2") (pintype "passive"))
      (node (ref "R184") (pin "2") (pinfunction "2_2") (pintype "passive"))
    )
    (net (code "188") (name "Net-(J8-2)") (class "Default")
      (node (ref "J8") (pin "P2") (pinfunction "2_P2") (pintype "passive"))
      (node (ref "R188") (pin "2") (pinfunction "2_2") (pintype "passive"))
    )
    (net (code "189") (name "Net-(J9-2)") (class "Default")
      (node (ref "J9") (pin "P2") (pinfunction "2_P2") (pintype "passive"))
      (node (ref "R190") (pin "1") (pinfunction "1_1") (pintype "passive"))
    )
    (net (code "190") (name "Net-(J12-3)") (class "Default")
      (node (ref "J12") (pin "P3") (pinfunction "3_P3") (pintype "passive"))
      (node (ref "R191") (pin "2") (pinfunction "2_2") (pintype "passive"))
    )
    (net (code "191") (name "Net-(J13-3)") (class "Default")
      (node (ref "J13") (pin "P3") (pinfunction "3_P3") (pintype "passive"))
      (node (ref "R192") (pin "2") (pinfunction "2_2") (pintype "passive"))
    )
    (net (code "192") (name "Net-(J14-3)") (class "Default")
      (node (ref "J14") (pin "P3") (pinfunction "3_P3") (pintype "passive"))
      (node (ref "R193") (pin "2") (pinfunction "2_2") (pintype "passive"))
    )
    (net (code "193") (name "Net-(JP1-Pad1)") (class "Default")
      (node (ref "JP1") (pin "1") (pinfunction "1_1") (pintype "passive"))
      (node (ref "JP1") (pin "2") (pinfunction "2_2") (pintype "passive"))
      (node (ref "P1") (pin "2") (pinfunction "2_2") (pintype "bidirectional"))
    )
    (net (code "194") (name "Net-(L1-Pad2)") (class "Default")
      (node (ref "L1") (pin "2") (pinfunction "2_2") (pintype "passive"))
      (node (ref "P1") (pin "1") (pinfunction "1_1") (pintype "bidirectional"))
    )
    (net (code "195") (name "Net-(R14-S)") (class "Default")
      (node (ref "R14") (pin "P$2") (pinfunction "S_P$2") (pintype "passive"))
      (node (ref "R155") (pin "1") (pinfunction "1_1") (pintype "passive"))
    )
    (net (code "196") (name "Net-(R15-S)") (class "Default")
      (node (ref "R15") (pin "P$2") (pinfunction "S_P$2") (pintype "passive"))
      (node (ref "R157") (pin "1") (pinfunction "1_1") (pintype "passive"))
    )
    (net (code "197") (name "Net-(R17-S)") (class "Default")
      (node (ref "R11") (pin "1") (pinfunction "1_1") (pintype "passive"))
      (node (ref "R17") (pin "P$2") (pinfunction "S_P$2") (pintype "passive"))
    )
    (net (code "198") (name "Net-(R18-S)") (class "Default")
      (node (ref "R13") (pin "1") (pinfunction "1_1") (pintype "passive"))
      (node (ref "R18") (pin "P$2") (pinfunction "S_P$2") (pintype "passive"))
    )
    (net (code "199") (name "Net-(R75-Pad2)") (class "Default")
      (node (ref "R75") (pin "2") (pinfunction "2_2") (pintype "passive"))
      (node (ref "SW1") (pin "L1") (pinfunction "L1_L1") (pintype "passive"))
    )
    (net (code "200") (name "Net-(R80-A)") (class "Default")
      (node (ref "R3") (pin "1") (pinfunction "1_1") (pintype "passive"))
      (node (ref "R80") (pin "P$3") (pinfunction "A_P$3") (pintype "passive"))
      (node (ref "R88") (pin "2") (pinfunction "2_2") (pintype "passive"))
    )
    (net (code "201") (name "Net-(R80-E)") (class "Default")
      (node (ref "R10") (pin "1") (pinfunction "1_1") (pintype "passive"))
      (node (ref "R80") (pin "P$1") (pinfunction "E_P$1") (pintype "passive"))
      (node (ref "R89") (pin "2") (pinfunction "2_2") (pintype "passive"))
    )
    (net (code "202") (name "Net-(R81-A)") (class "Default")
      (node (ref "R81") (pin "P$3") (pinfunction "A_P$3") (pintype "passive"))
      (node (ref "R9") (pin "1") (pinfunction "1_1") (pintype "passive"))
      (node (ref "R90") (pin "2") (pinfunction "2_2") (pintype "passive"))
    )
    (net (code "203") (name "Net-(R81-E)") (class "Default")
      (node (ref "R4") (pin "1") (pinfunction "1_1") (pintype "passive"))
      (node (ref "R81") (pin "P$1") (pinfunction "E_P$1") (pintype "passive"))
      (node (ref "R91") (pin "2") (pinfunction "2_2") (pintype "passive"))
    )
    (net (code "204") (name "Net-(R86-S)") (class "Default")
      (node (ref "R156") (pin "1") (pinfunction "1_1") (pintype "passive"))
      (node (ref "R86") (pin "P$2") (pinfunction "S_P$2") (pintype "passive"))
    )
    (net (code "205") (name "Net-(R87-S)") (class "Default")
      (node (ref "R158") (pin "1") (pinfunction "1_1") (pintype "passive"))
      (node (ref "R87") (pin "P$2") (pinfunction "S_P$2") (pintype "passive"))
    )
    (net (code "206") (name "Net-(R128-S)") (class "Default")
      (node (ref "R128") (pin "P$2") (pinfunction "S_P$2") (pintype "passive"))
      (node (ref "R29") (pin "1") (pinfunction "1_1") (pintype "passive"))
    )
    (net (code "207") (name "Net-(R139-E)") (class "Default")
      (node (ref "R139") (pin "1") (pinfunction "E_1") (pintype "passive"))
      (node (ref "R139") (pin "2") (pinfunction "S_2") (pintype "passive"))
      (node (ref "R77") (pin "1") (pinfunction "1_1") (pintype "passive"))
    )
    (net (code "208") (name "Net-(R177-S)") (class "Default")
      (node (ref "R177") (pin "P$2") (pinfunction "S_P$2") (pintype "passive"))
      (node (ref "R183") (pin "2") (pinfunction "2_2") (pintype "passive"))
    )
    (net (code "209") (name "Net-(R178-S)") (class "Default")
      (node (ref "R178") (pin "P$2") (pinfunction "S_P$2") (pintype "passive"))
      (node (ref "R185") (pin "2") (pinfunction "2_2") (pintype "passive"))
    )
    (net (code "210") (name "Net-(R179-S)") (class "Default")
      (node (ref "R179") (pin "P$2") (pinfunction "S_P$2") (pintype "passive"))
      (node (ref "R186") (pin "2") (pinfunction "2_2") (pintype "passive"))
    )
    (net (code "211") (name "Net-(R180-S)") (class "Default")
      (node (ref "R180") (pin "P$2") (pinfunction "S_P$2") (pintype "passive"))
      (node (ref "R187") (pin "2") (pinfunction "2_2") (pintype "passive"))
    )
    (net (code "212") (name "Net-(R181-S)") (class "Default")
      (node (ref "R181") (pin "P$2") (pinfunction "S_P$2") (pintype "passive"))
      (node (ref "R189") (pin "2") (pinfunction "2_2") (pintype "passive"))
    )
    (net (code "213") (name "Net-(R195-A)") (class "Default")
      (node (ref "C89") (pin "2") (pinfunction "2_2") (pintype "passive"))
      (node (ref "D31") (pin "C") (pinfunction "C_C") (pintype "passive"))
      (node (ref "R149") (pin "2") (pinfunction "2_2") (pintype "passive"))
      (node (ref "R195") (pin "3") (pinfunction "A_3") (pintype "passive"))
    )
    (net (code "214") (name "Net-(R198-E)") (class "Default")
      (node (ref "R198") (pin "1") (pinfunction "E_1") (pintype "passive"))
      (node (ref "R198") (pin "2") (pinfunction "S_2") (pintype "passive"))
      (node (ref "R76") (pin "1") (pinfunction "1_1") (pintype "passive"))
    )
    (net (code "215") (name "Net-(SW1B-A1)") (class "Default")
      (node (ref "R63") (pin "1") (pinfunction "1_1") (pintype "passive"))
      (node (ref "SW1") (pin "P1") (pinfunction "A1_P1") (pintype "passive"))
    )
    (net (code "216") (name "Net-(SW1B-A3)") (class "Default")
      (node (ref "R54") (pin "2") (pinfunction "2_2") (pintype "passive"))
      (node (ref "R62") (pin "2") (pinfunction "2_2") (pintype "passive"))
      (node (ref "SW1") (pin "P3") (pinfunction "A3_P3") (pintype "passive"))
    )
    (net (code "217") (name "Net-(SW1B-B2)") (class "Default")
      (node (ref "R75") (pin "1") (pinfunction "1_1") (pintype "passive"))
      (node (ref "SW1") (pin "P5") (pinfunction "B2_P5") (pintype "passive"))
    )
    (net (code "218") (name "OUT") (class "Default")
      (node (ref "C32") (pin "2") (pinfunction "2_2") (pintype "passive"))
      (node (ref "IC8") (pin "14") (pinfunction "OUT_14") (pintype "output"))
      (node (ref "R192") (pin "1") (pinfunction "1_1") (pintype "passive"))
      (node (ref "R69") (pin "2") (pinfunction "2_2") (pintype "passive"))
    )
    (net (code "219") (name "OUT_1") (class "Default")
      (node (ref "C86") (pin "2") (pinfunction "2_2") (pintype "passive"))
      (node (ref "D38") (pin "A") (pinfunction "A_A") (pintype "passive"))
      (node (ref "IC18") (pin "1") (pinfunction "OUT_1") (pintype "output"))
      (node (ref "R153") (pin "2") (pinfunction "2_2") (pintype "passive"))
      (node (ref "R188") (pin "1") (pinfunction "1_1") (pintype "passive"))
      (node (ref "R191") (pin "1") (pinfunction "1_1") (pintype "passive"))
      (node (ref "R198") (pin "3") (pinfunction "A_3") (pintype "passive"))
      (node (ref "R71") (pin "1") (pinfunction "1_1") (pintype "passive"))
    )
    (net (code "220") (name "OUT_2") (class "Default")
      (node (ref "C87") (pin "2") (pinfunction "2_2") (pintype "passive"))
      (node (ref "D37") (pin "A") (pinfunction "A_A") (pintype "passive"))
      (node (ref "IC21") (pin "14") (pinfunction "OUT_14") (pintype "output"))
      (node (ref "R139") (pin "3") (pinfunction "A_3") (pintype "passive"))
      (node (ref "R154") (pin "2") (pinfunction "2_2") (pintype "passive"))
      (node (ref "R184") (pin "1") (pinfunction "1_1") (pintype "passive"))
      (node (ref "R193") (pin "1") (pinfunction "1_1") (pintype "passive"))
      (node (ref "R44") (pin "1") (pinfunction "1_1") (pintype "passive"))
    )
    (net (code "221") (name "RAW_IN_1") (class "Default")
      (node (ref "D49") (pin "2") (pinfunction "C_2") (pintype "passive"))
      (node (ref "J10") (pin "P3") (pinfunction "3_P3") (pintype "passive"))
      (node (ref "R33") (pin "1") (pinfunction "1_1") (pintype "passive"))
      (node (ref "R78") (pin "1") (pinfunction "1_1") (pintype "passive"))
    )
    (net (code "222") (name "VCC") (class "Default")
      (node (ref "C14") (pin "1") (pinfunction "1_1") (pintype "passive"))
      (node (ref "C15") (pin "1") (pinfunction "1_1") (pintype "passive"))
      (node (ref "C17") (pin "1") (pinfunction "1_1") (pintype "passive"))
      (node (ref "C2") (pin "1") (pinfunction "1_1") (pintype "passive"))
      (node (ref "C27") (pin "1") (pinfunction "1_1") (pintype "passive"))
      (node (ref "C29") (pin "1") (pinfunction "1_1") (pintype "passive"))
      (node (ref "C36") (pin "1") (pinfunction "1_1") (pintype "passive"))
      (node (ref "C37") (pin "1") (pinfunction "1_1") (pintype "passive"))
      (node (ref "C44") (pin "1") (pinfunction "1_1") (pintype "passive"))
      (node (ref "C45") (pin "1") (pinfunction "1_1") (pintype "passive"))
      (node (ref "C46") (pin "1") (pinfunction "1_1") (pintype "passive"))
      (node (ref "C47") (pin "1") (pinfunction "1_1") (pintype "passive"))
      (node (ref "C55") (pin "+") (pinfunction "+_+") (pintype "passive"))
      (node (ref "C66") (pin "1") (pinfunction "1_1") (pintype "passive"))
      (node (ref "C68") (pin "1") (pinfunction "1_1") (pintype "passive"))
      (node (ref "C70") (pin "1") (pinfunction "1_1") (pintype "passive"))
      (node (ref "C71") (pin "1") (pinfunction "1_1") (pintype "passive"))
      (node (ref "C8") (pin "1") (pinfunction "1_1") (pintype "passive"))
      (node (ref "C92") (pin "1") (pinfunction "1_1") (pintype "passive"))
      (node (ref "C94") (pin "1") (pinfunction "1_1") (pintype "passive"))
      (node (ref "C96") (pin "1") (pinfunction "1_1") (pintype "passive"))
      (node (ref "C98") (pin "1") (pinfunction "1_1") (pintype "passive"))
      (node (ref "IC1") (pin "4") (pinfunction "V+_4") (pintype "power_in"))
      (node (ref "IC12") (pin "16") (pinfunction "V+_16") (pintype "power_in"))
      (node (ref "IC13") (pin "16") (pinfunction "V+_16") (pintype "power_in"))
      (node (ref "IC14") (pin "4") (pinfunction "V+_4") (pintype "power_in"))
      (node (ref "IC15") (pin "4") (pinfunction "V+_4") (pintype "power_in"))
      (node (ref "IC16") (pin "16") (pinfunction "V+_16") (pintype "power_in"))
      (node (ref "IC17") (pin "16") (pinfunction "V+_16") (pintype "power_in"))
      (node (ref "IC18") (pin "4") (pinfunction "V+_4") (pintype "power_in"))
      (node (ref "IC19") (pin "4") (pinfunction "V+_4") (pintype "power_in"))
      (node (ref "IC2") (pin "4") (pinfunction "V+_4") (pintype "power_in"))
      (node (ref "IC20") (pin "4") (pinfunction "V+_4") (pintype "power_in"))
      (node (ref "IC21") (pin "4") (pinfunction "V+_4") (pintype "power_in"))
      (node (ref "IC3") (pin "4") (pinfunction "V+_4") (pintype "power_in"))
      (node (ref "IC4") (pin "16") (pinfunction "V+_16") (pintype "power_in"))
      (node (ref "IC5") (pin "16") (pinfunction "V+_16") (pintype "power_in"))
      (node (ref "IC6") (pin "8") (pinfunction "V+_8") (pintype "power_in"))
      (node (ref "IC7") (pin "8") (pinfunction "V+_8") (pintype "power_in"))
      (node (ref "IC8") (pin "4") (pinfunction "V+_4") (pintype "power_in"))
      (node (ref "IC9") (pin "8") (pinfunction "V+_8") (pintype "power_in"))
      (node (ref "L2") (pin "1") (pinfunction "1_1") (pintype "passive"))
      (node (ref "R124") (pin "2") (pinfunction "2_2") (pintype "passive"))
      (node (ref "R125") (pin "2") (pinfunction "2_2") (pintype "passive"))
      (node (ref "R30") (pin "2") (pinfunction "2_2") (pintype "passive"))
      (node (ref "R31") (pin "2") (pinfunction "2_2") (pintype "passive"))
      (node (ref "R83") (pin "1") (pinfunction "1_1") (pintype "passive"))
      (node (ref "R84") (pin "2") (pinfunction "2_2") (pintype "passive"))
      (node (ref "R85") (pin "2") (pinfunction "2_2") (pintype "passive"))
      (node (ref "SW1") (pin "P6") (pinfunction "B3_P6") (pintype "passive"))
    )
    (net (code "223") (name "VEE") (class "Default")
      (node (ref "C1") (pin "2") (pinfunction "2_2") (pintype "passive"))
      (node (ref "C16") (pin "2") (pinfunction "2_2") (pintype "passive"))
      (node (ref "C30") (pin "2") (pinfunction "2_2") (pintype "passive"))
      (node (ref "C31") (pin "2") (pinfunction "2_2") (pintype "passive"))
      (node (ref "C34") (pin "2") (pinfunction "2_2") (pintype "passive"))
      (node (ref "C35") (pin "2") (pinfunction "2_2") (pintype "passive"))
      (node (ref "C40") (pin "2") (pinfunction "2_2") (pintype "passive"))
      (node (ref "C41") (pin "2") (pinfunction "2_2") (pintype "passive"))
      (node (ref "C52") (pin "2") (pinfunction "2_2") (pintype "passive"))
      (node (ref "C53") (pin "2") (pinfunction "2_2") (pintype "passive"))
      (node (ref "C54") (pin "-") (pinfunction "-_-") (pintype "passive"))
      (node (ref "C58") (pin "2") (pinfunction "2_2") (pintype "passive"))
      (node (ref "C59") (pin "2") (pinfunction "2_2") (pintype "passive"))
      (node (ref "C67") (pin "2") (pinfunction "2_2") (pintype "passive"))
      (node (ref "C69") (pin "2") (pinfunction "2_2") (pintype "passive"))
      (node (ref "C7") (pin "2") (pinfunction "2_2") (pintype "passive"))
      (node (ref "C84") (pin "2") (pinfunction "2_2") (pintype "passive"))
      (node (ref "C85") (pin "2") (pinfunction "2_2") (pintype "passive"))
      (node (ref "C93") (pin "2") (pinfunction "2_2") (pintype "passive"))
      (node (ref "C95") (pin "2") (pinfunction "2_2") (pintype "passive"))
      (node (ref "C97") (pin "2") (pinfunction "2_2") (pintype "passive"))
      (node (ref "C99") (pin "2") (pinfunction "2_2") (pintype "passive"))
      (node (ref "D20") (pin "A") (pinfunction "A_A") (pintype "passive"))
      (node (ref "IC1") (pin "11") (pinfunction "V-_11") (pintype "power_in"))
      (node (ref "IC12") (pin "9") (pinfunction "V-_9") (pintype "power_in"))
      (node (ref "IC13") (pin "9") (pinfunction "V-_9") (pintype "power_in"))
      (node (ref "IC14") (pin "11") (pinfunction "V-_11") (pintype "power_in"))
      (node (ref "IC15") (pin "11") (pinfunction "V-_11") (pintype "power_in"))
      (node (ref "IC16") (pin "9") (pinfunction "V-_9") (pintype "power_in"))
      (node (ref "IC17") (pin "9") (pinfunction "V-_9") (pintype "power_in"))
      (node (ref "IC18") (pin "11") (pinfunction "V-_11") (pintype "power_in"))
      (node (ref "IC19") (pin "11") (pinfunction "V-_11") (pintype "power_in"))
      (node (ref "IC2") (pin "11") (pinfunction "V-_11") (pintype "power_in"))
      (node (ref "IC20") (pin "11") (pinfunction "V-_11") (pintype "power_in"))
      (node (ref "IC21") (pin "11") (pinfunction "V-_11") (pintype "power_in"))
      (node (ref "IC3") (pin "11") (pinfunction "V-_11") (pintype "power_in"))
      (node (ref "IC4") (pin "9") (pinfunction "V-_9") (pintype "power_in"))
      (node (ref "IC5") (pin "9") (pinfunction "V-_9") (pintype "power_in"))
      (node (ref "IC6") (pin "4") (pinfunction "V-_4") (pintype "power_in"))
      (node (ref "IC7") (pin "4") (pinfunction "V-_4") (pintype "power_in"))
      (node (ref "IC8") (pin "11") (pinfunction "V-_11") (pintype "power_in"))
      (node (ref "IC9") (pin "4") (pinfunction "V-_4") (pintype "power_in"))
      (node (ref "L1") (pin "1") (pinfunction "1_1") (pintype "passive"))
      (node (ref "R82") (pin "1") (pinfunction "1_1") (pintype "passive"))
    )
    (net (code "224") (name "unconnected-(IC16C-CTRL-Pad11)") (class "Default")
      (node (ref "IC16") (pin "11") (pinfunction "CTRL_11") (pintype "input"))
    )
    (net (code "225") (name "unconnected-(IC17B-CTRL-Pad6)") (class "Default")
      (node (ref "IC17") (pin "6") (pinfunction "CTRL_6") (pintype "input"))
    )
    (net (code "226") (name "unconnected-(J12-2-PadP2)") (class "Default")
      (node (ref "J12") (pin "P2") (pinfunction "2_P2") (pintype "passive"))
    )
    (net (code "227") (name "unconnected-(J13-2-PadP2)") (class "Default")
      (node (ref "J13") (pin "P2") (pinfunction "2_P2") (pintype "passive"))
    )
    (net (code "228") (name "unconnected-(J14-2-PadP2)") (class "Default")
      (node (ref "J14") (pin "P2") (pinfunction "2_P2") (pintype "passive"))
    )
    (net (code "229") (name "unconnected-(SW1B-B1-PadP4)") (class "Default")
      (node (ref "SW1") (pin "P4") (pinfunction "B1_P4") (pintype "passive"))
    )
    (net (code "230") (name "~{OUT_1}") (class "Default")
      (node (ref "IC9") (pin "1") (pinfunction "OUT_1") (pintype "output"))
      (node (ref "R197") (pin "2") (pinfunction "2_2") (pintype "passive"))
      (node (ref "R46") (pin "1") (pinfunction "1_1") (pintype "passive"))
      (node (ref "R70") (pin "1") (pinfunction "1_1") (pintype "passive"))
      (node (ref "R72") (pin "2") (pinfunction "2_2") (pintype "passive"))
    )
    (net (code "231") (name "~{TOPOLOGY_CV}") (class "Default")
      (node (ref "C11") (pin "2") (pinfunction "2_2") (pintype "passive"))
      (node (ref "IC3") (pin "1") (pinfunction "OUT_1") (pintype "output"))
      (node (ref "R16") (pin "2") (pinfunction "2_2") (pintype "passive"))
      (node (ref "R42") (pin "1") (pinfunction "1_1") (pintype "passive"))
      (node (ref "R43") (pin "1") (pinfunction "1_1") (pintype "passive"))
    )
  )
)
